# IoT4Bees-Ctrl_1V1.net
KiCad netlist of a schematic drawn in EAGLE
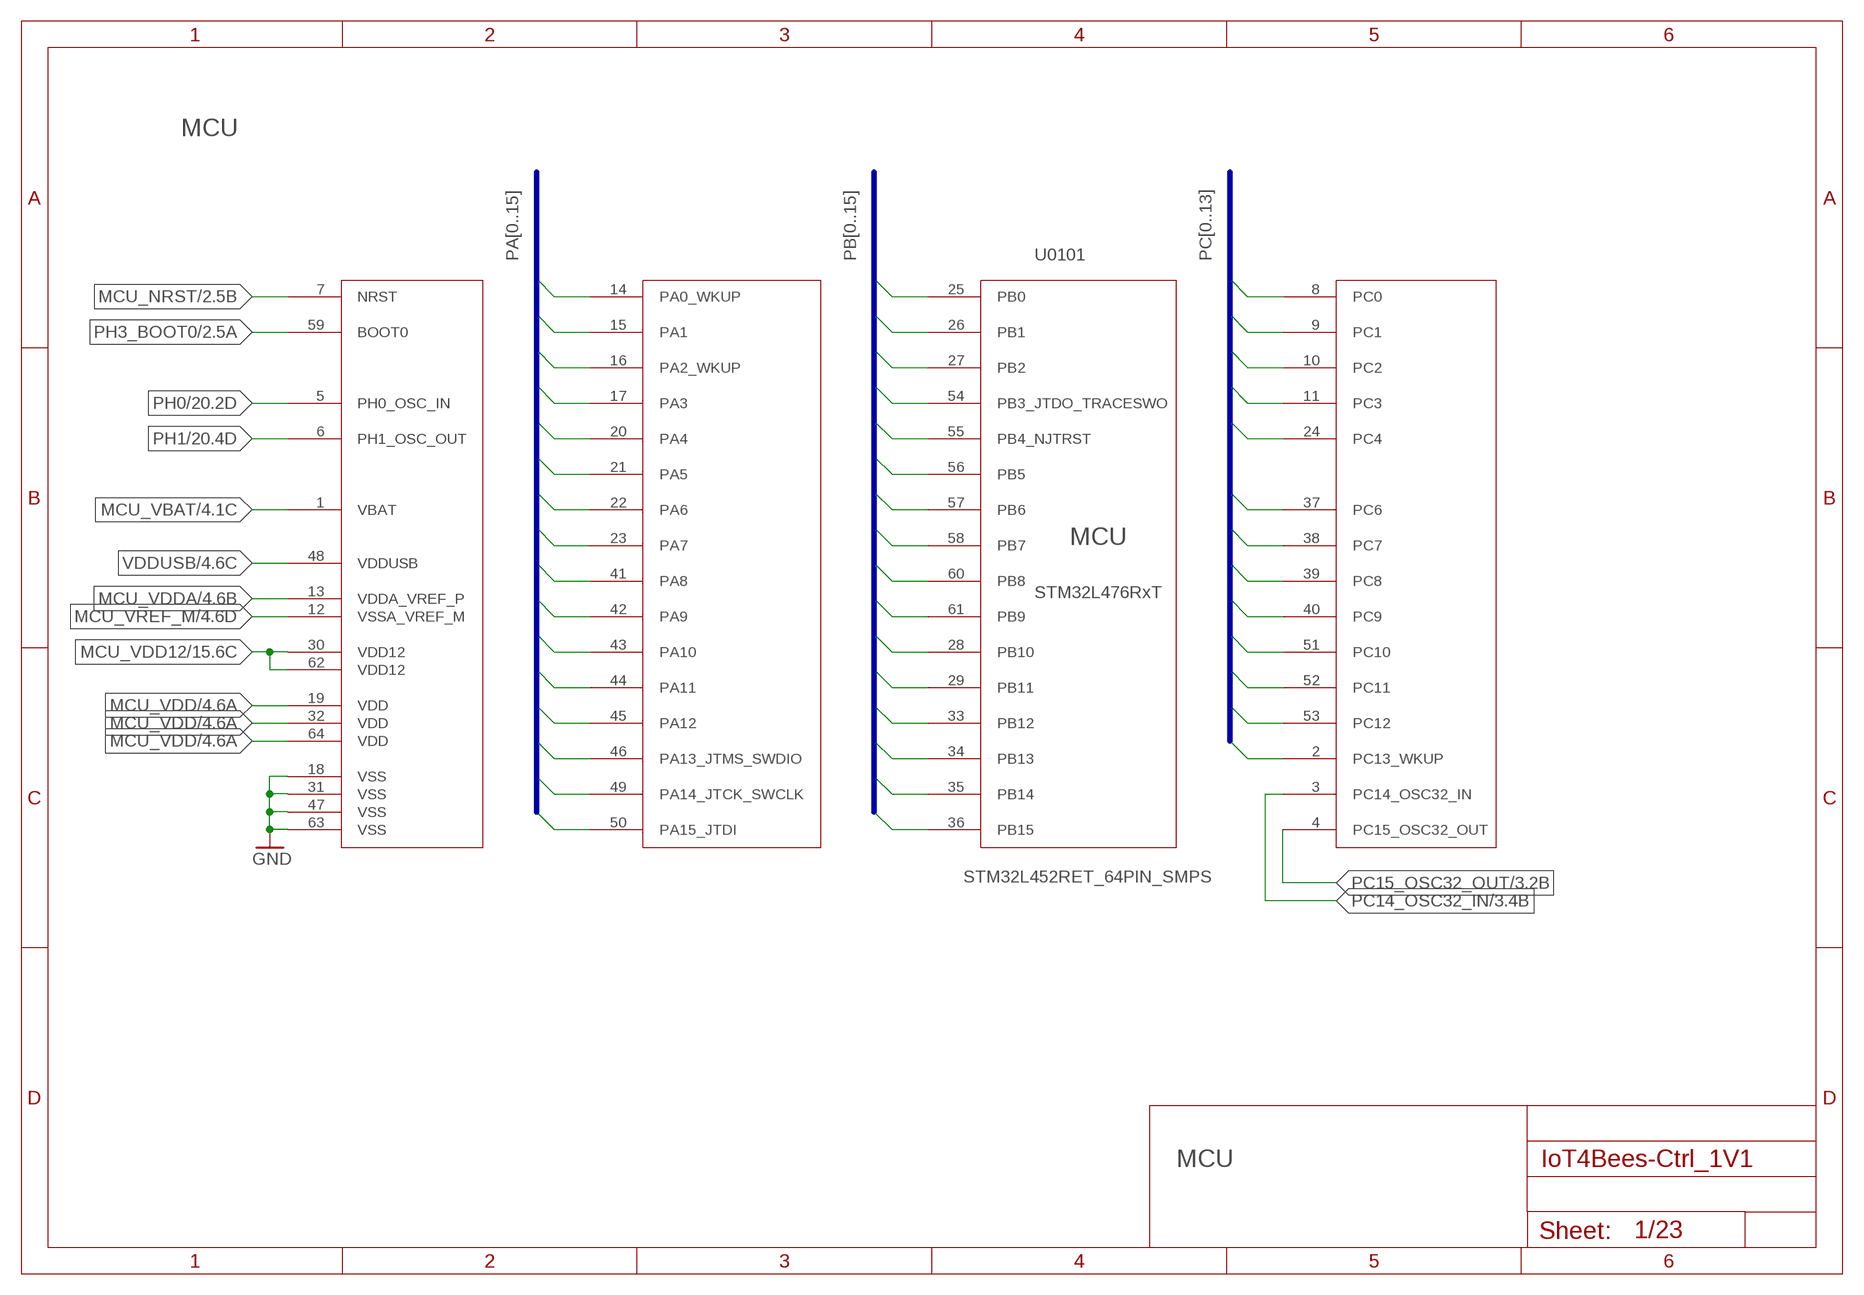
[diagram p0: schematic, sheet 1]
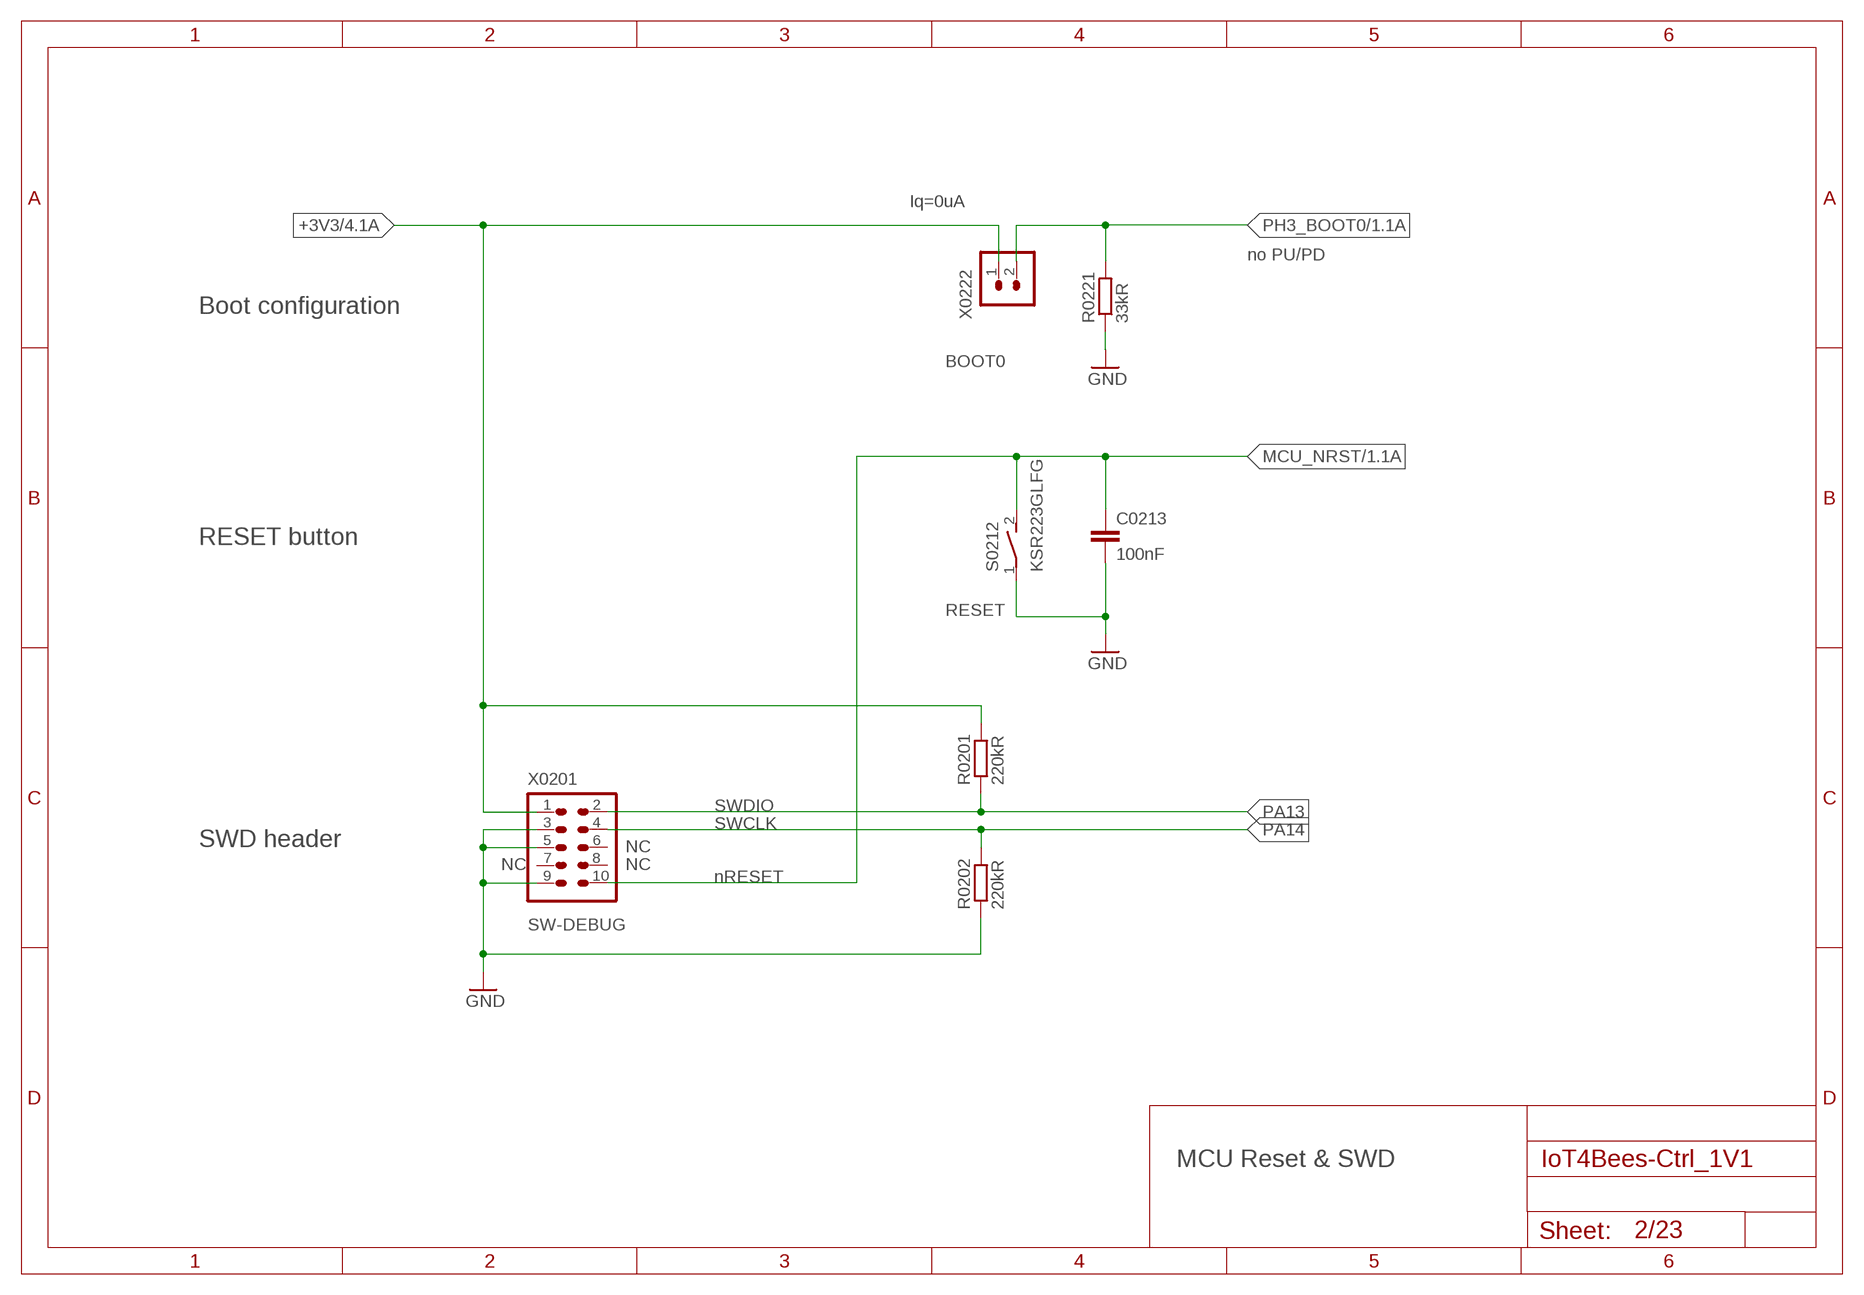
[diagram p1: schematic, sheet 2]
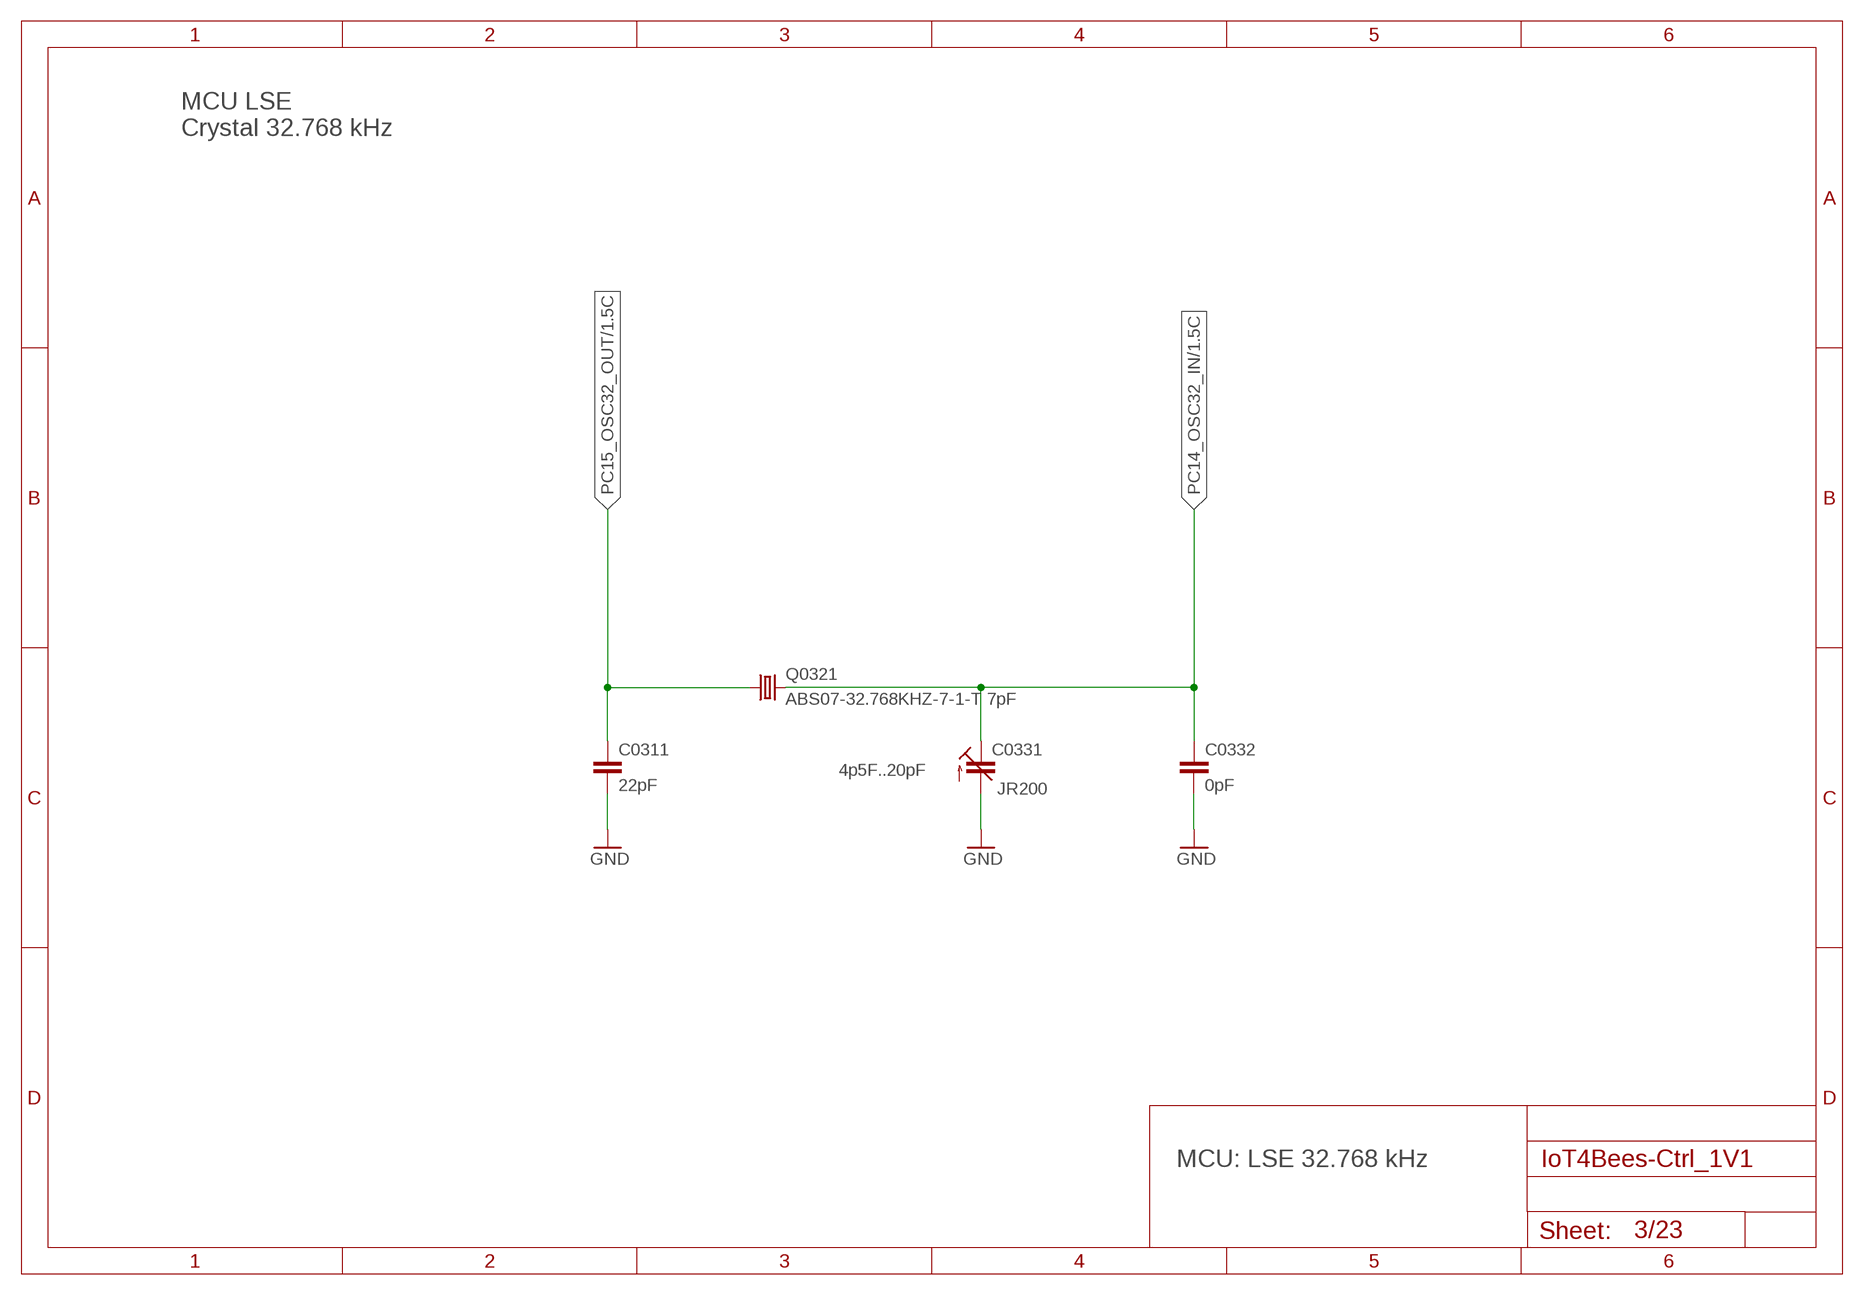
[diagram p2: schematic, sheet 3]
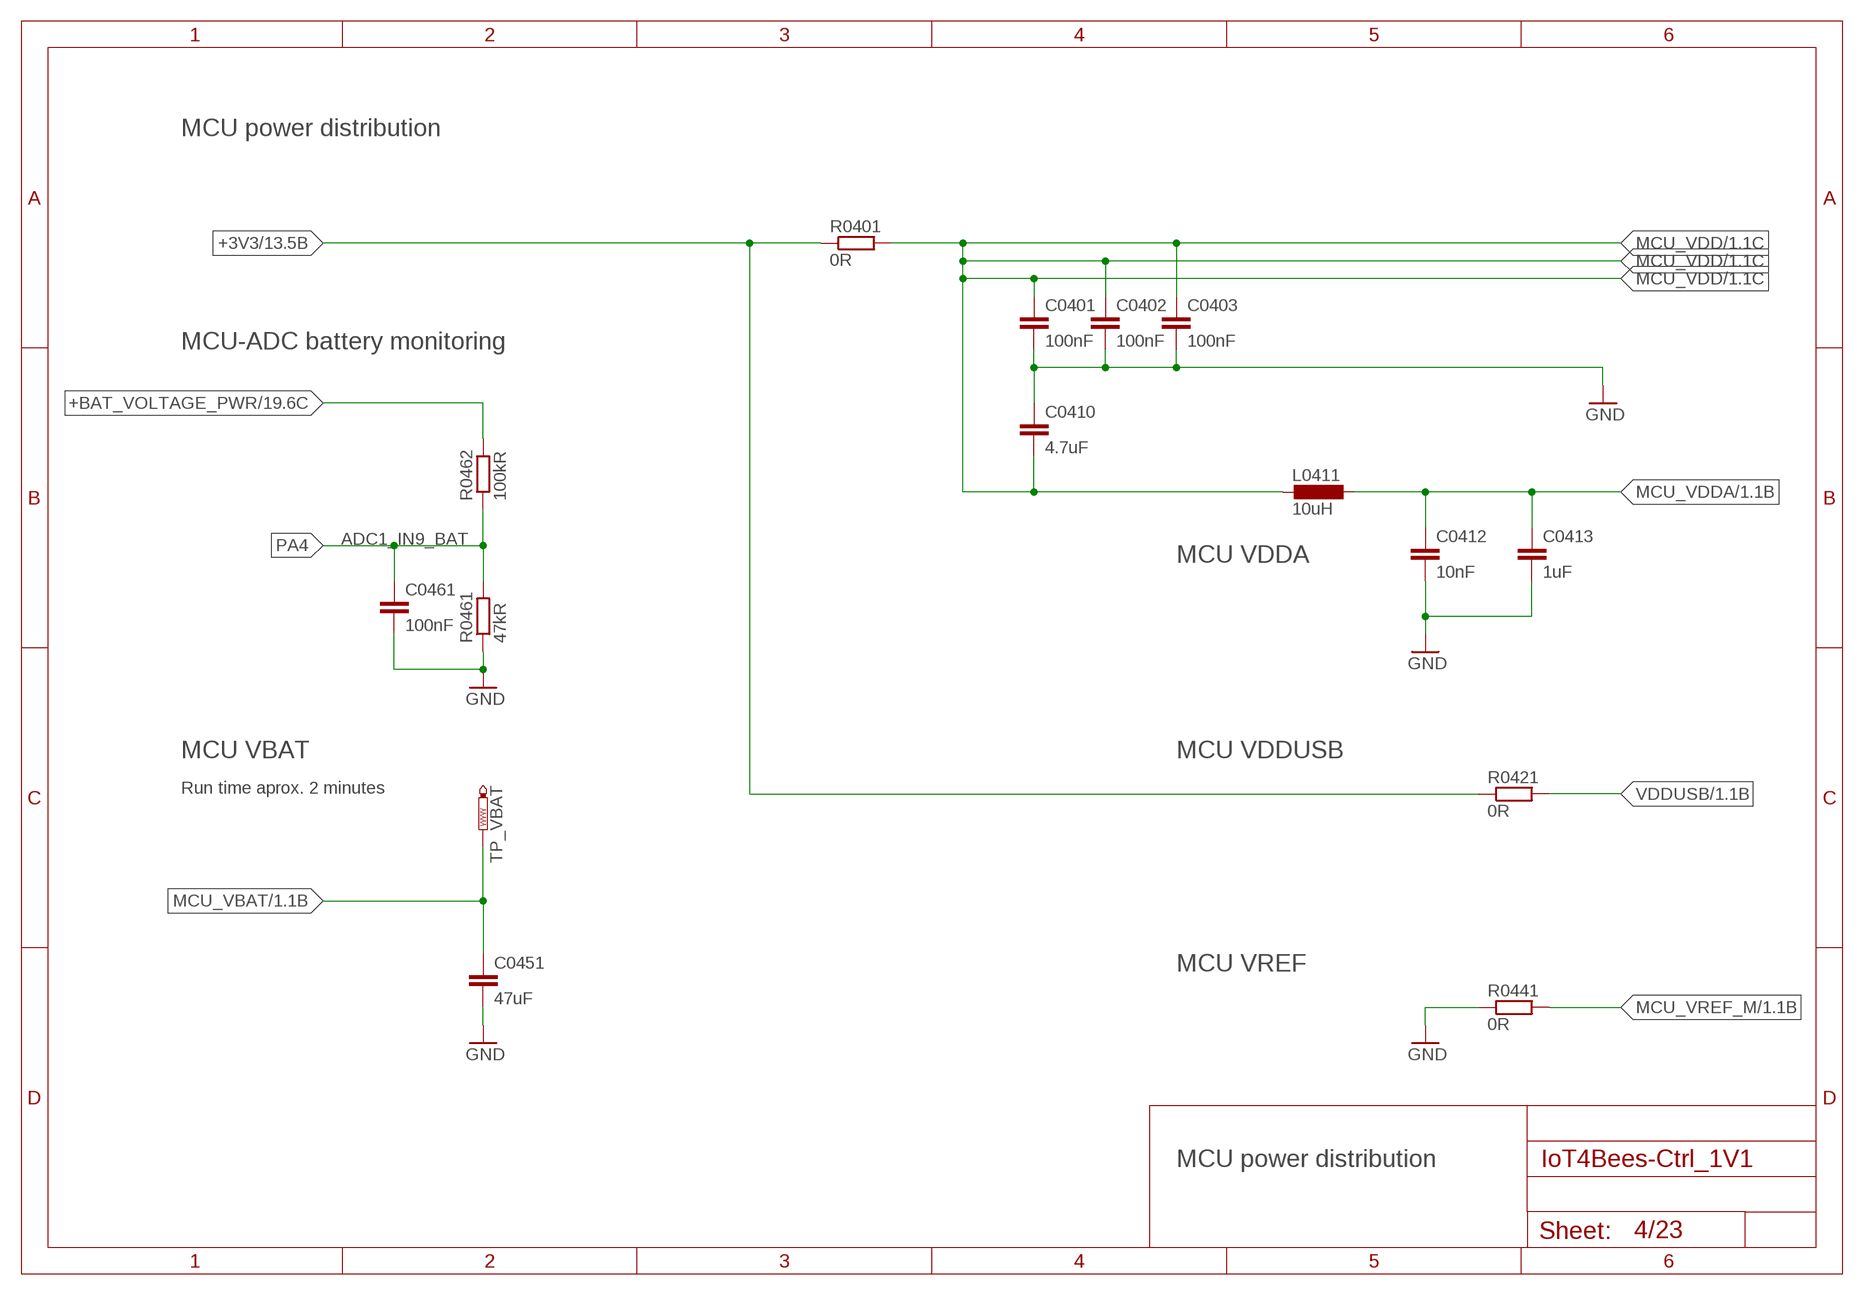
[diagram p3: schematic, sheet 4]
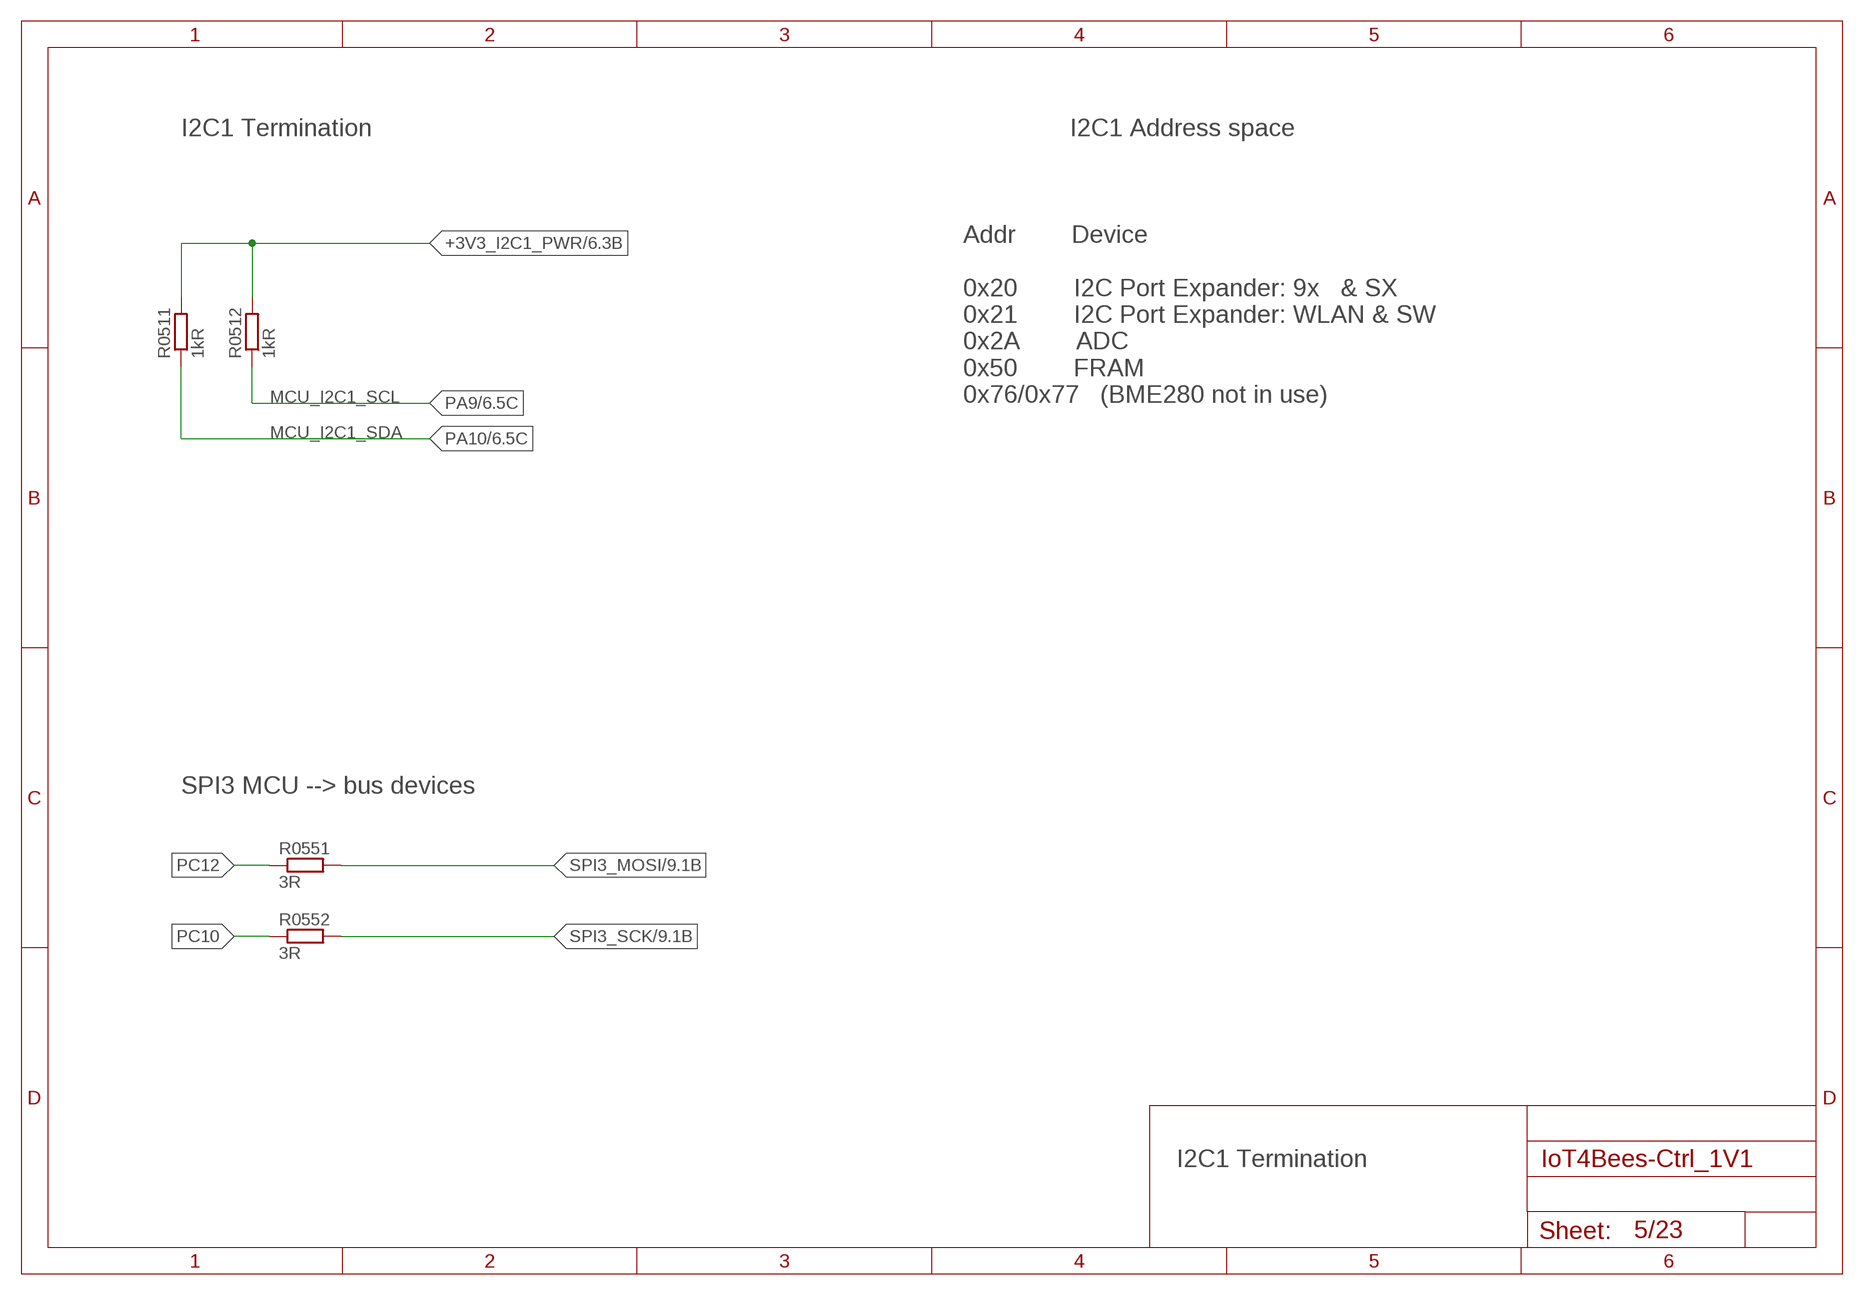
[diagram p4: schematic, sheet 5]
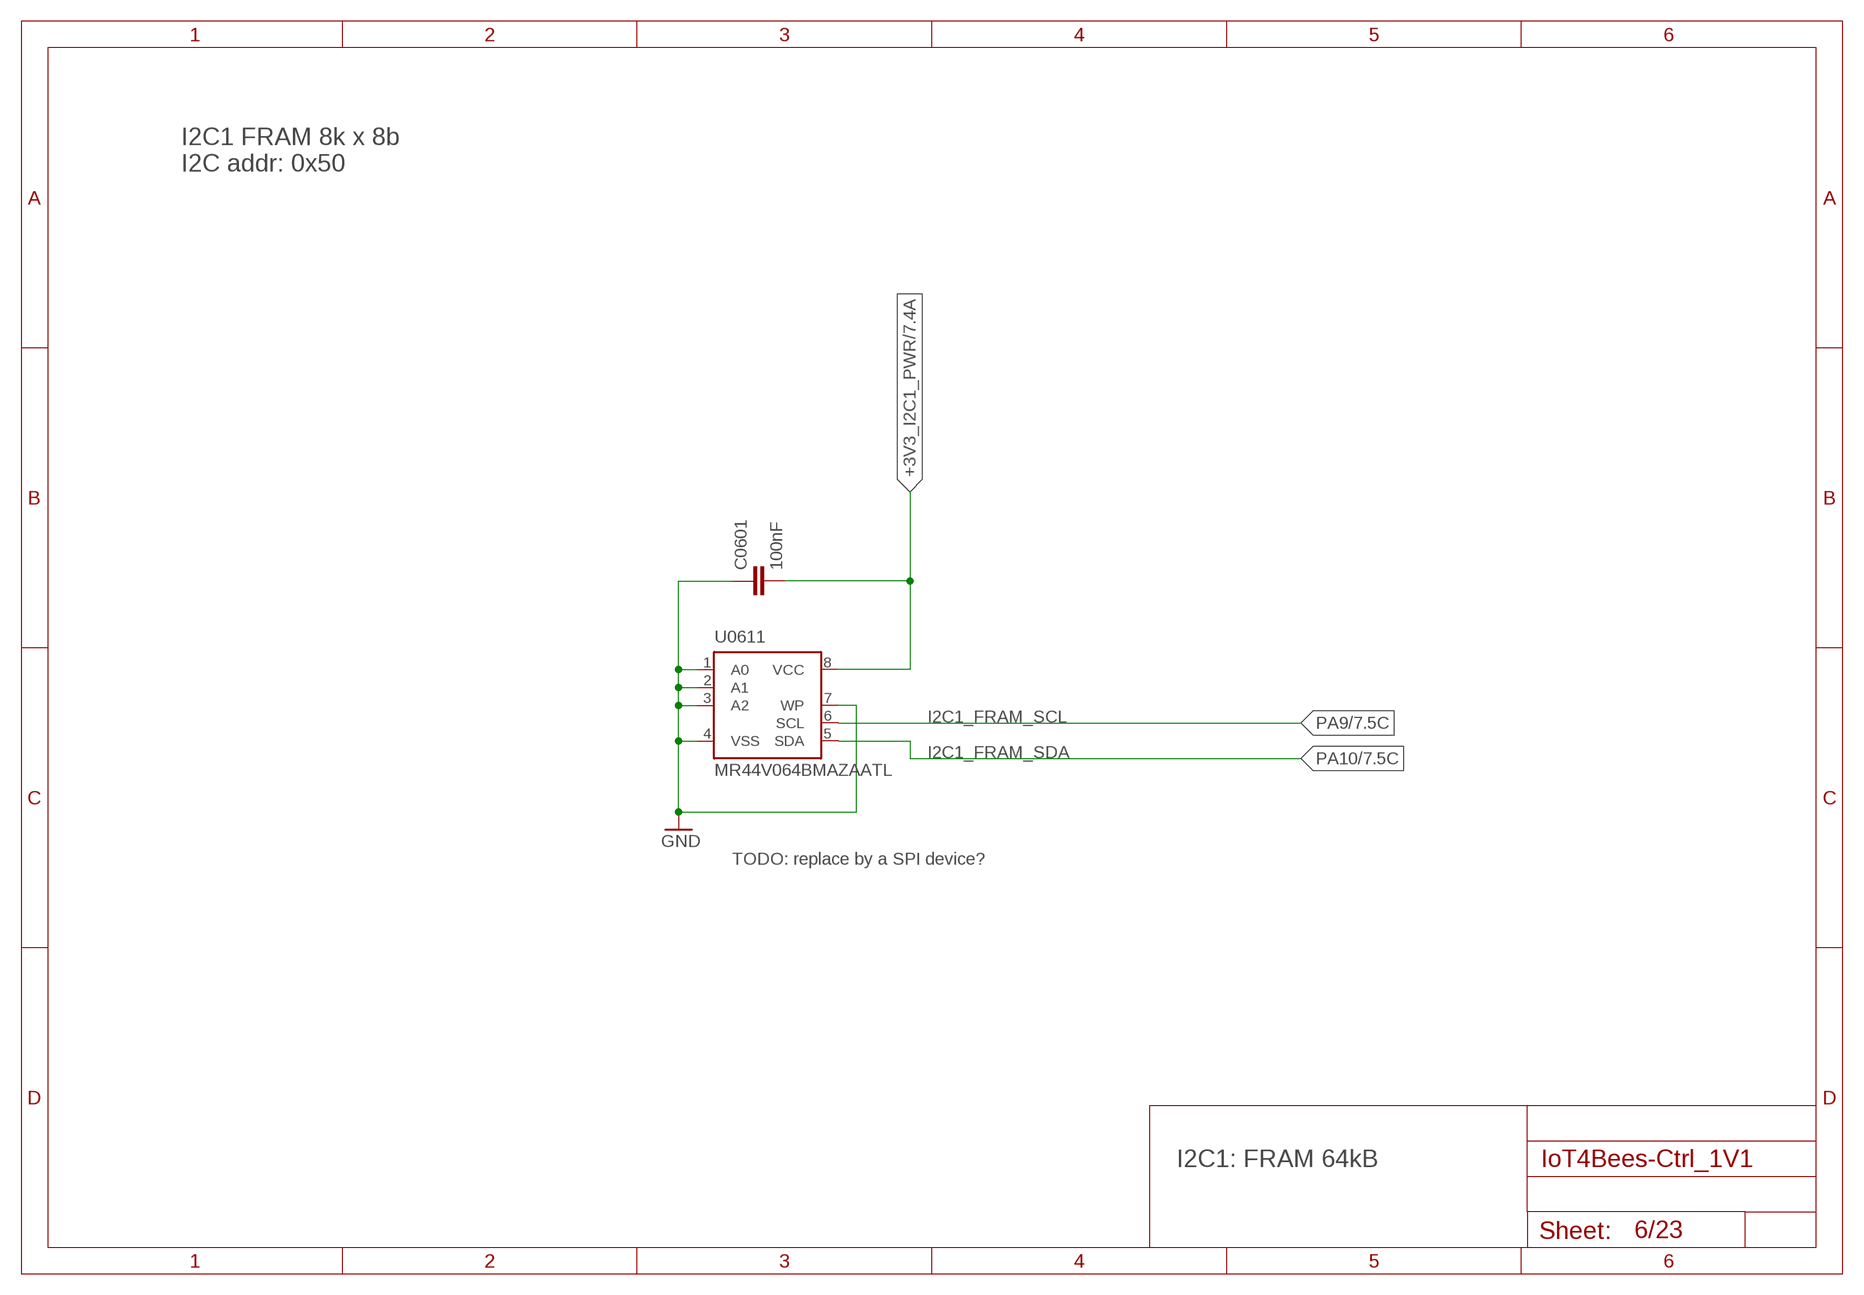
[diagram p5: schematic, sheet 6]
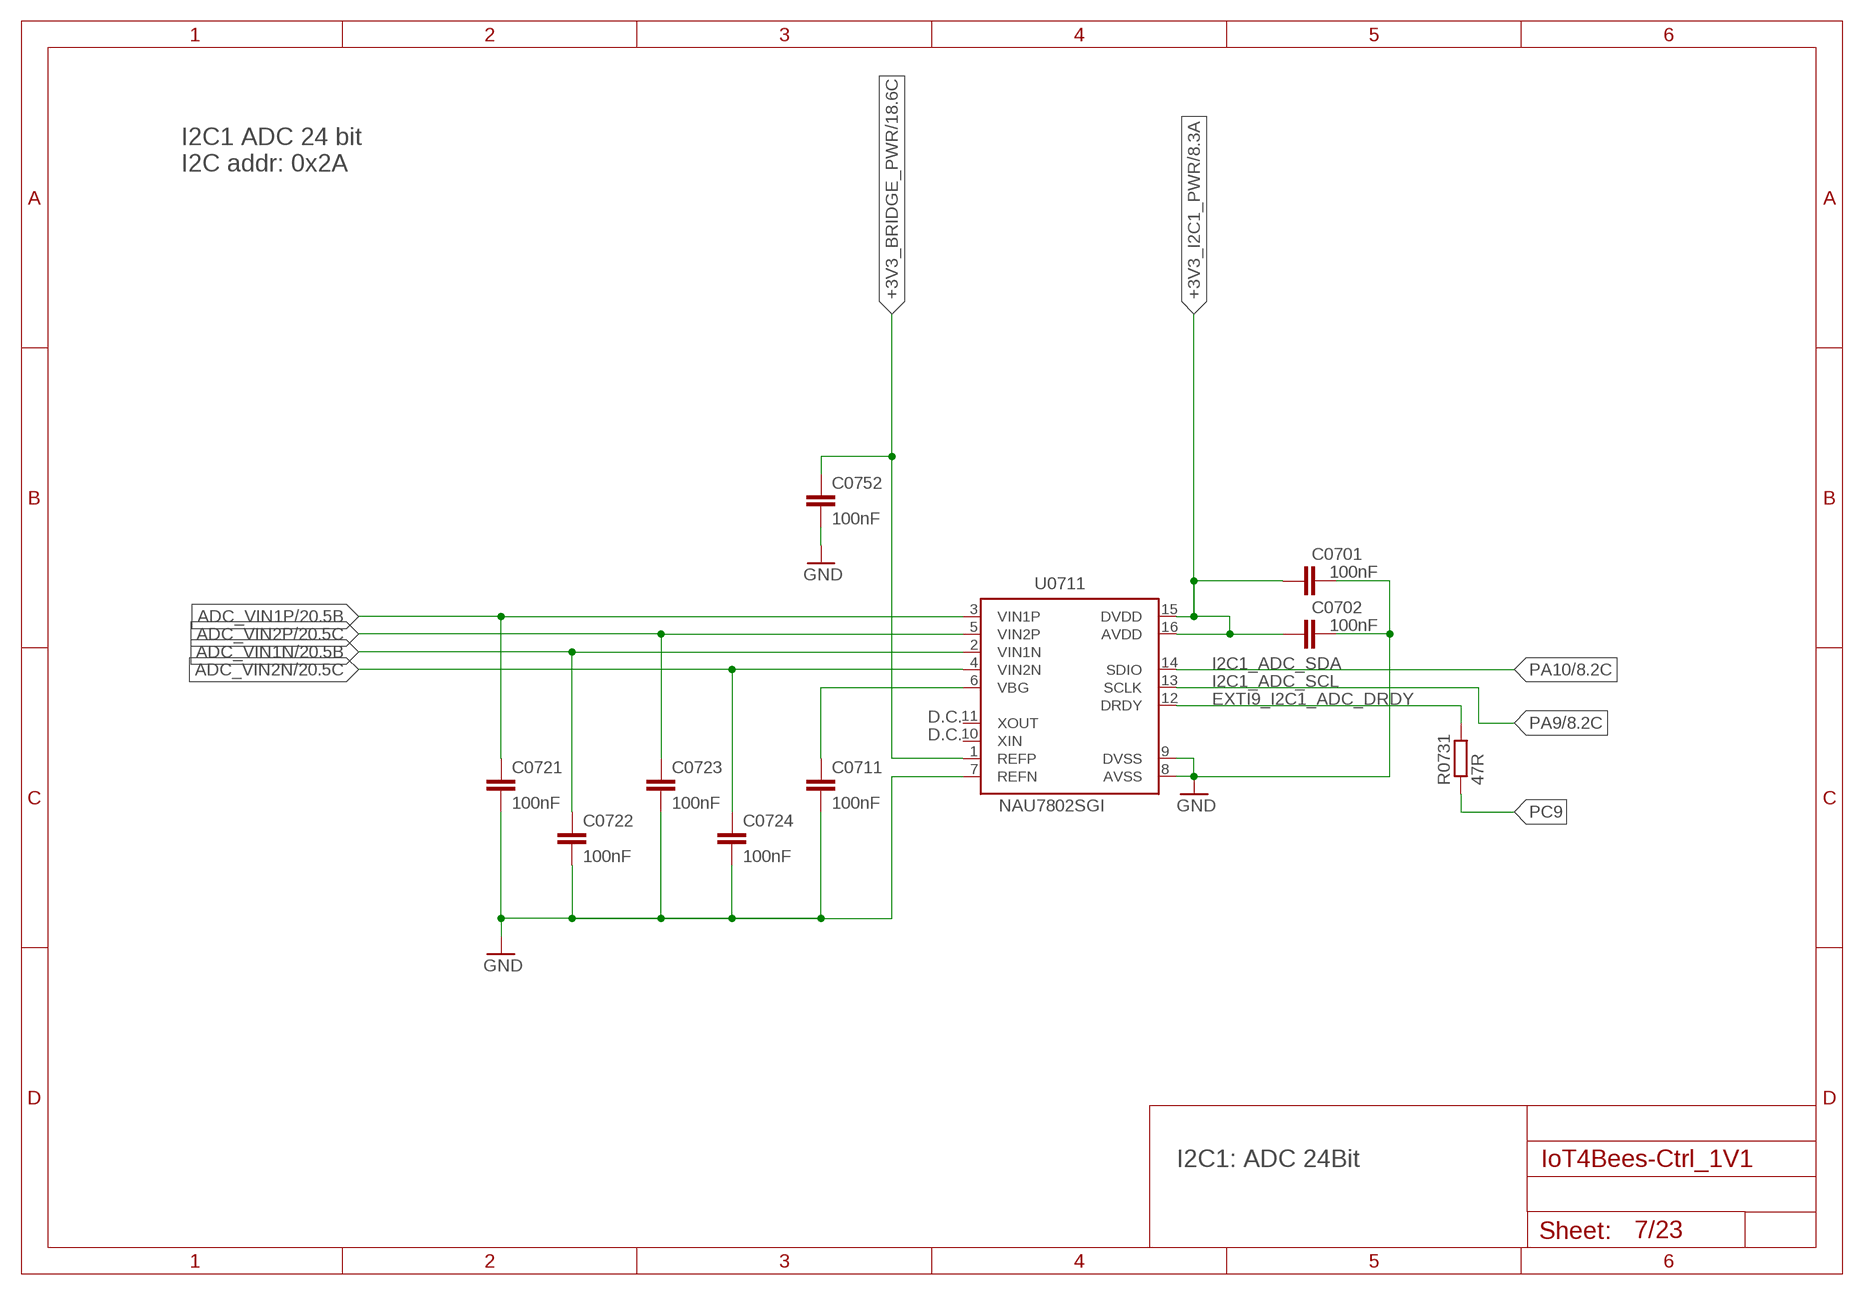
[diagram p6: schematic, sheet 7]
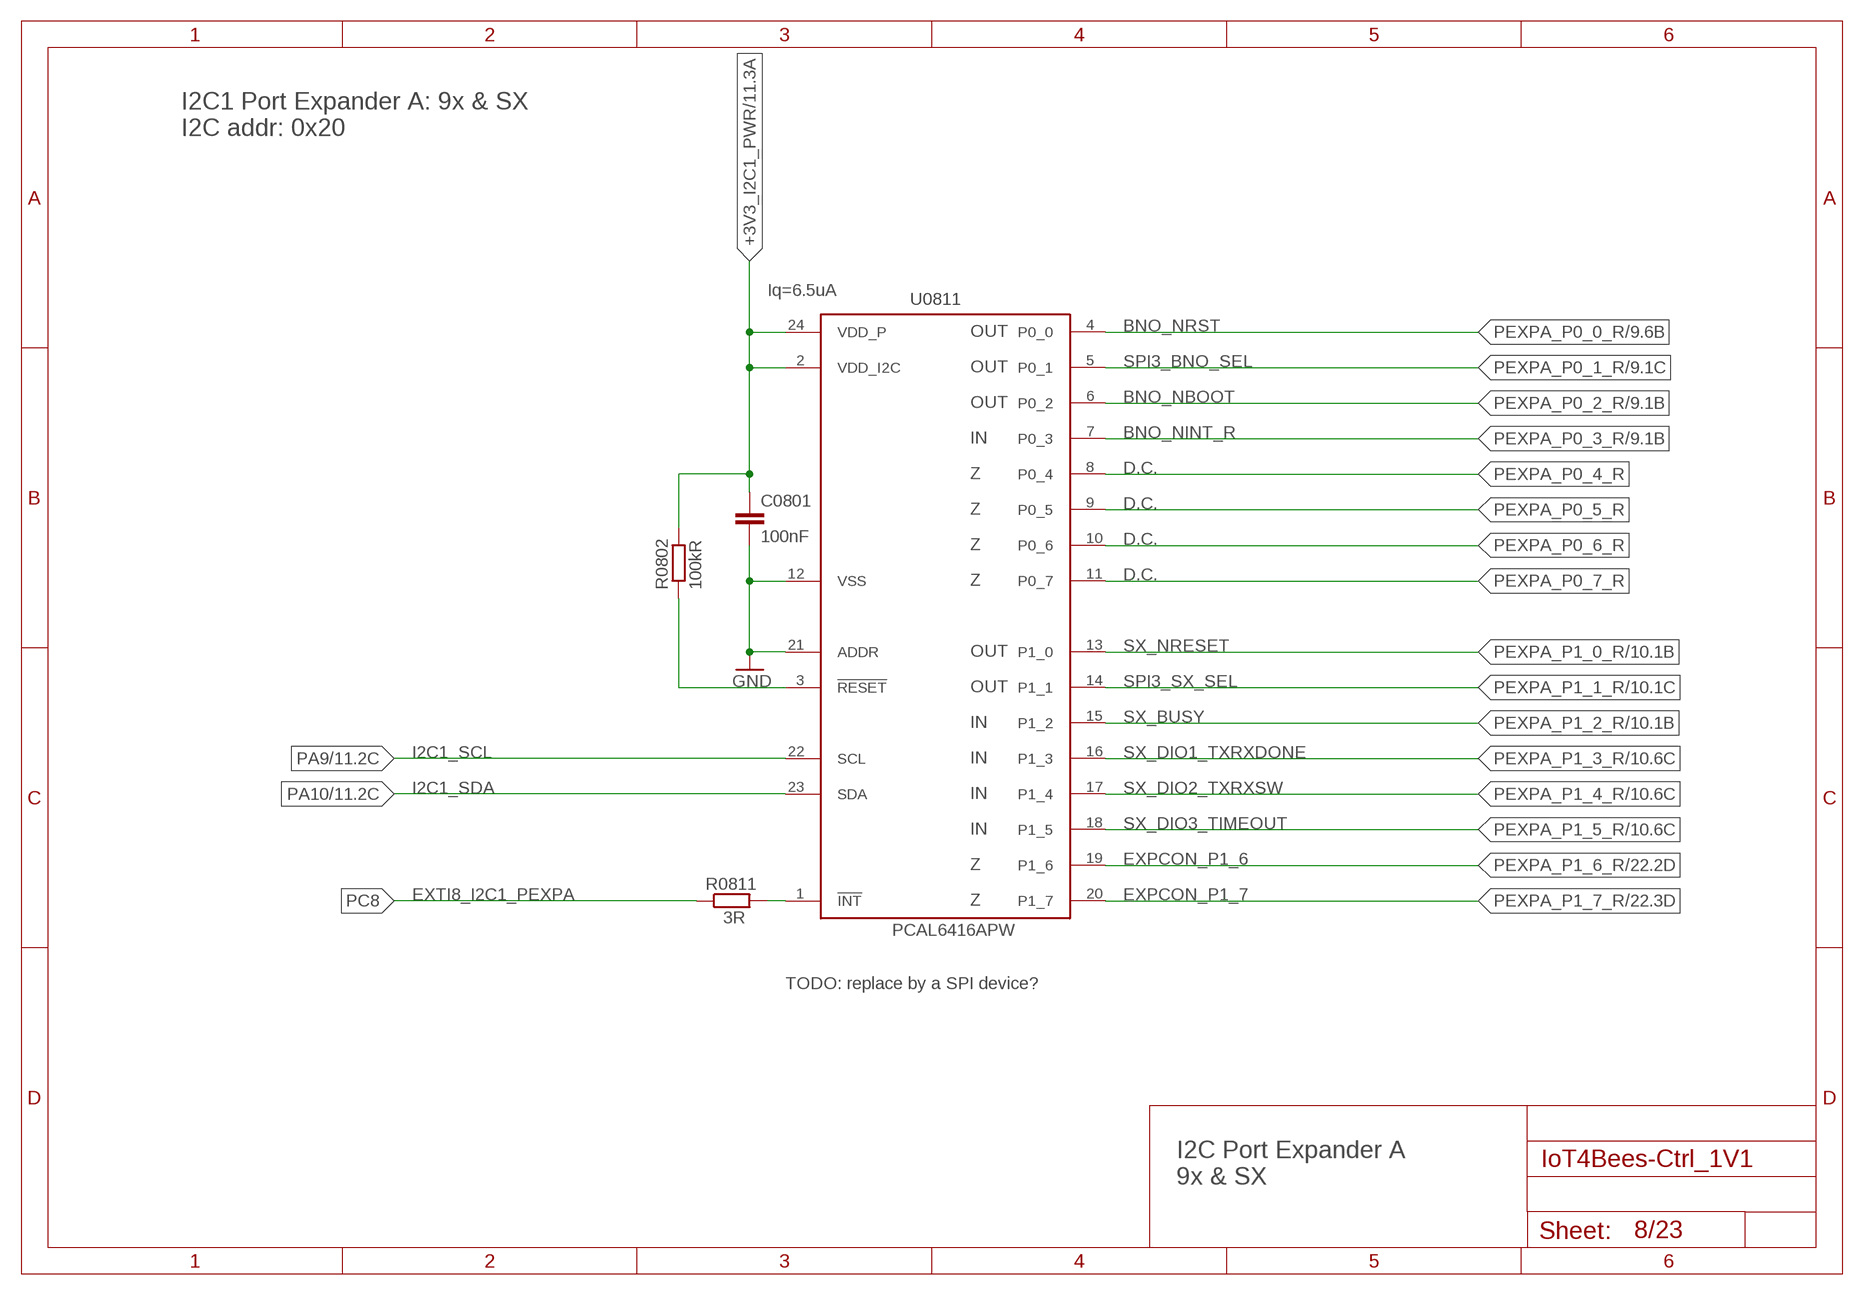
[diagram p7: schematic, sheet 8]
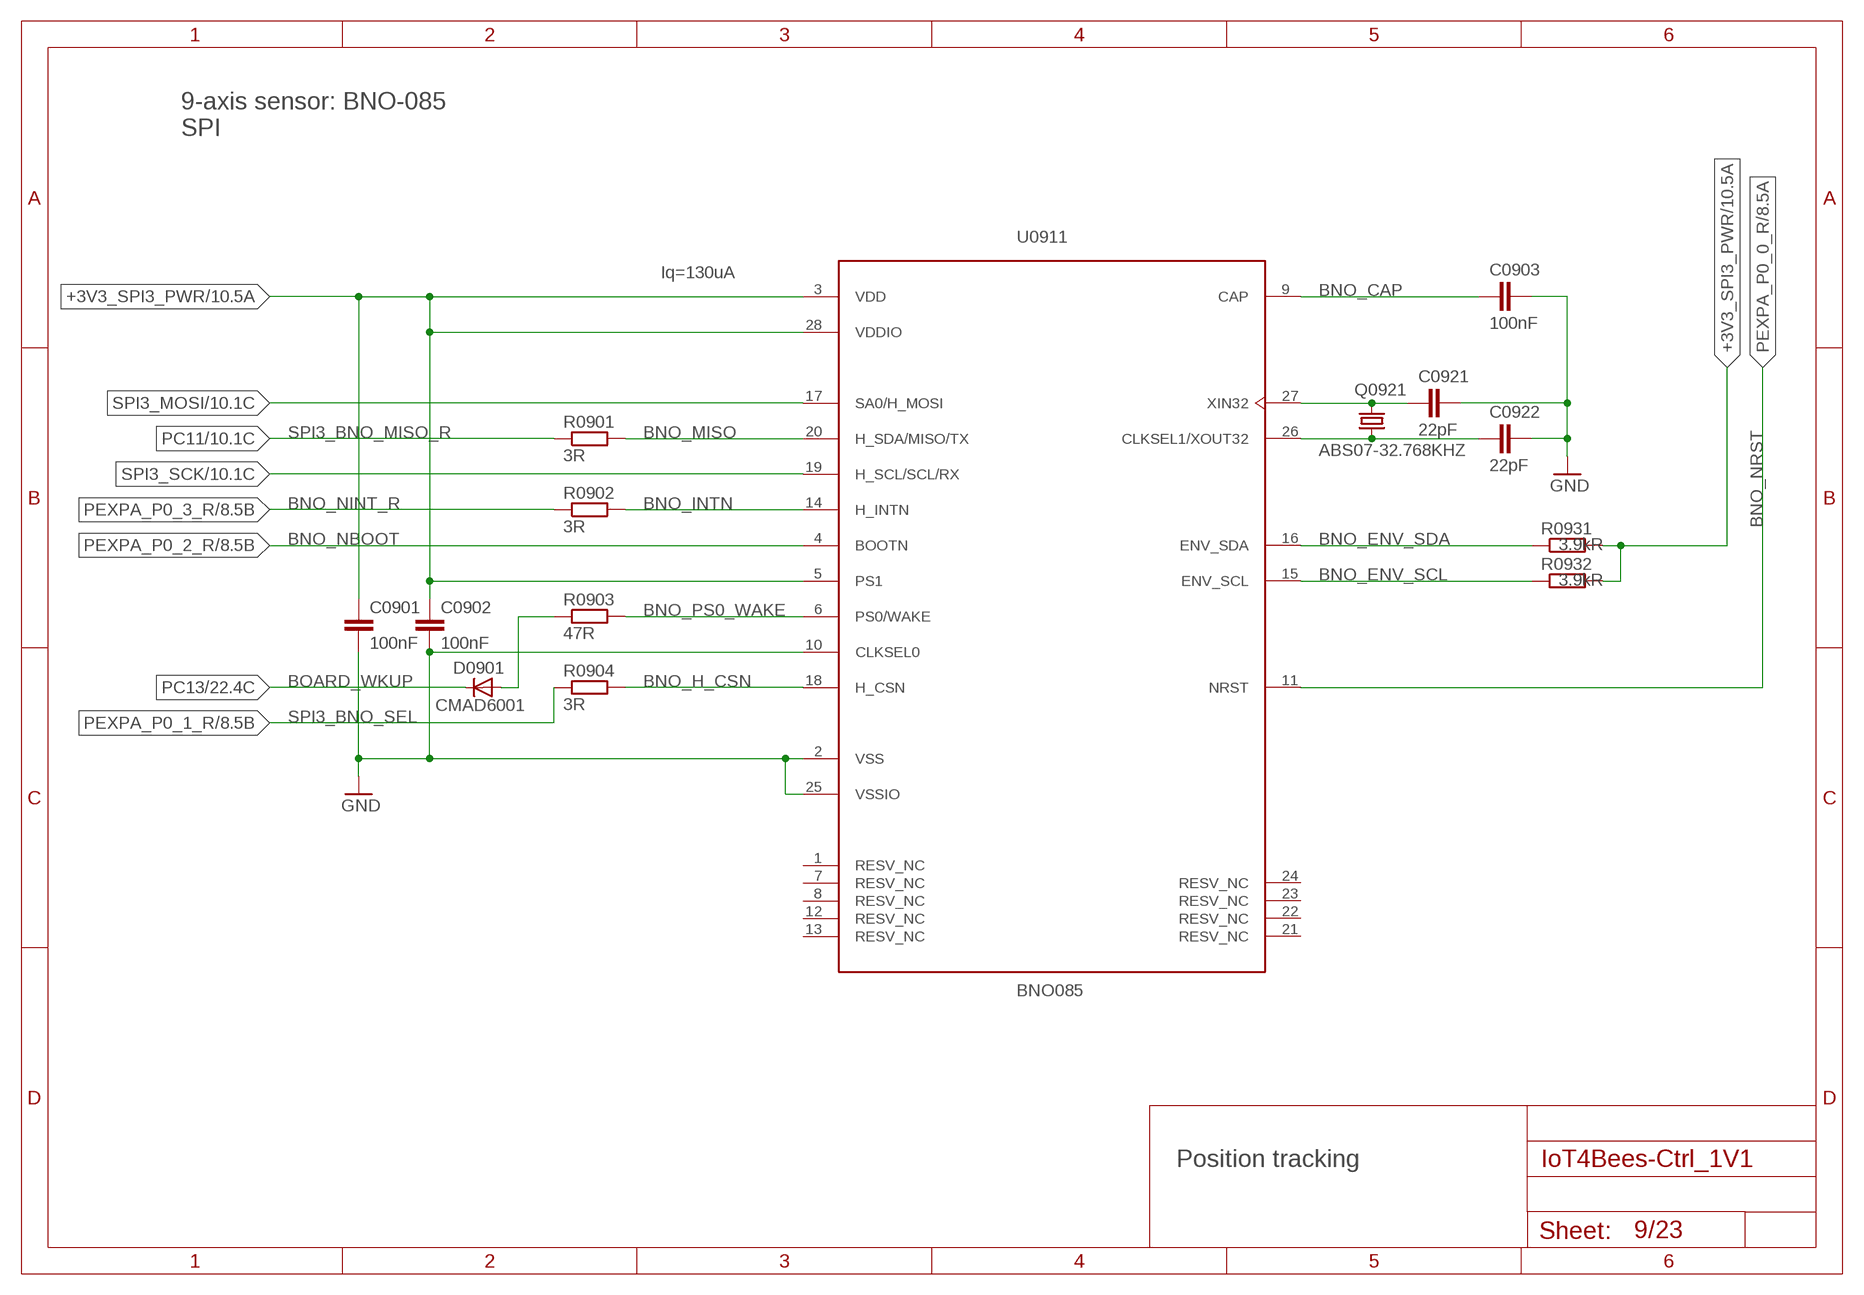
[diagram p8: schematic, sheet 9]
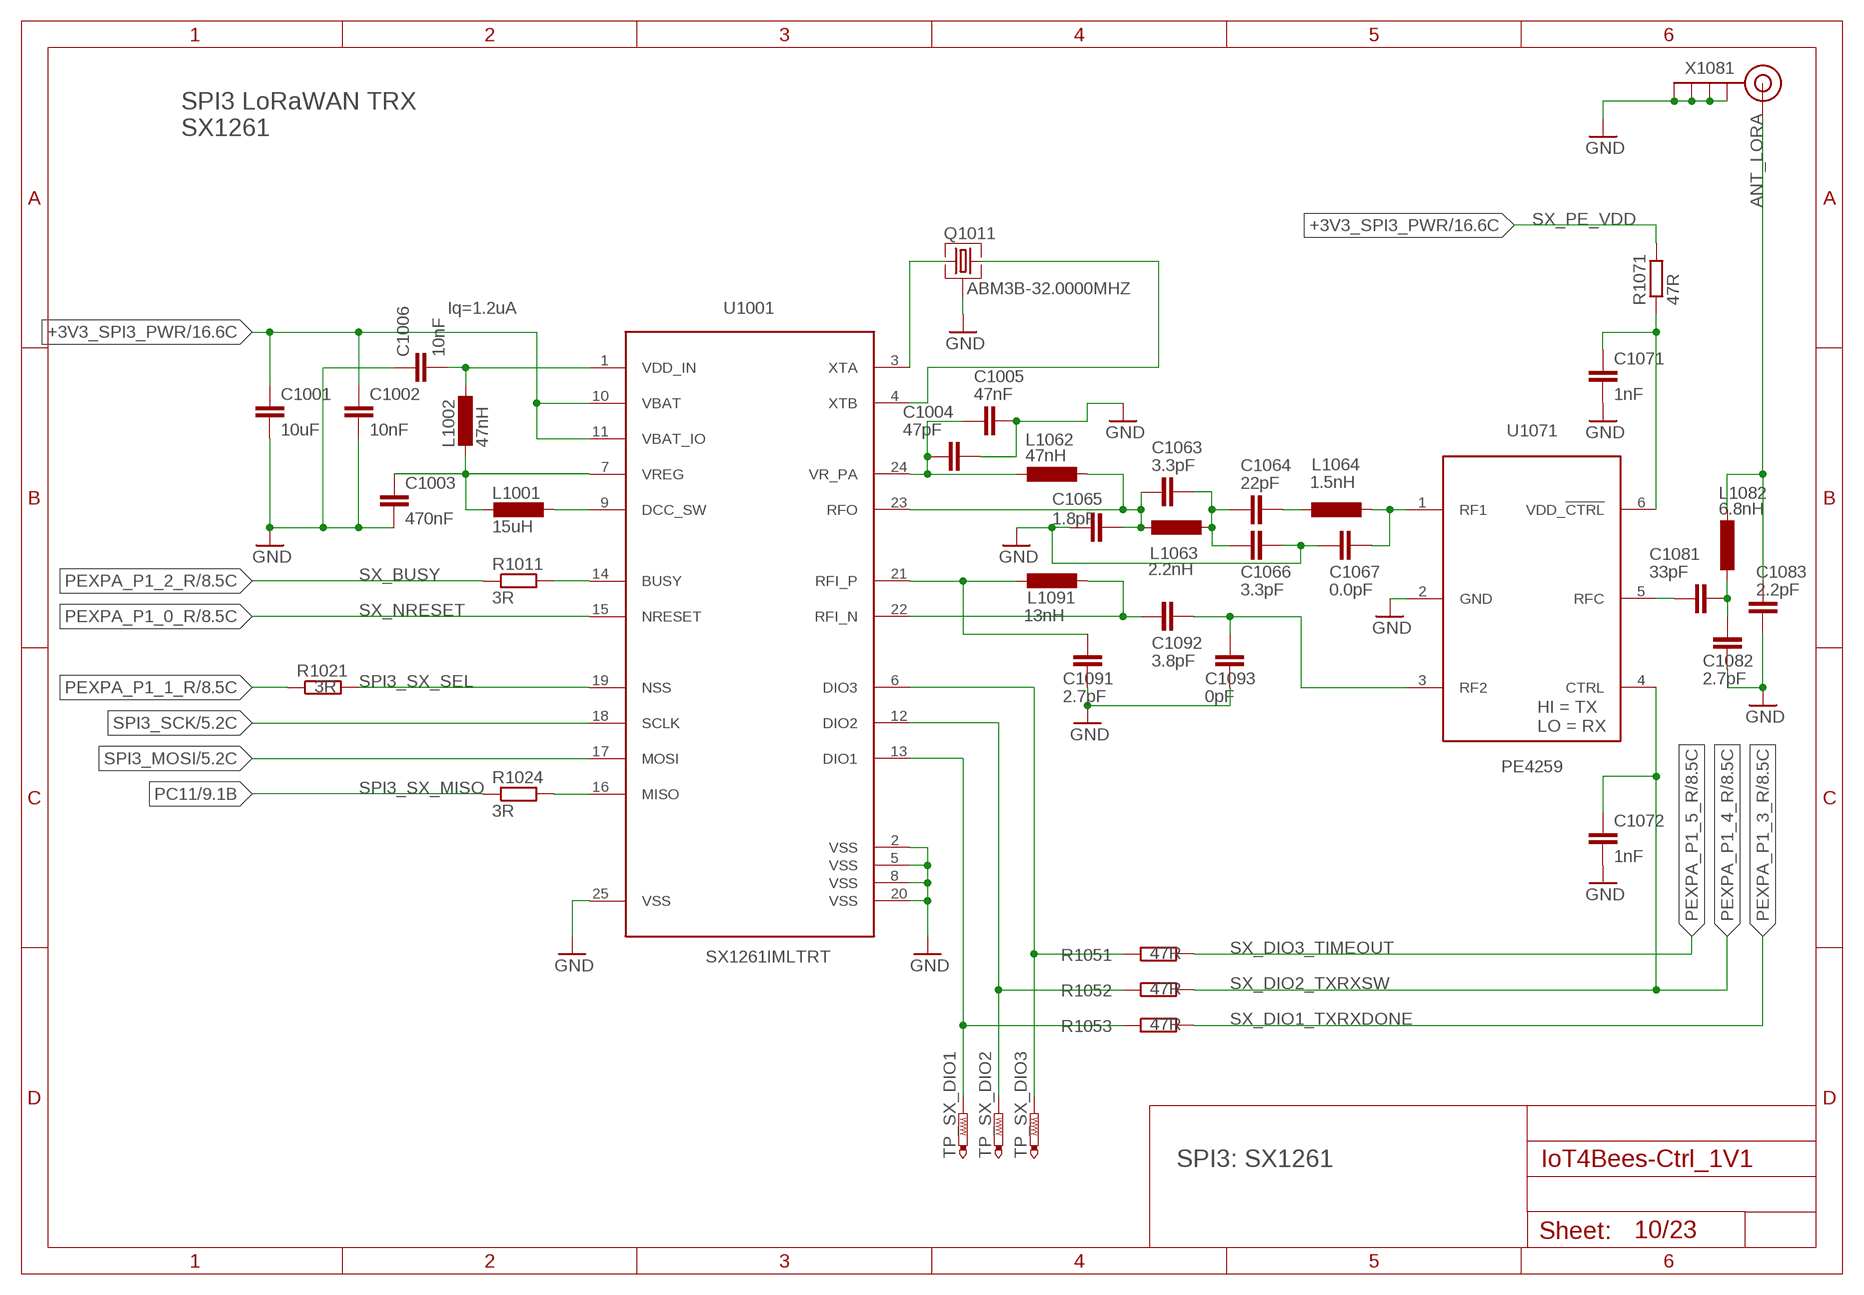
[diagram p9: schematic, sheet 10]
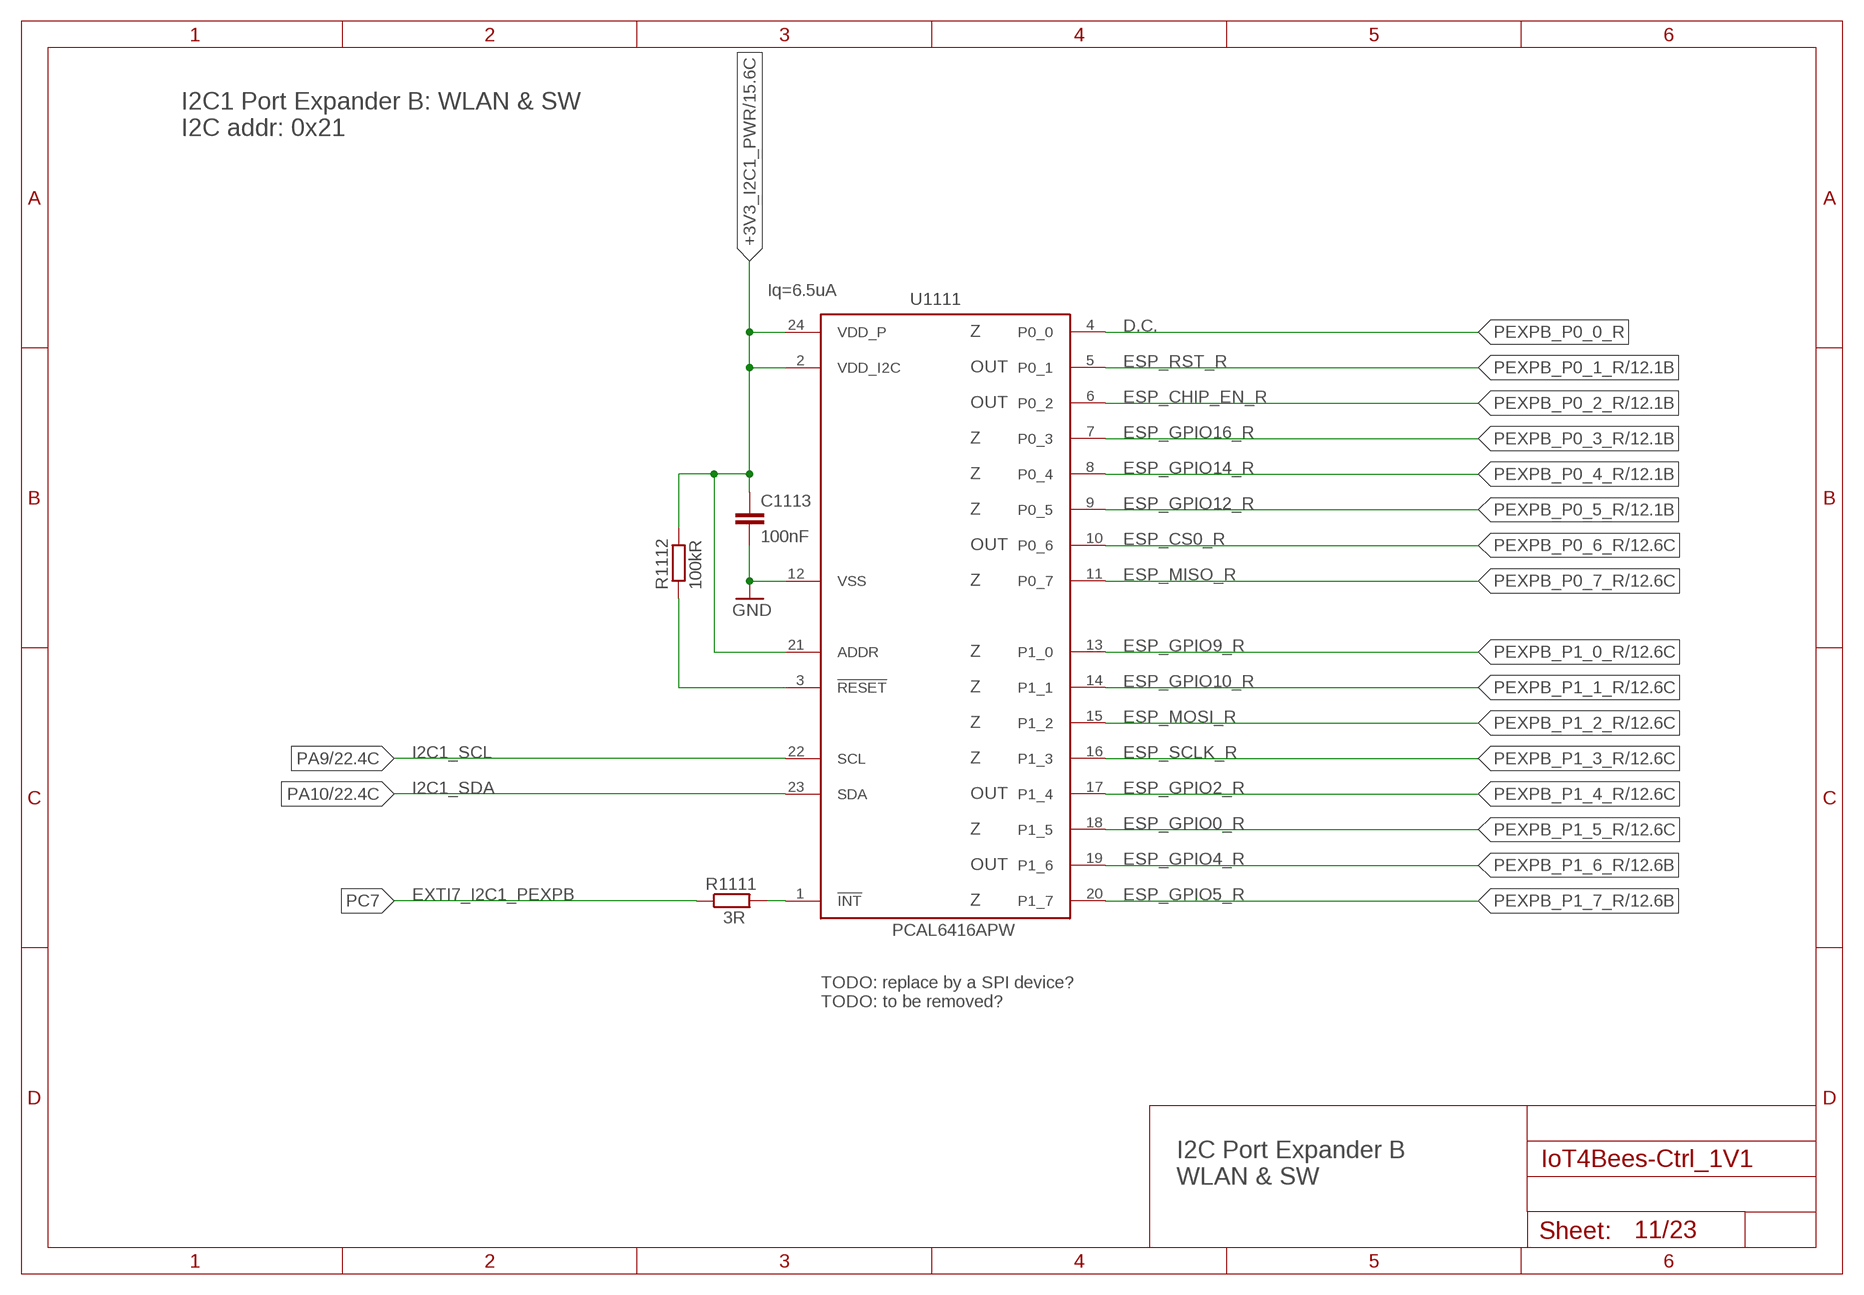
[diagram p10: schematic, sheet 11]
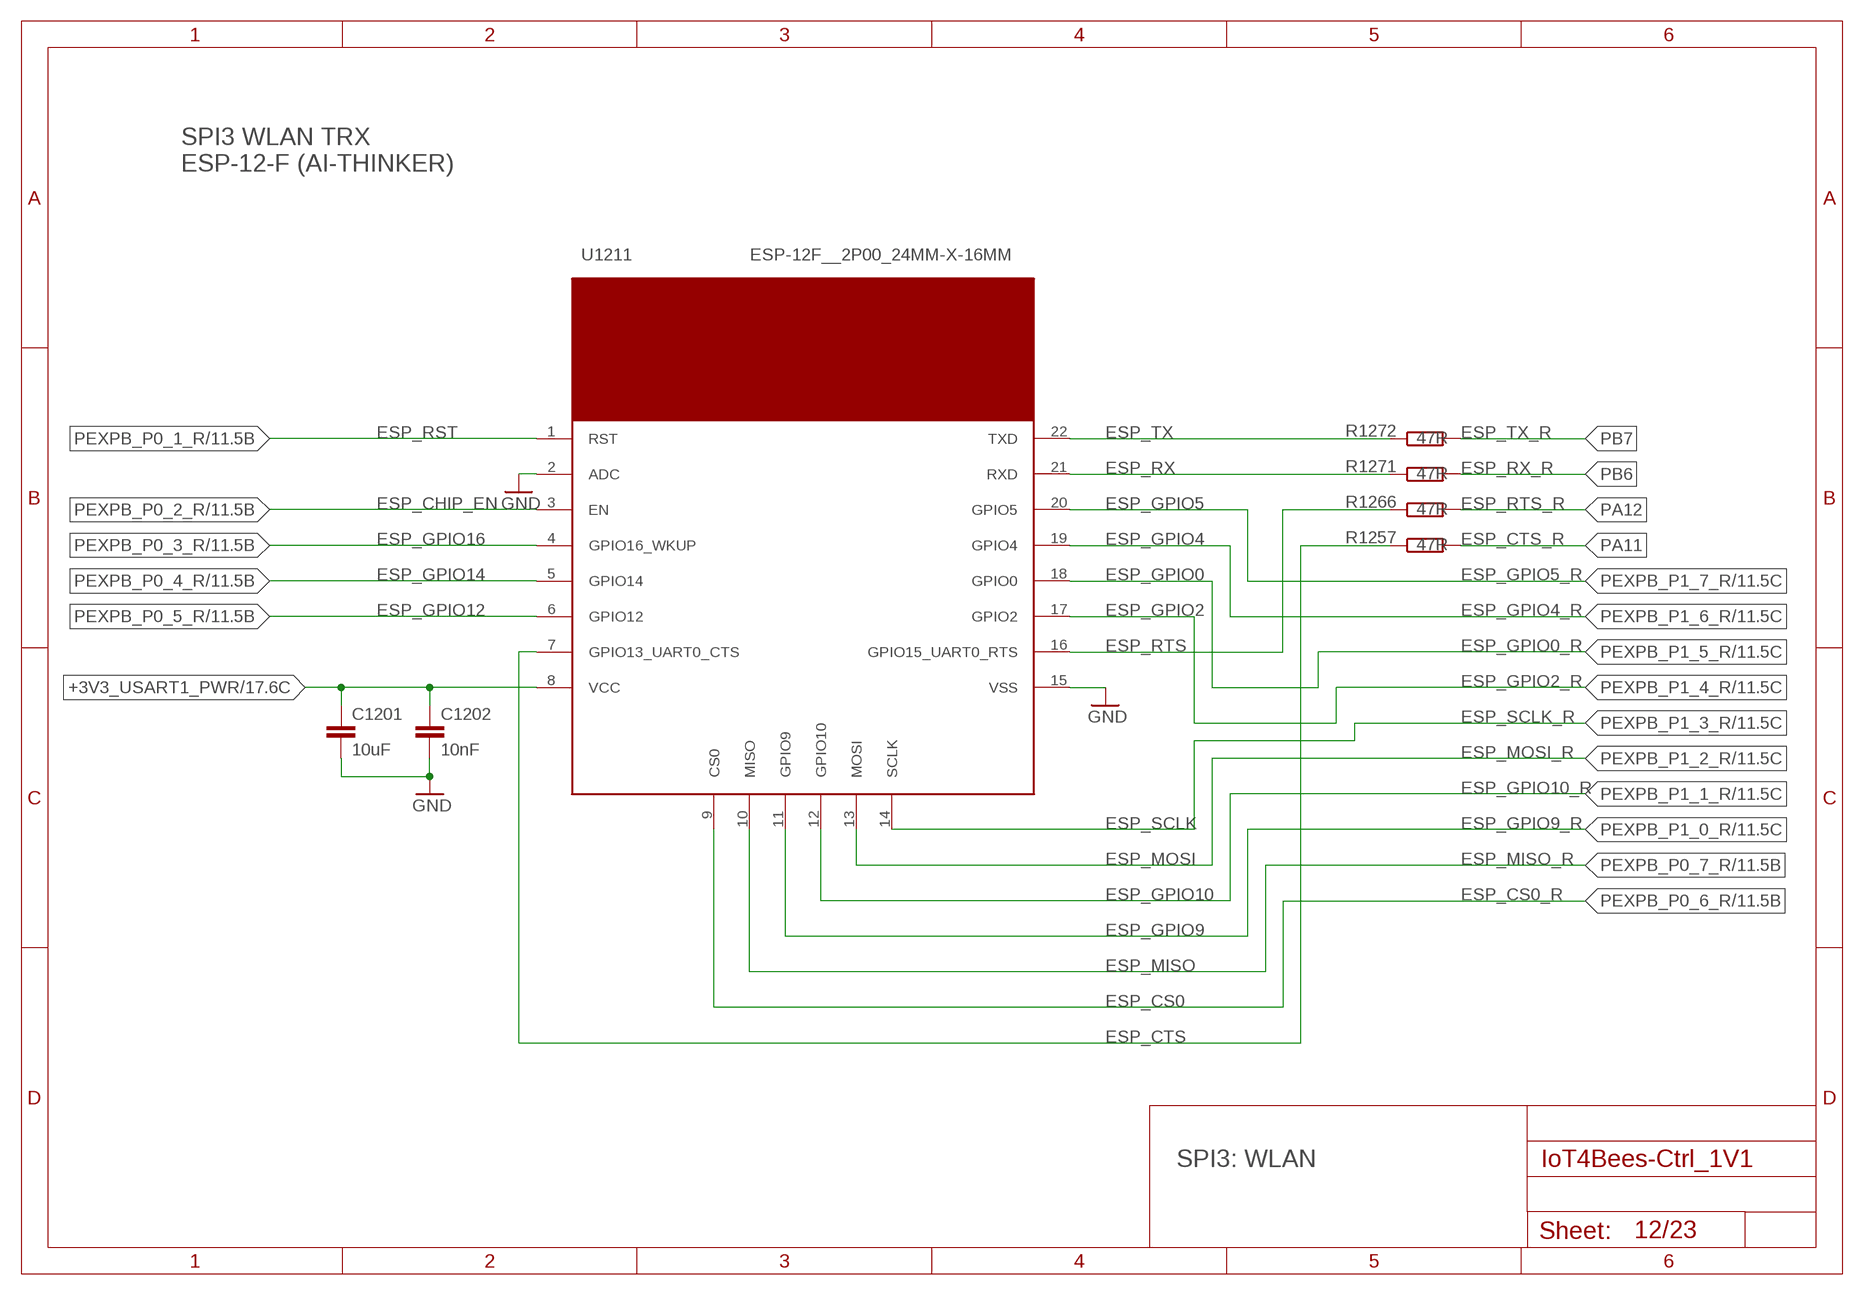
[diagram p11: schematic, sheet 12]
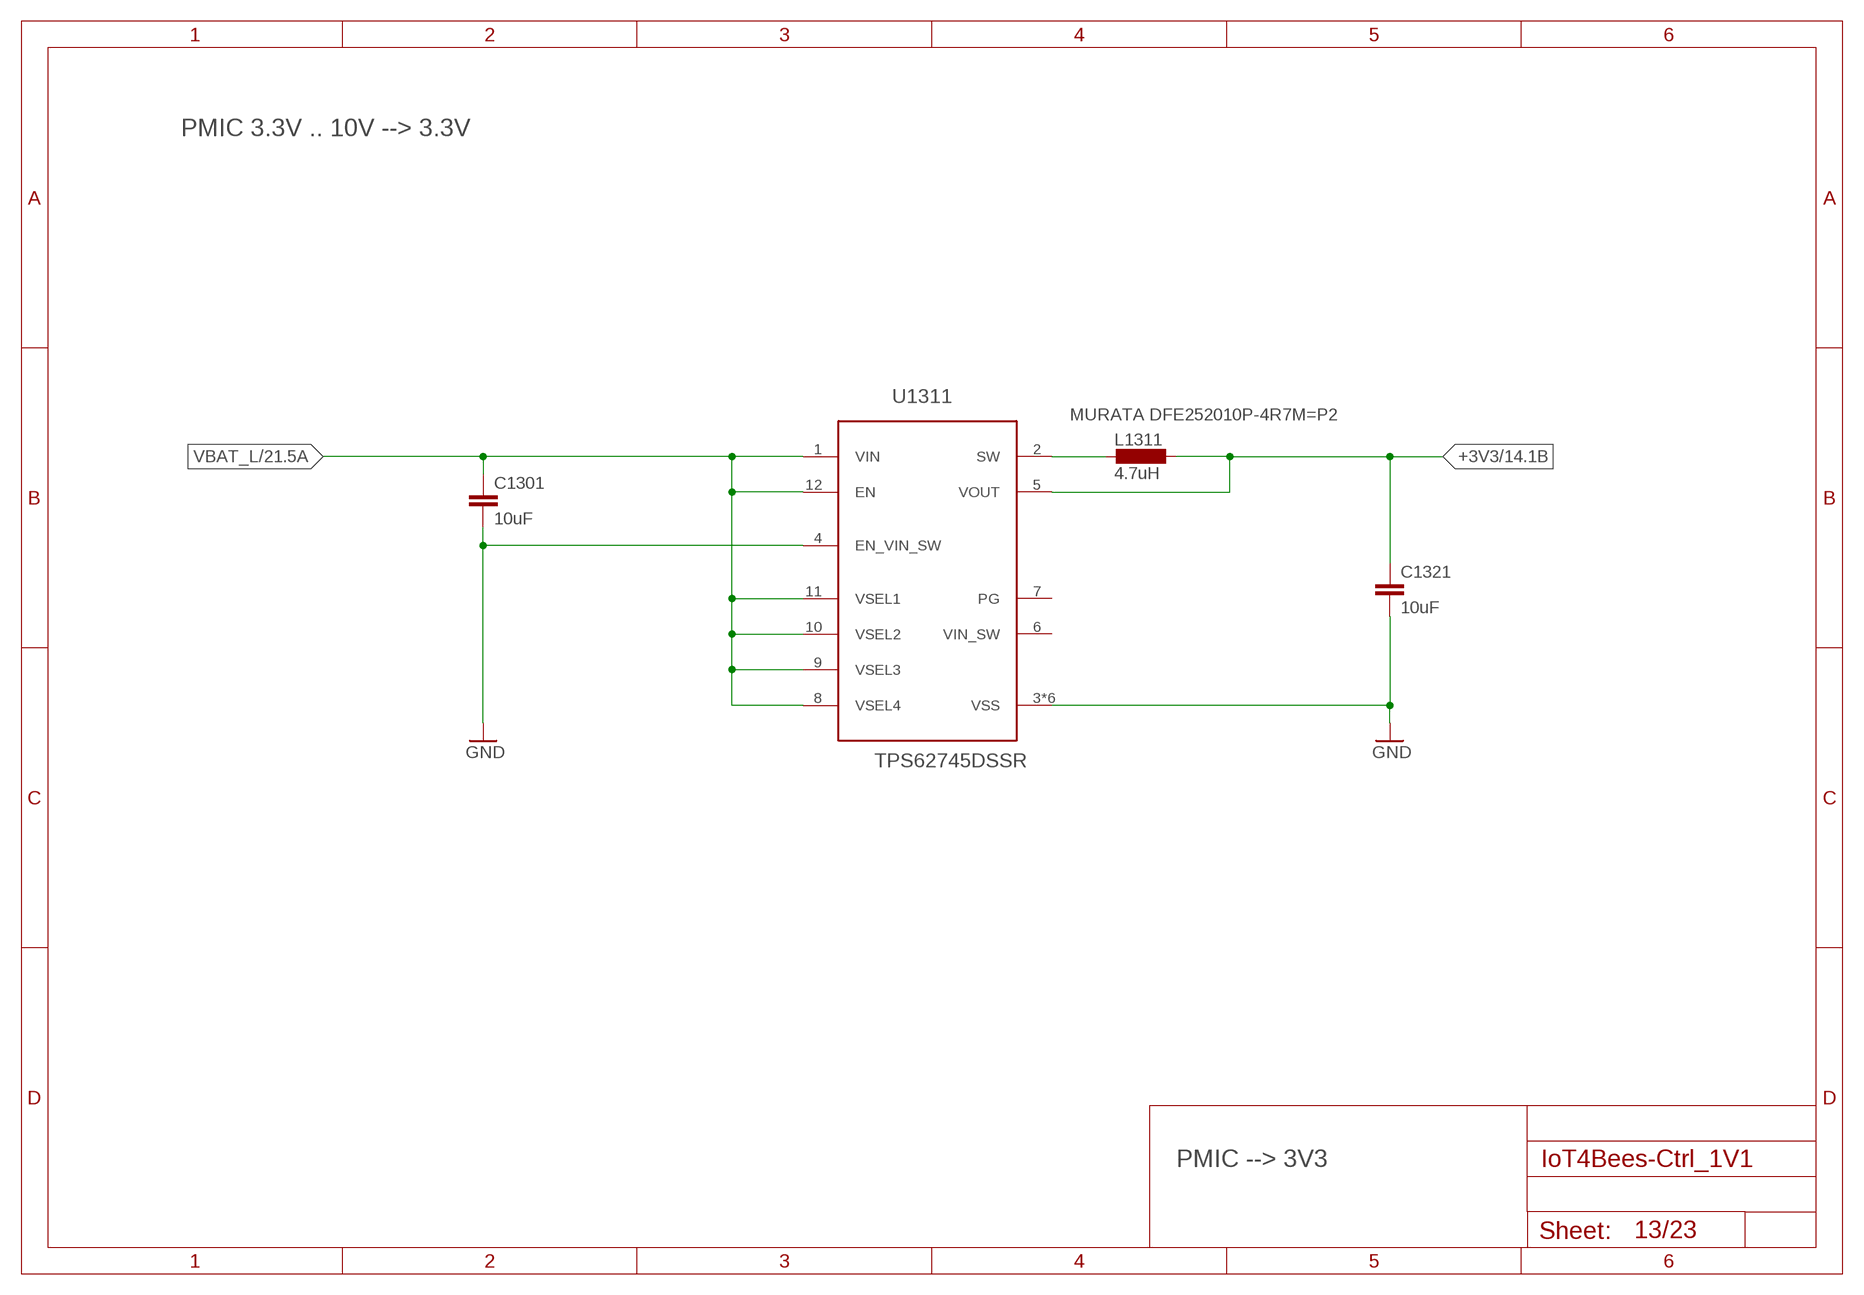
[diagram p12: schematic, sheet 13]
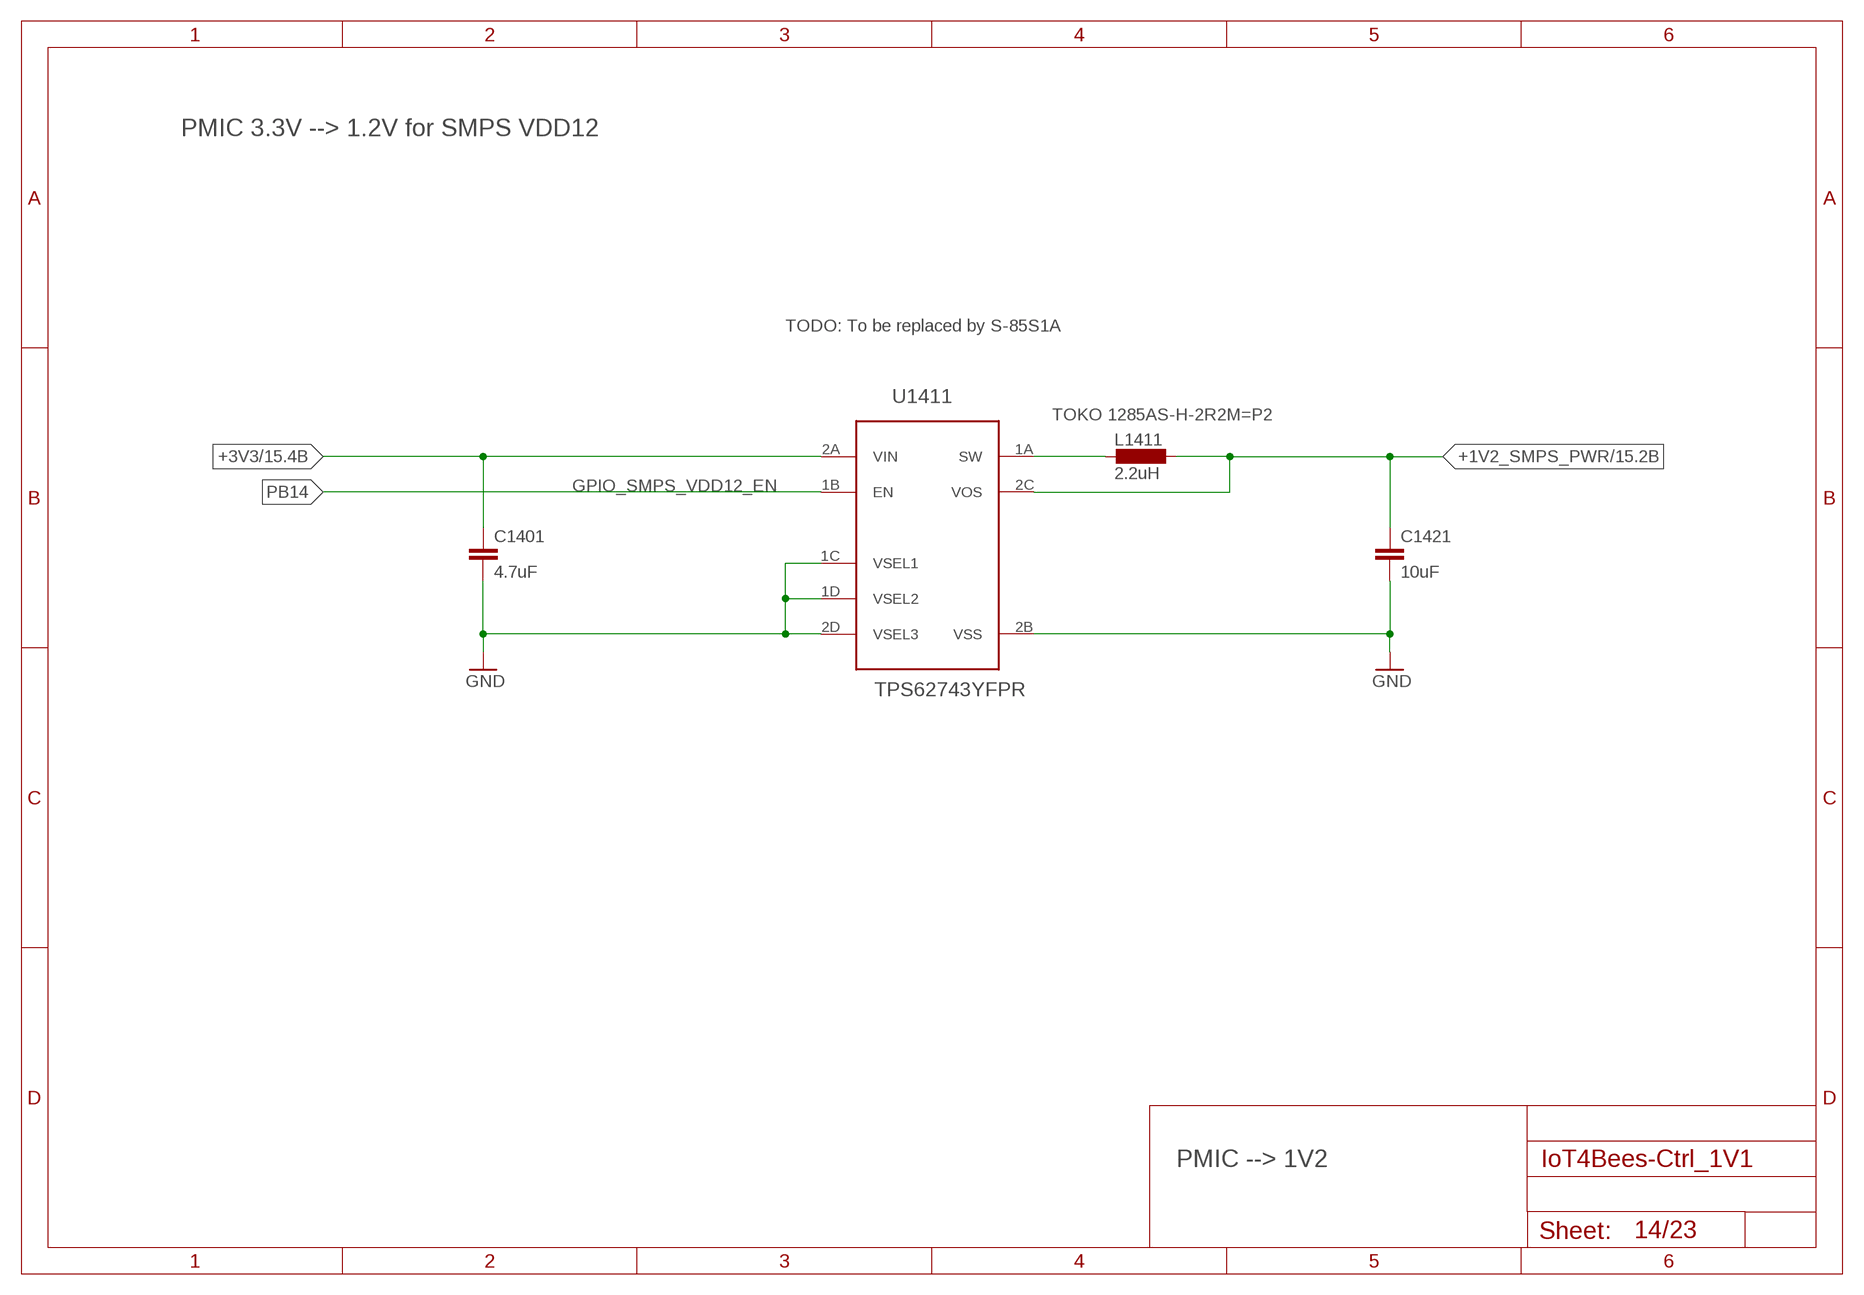
[diagram p13: schematic, sheet 14]
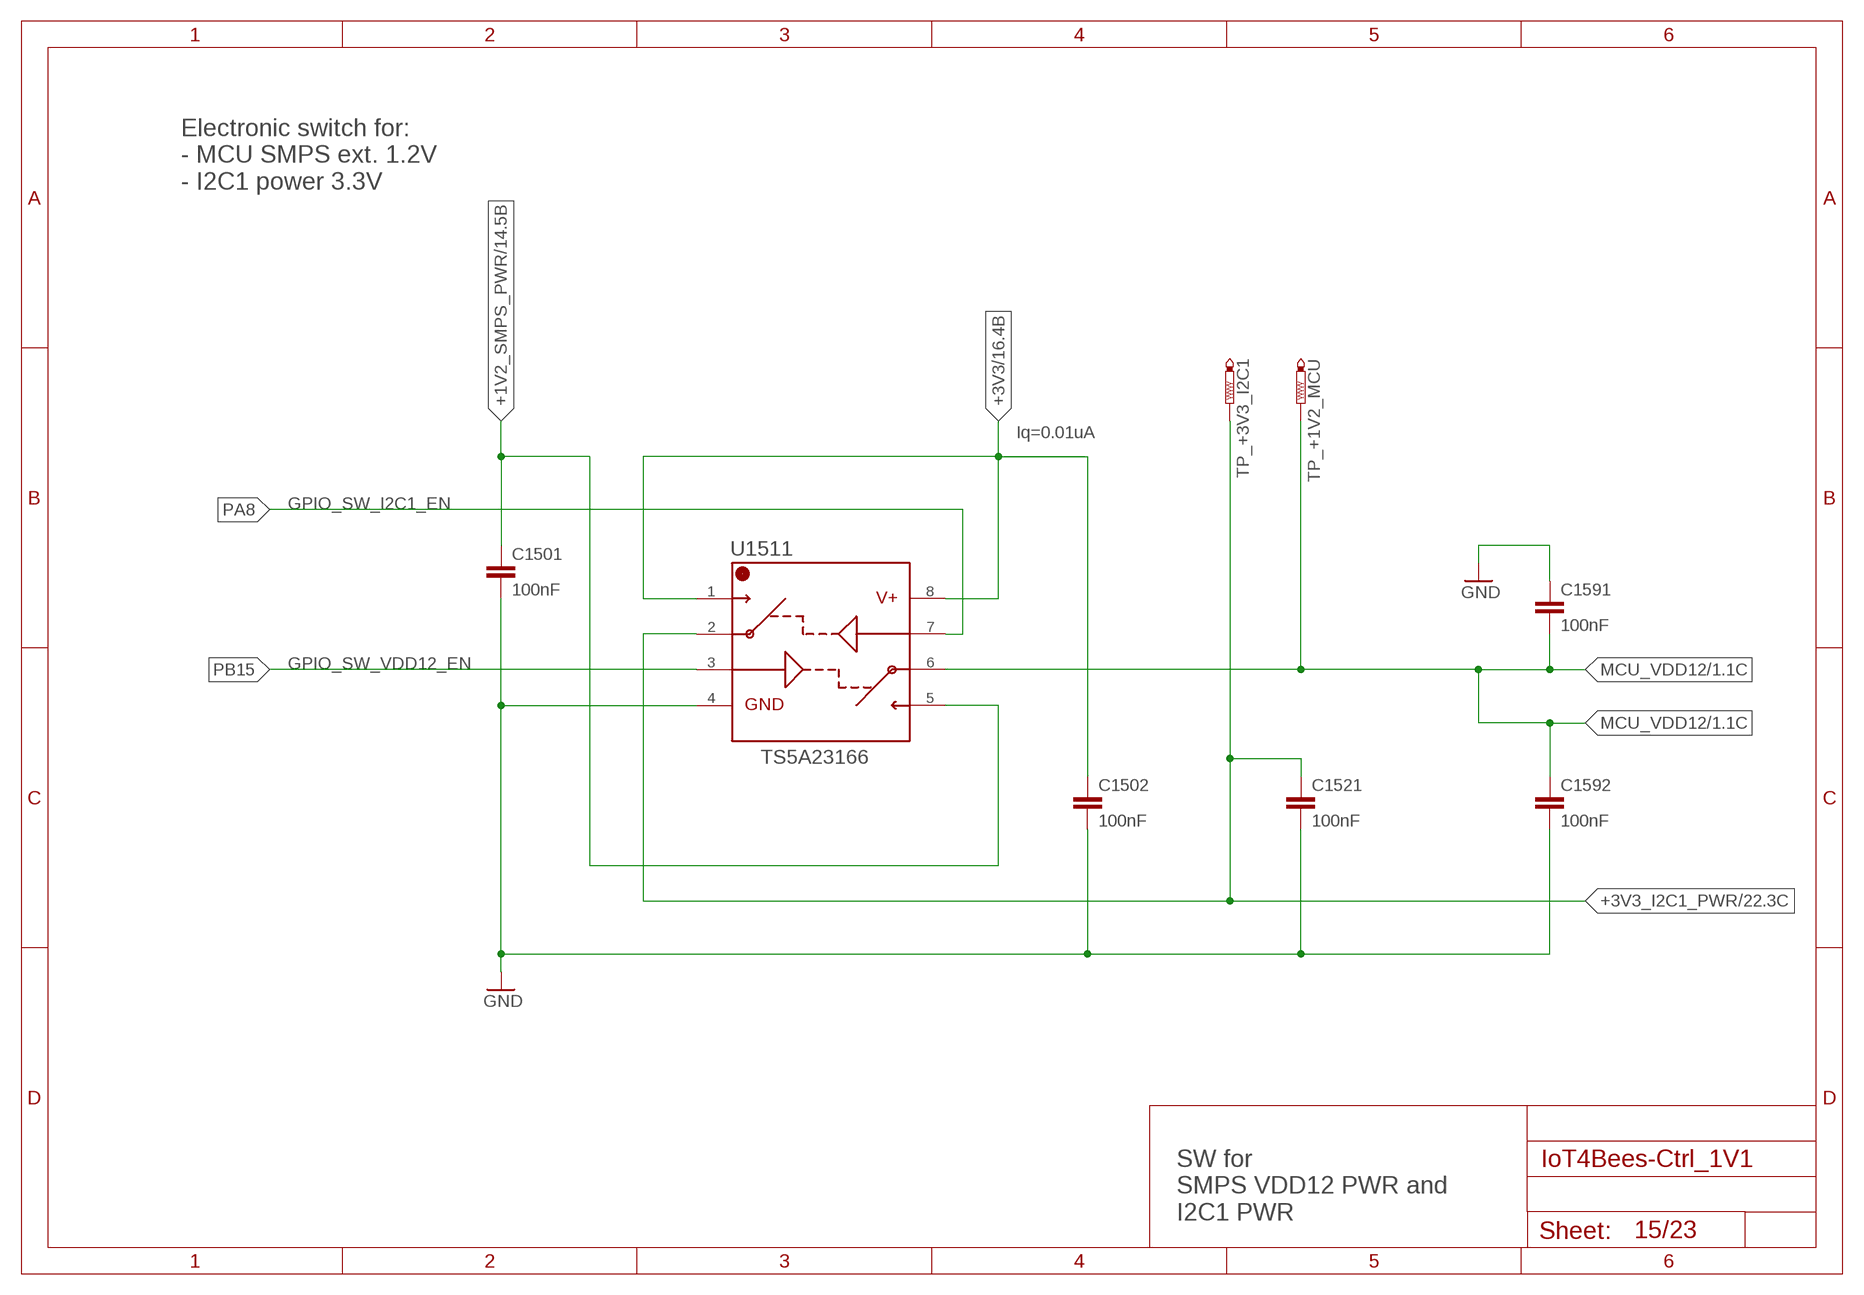
[diagram p14: schematic, sheet 15]
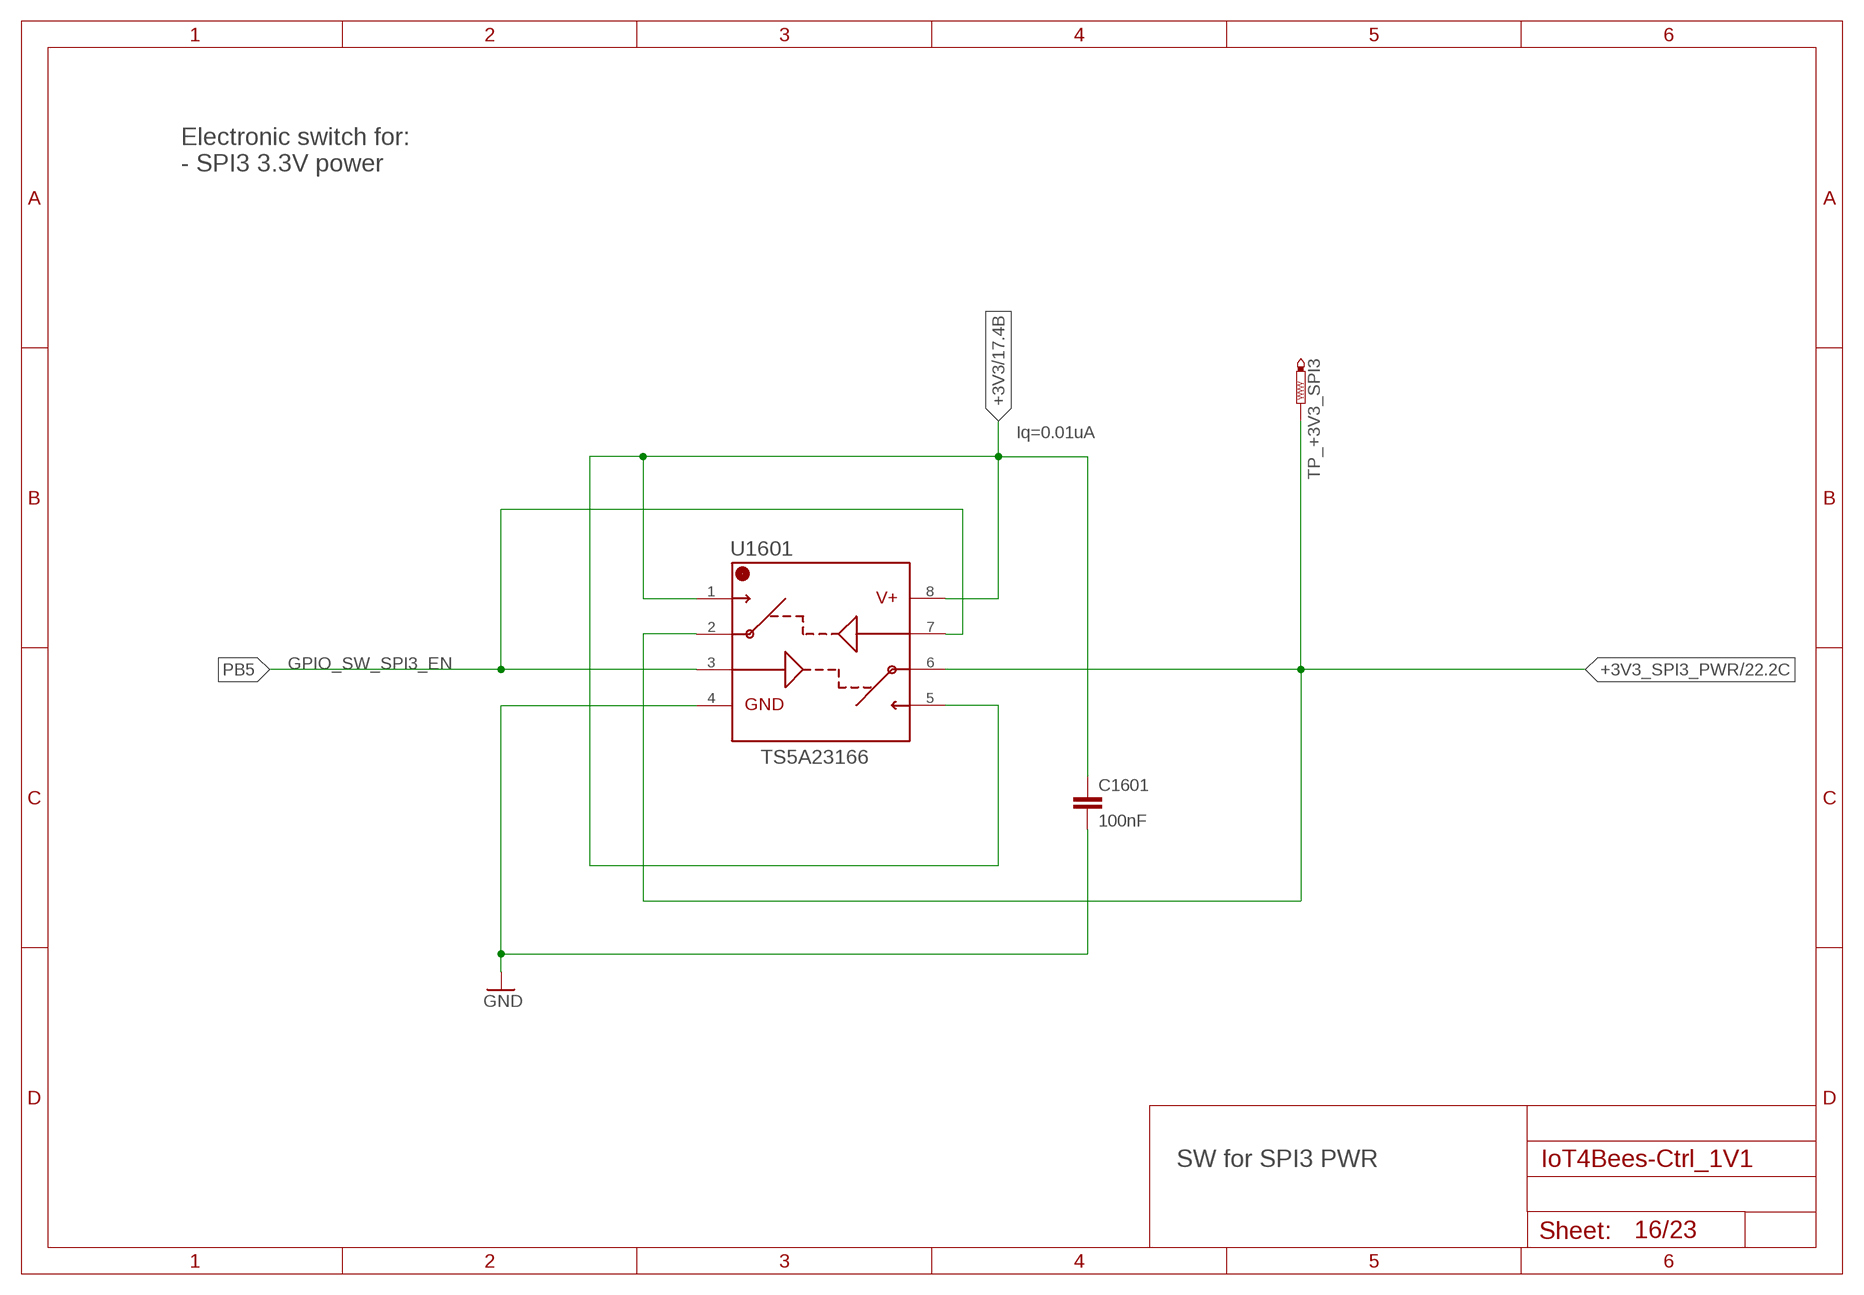
[diagram p15: schematic, sheet 16]
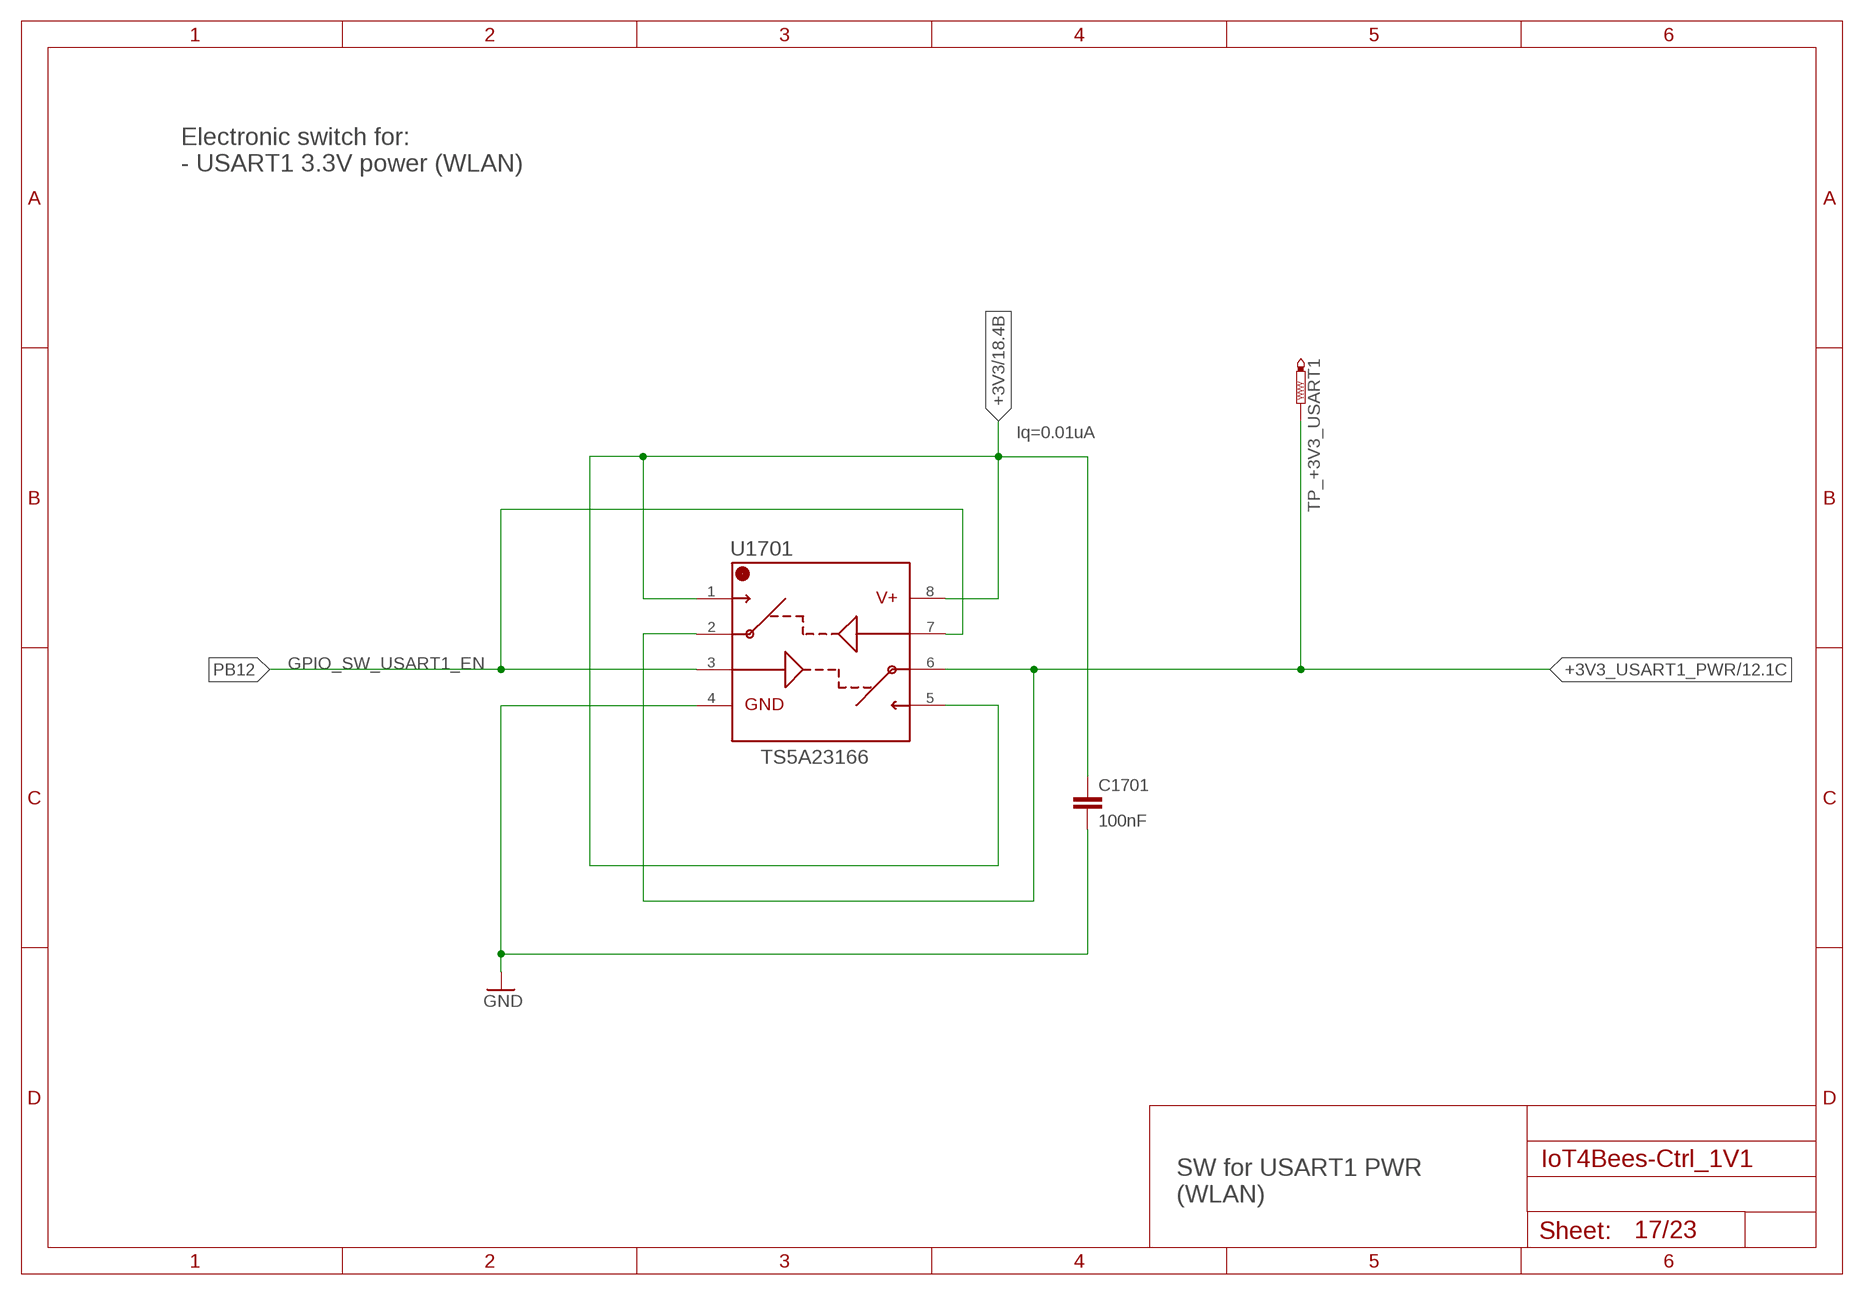
[diagram p16: schematic, sheet 17]
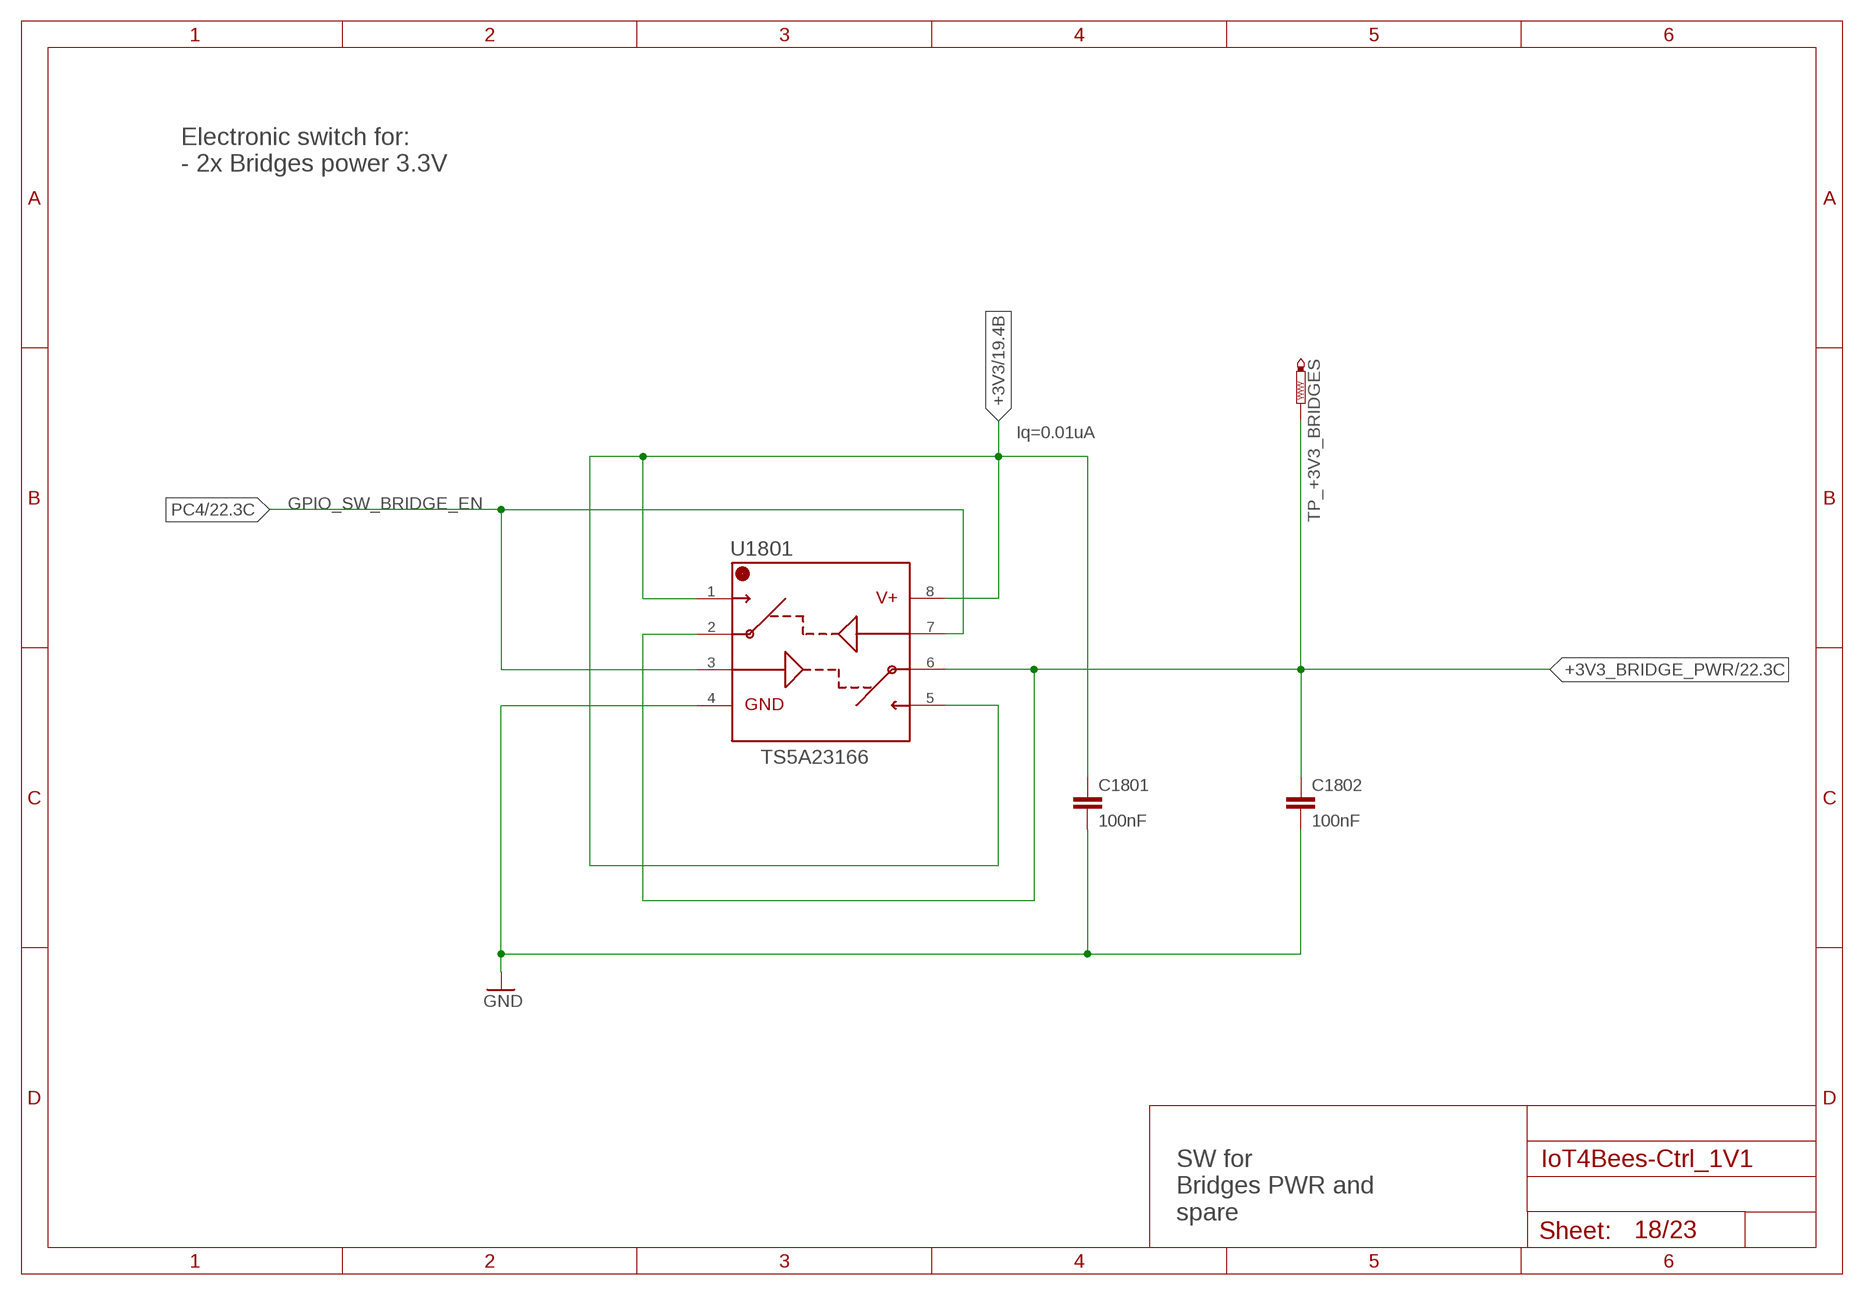
[diagram p17: schematic, sheet 18]
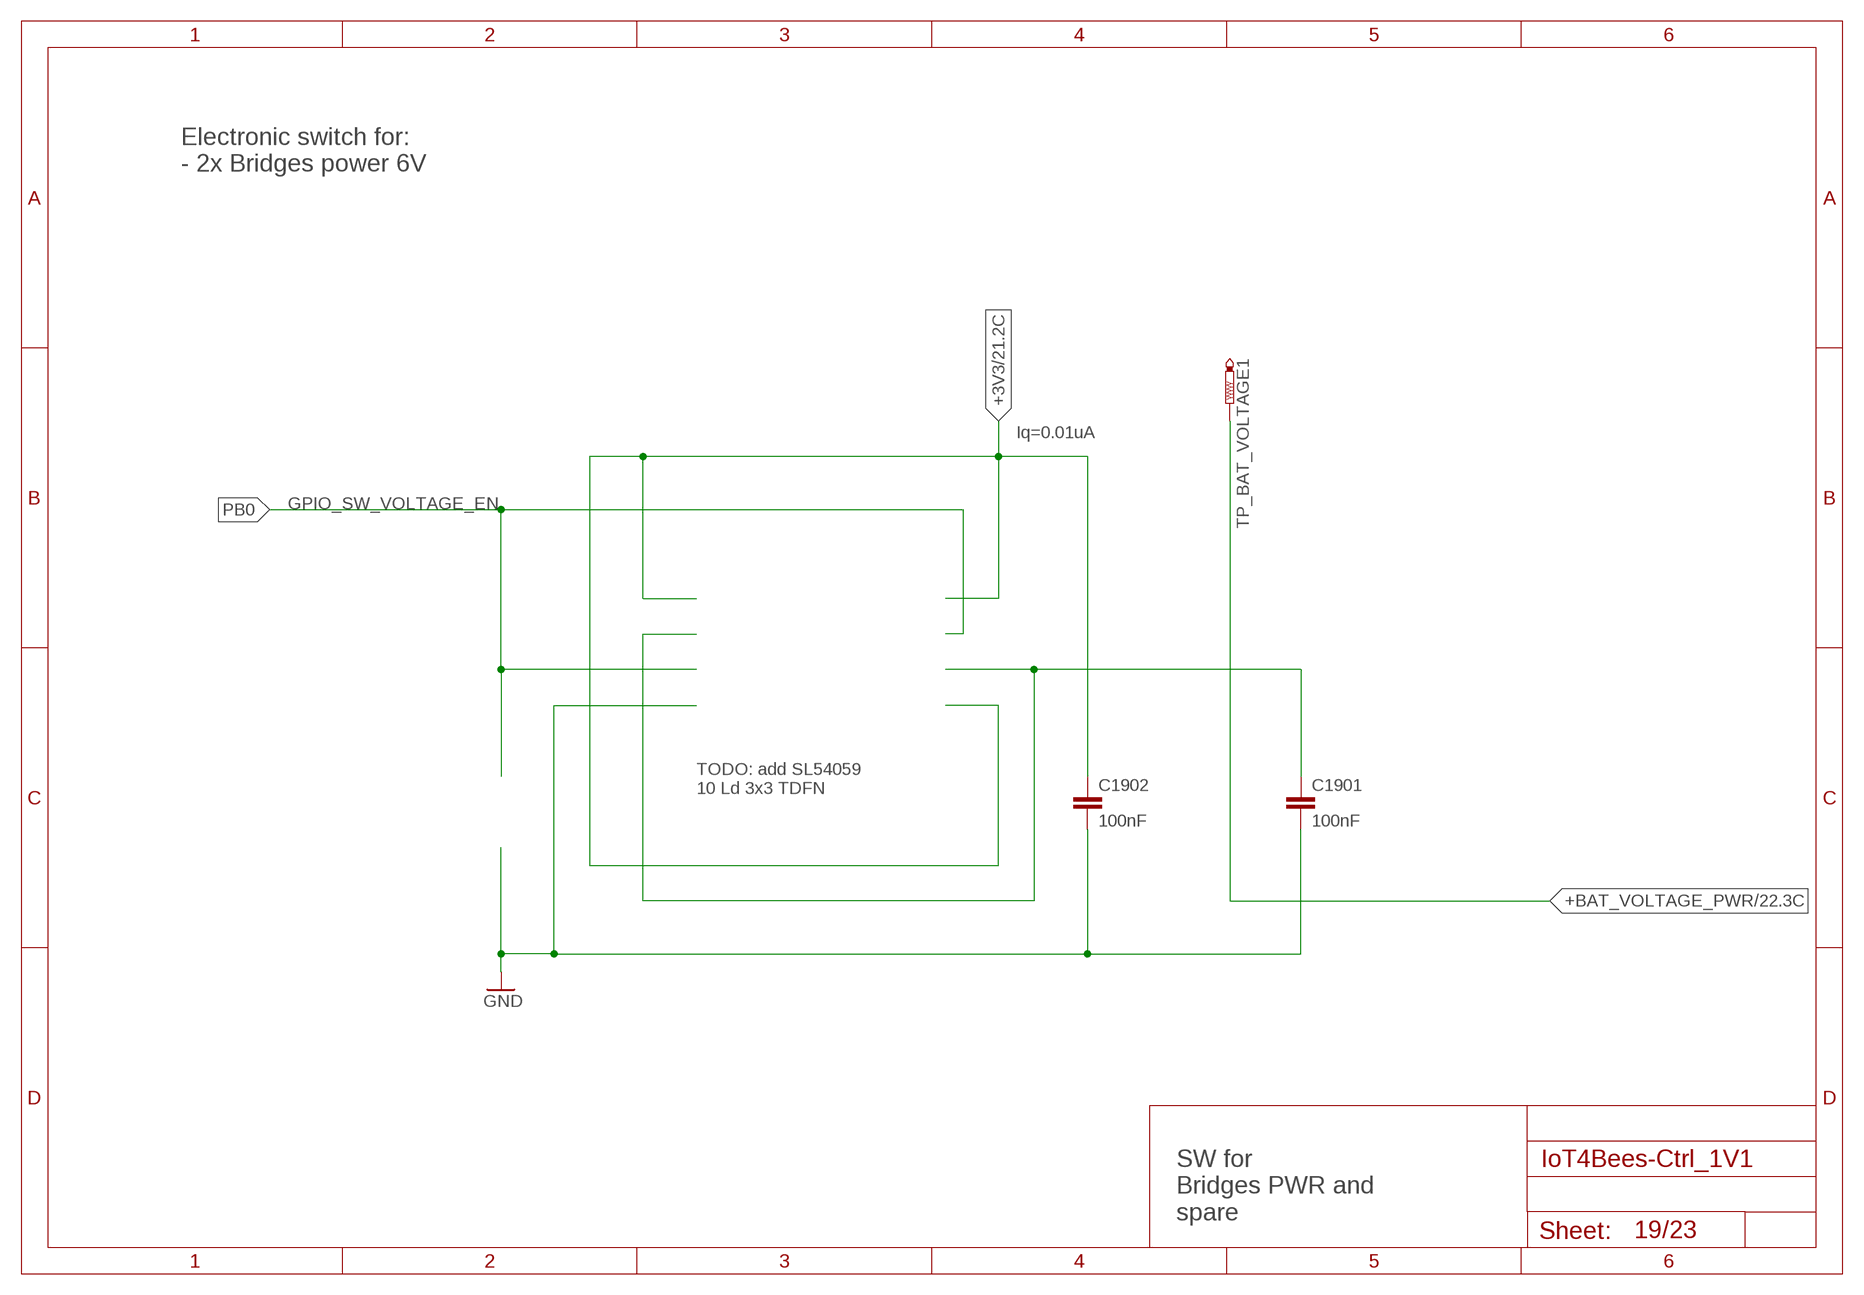
[diagram p18: schematic, sheet 19]
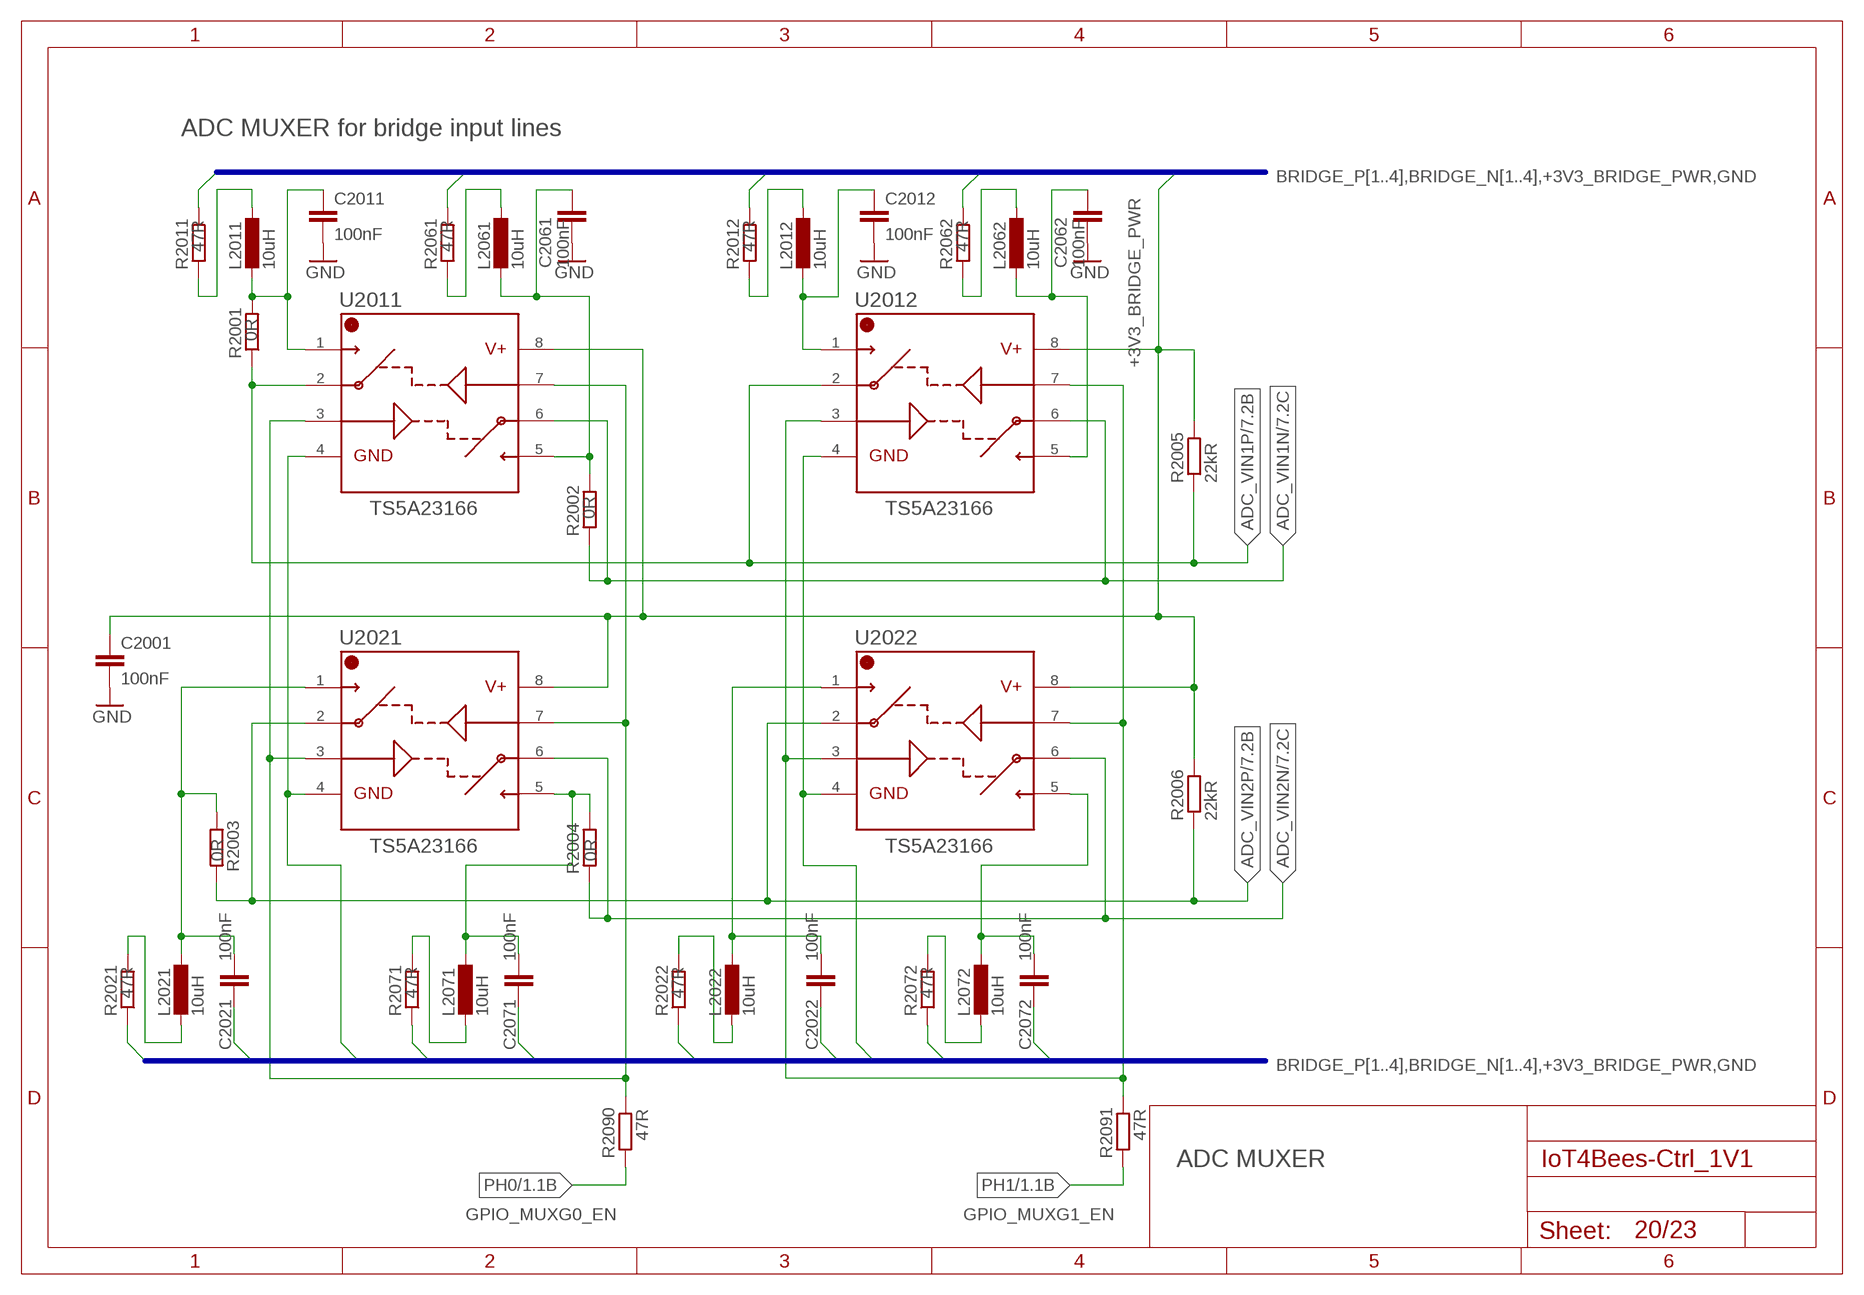
[diagram p19: schematic, sheet 20]
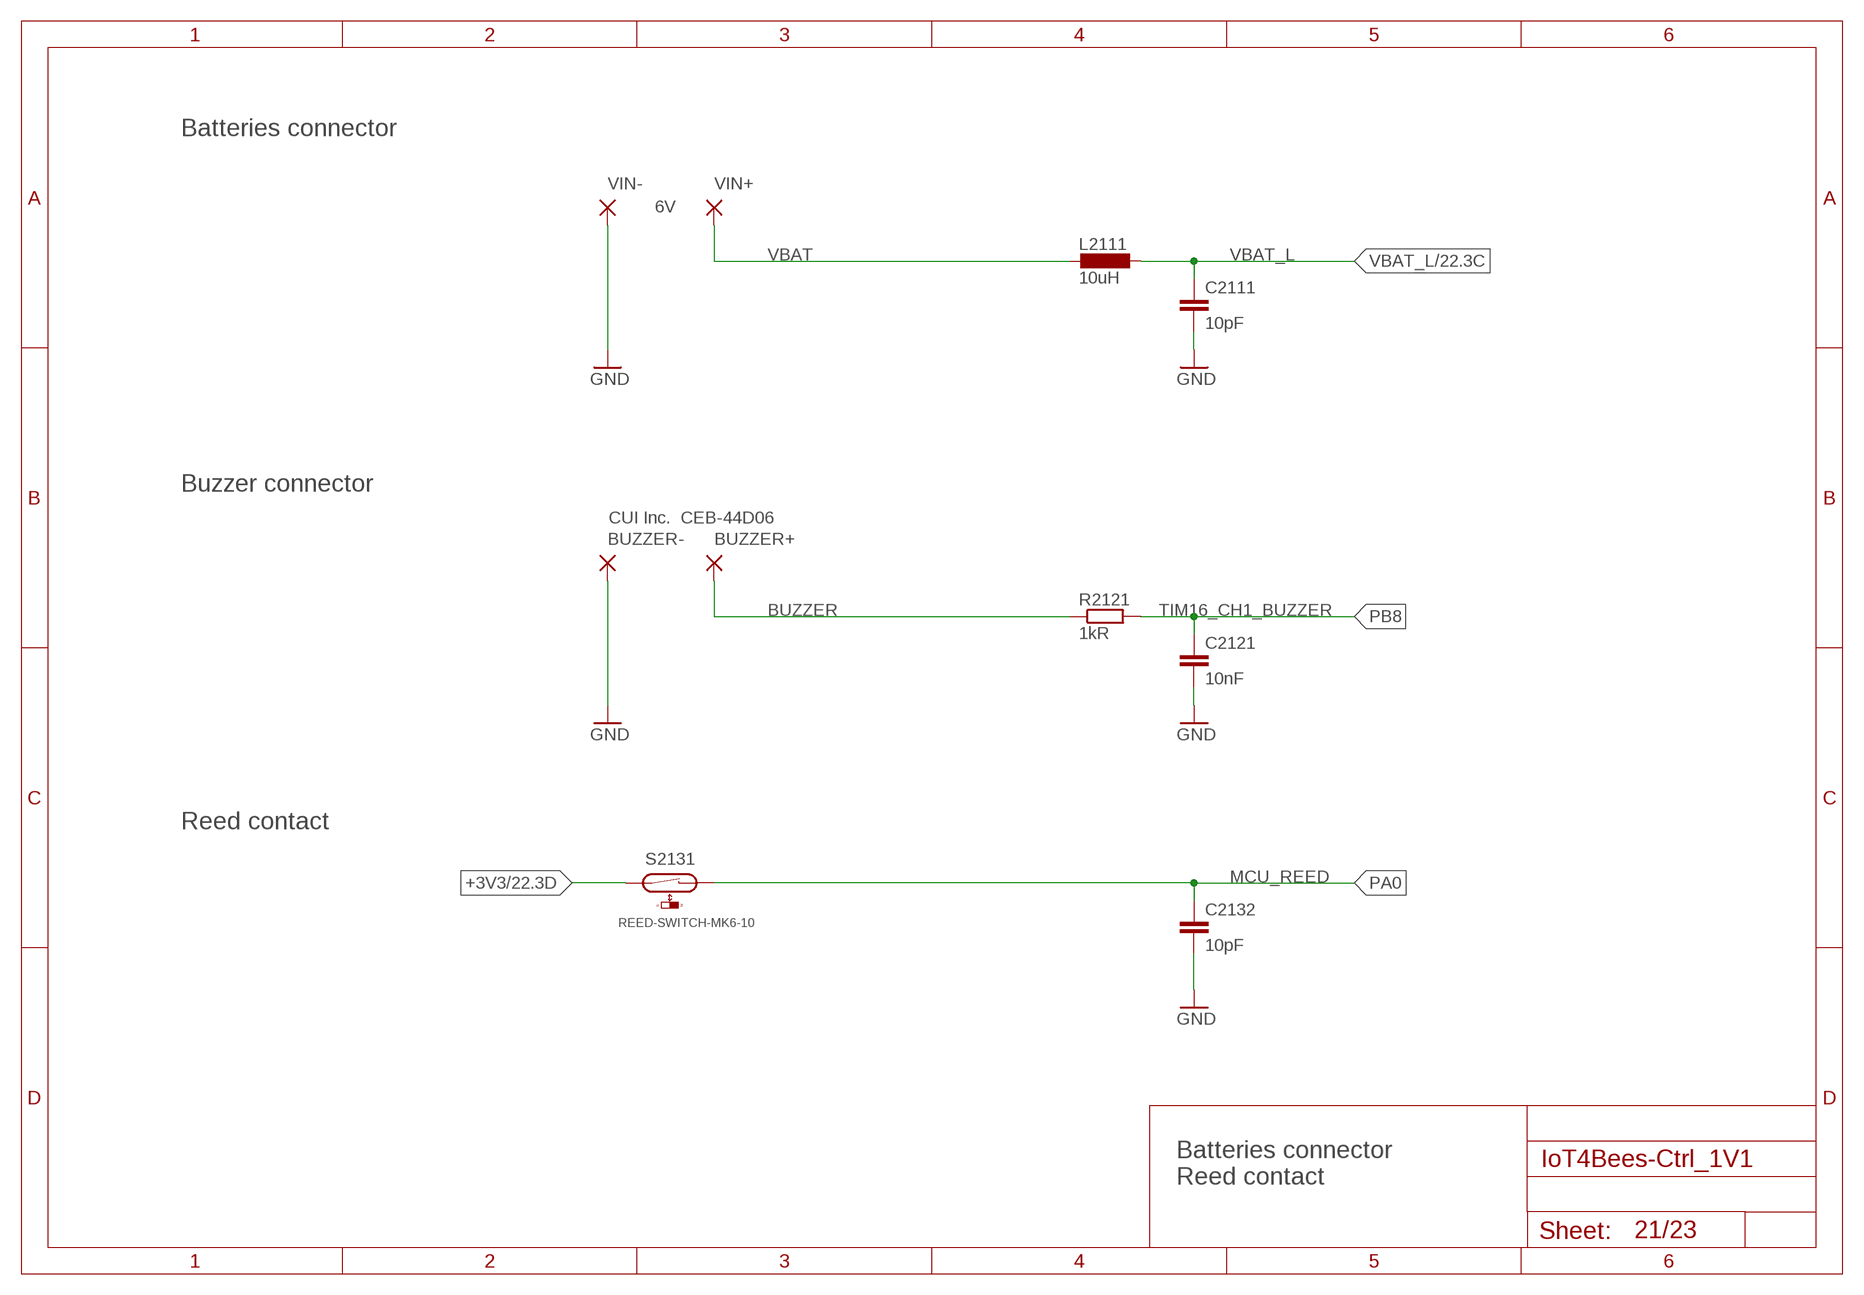
[diagram p20: schematic, sheet 21]
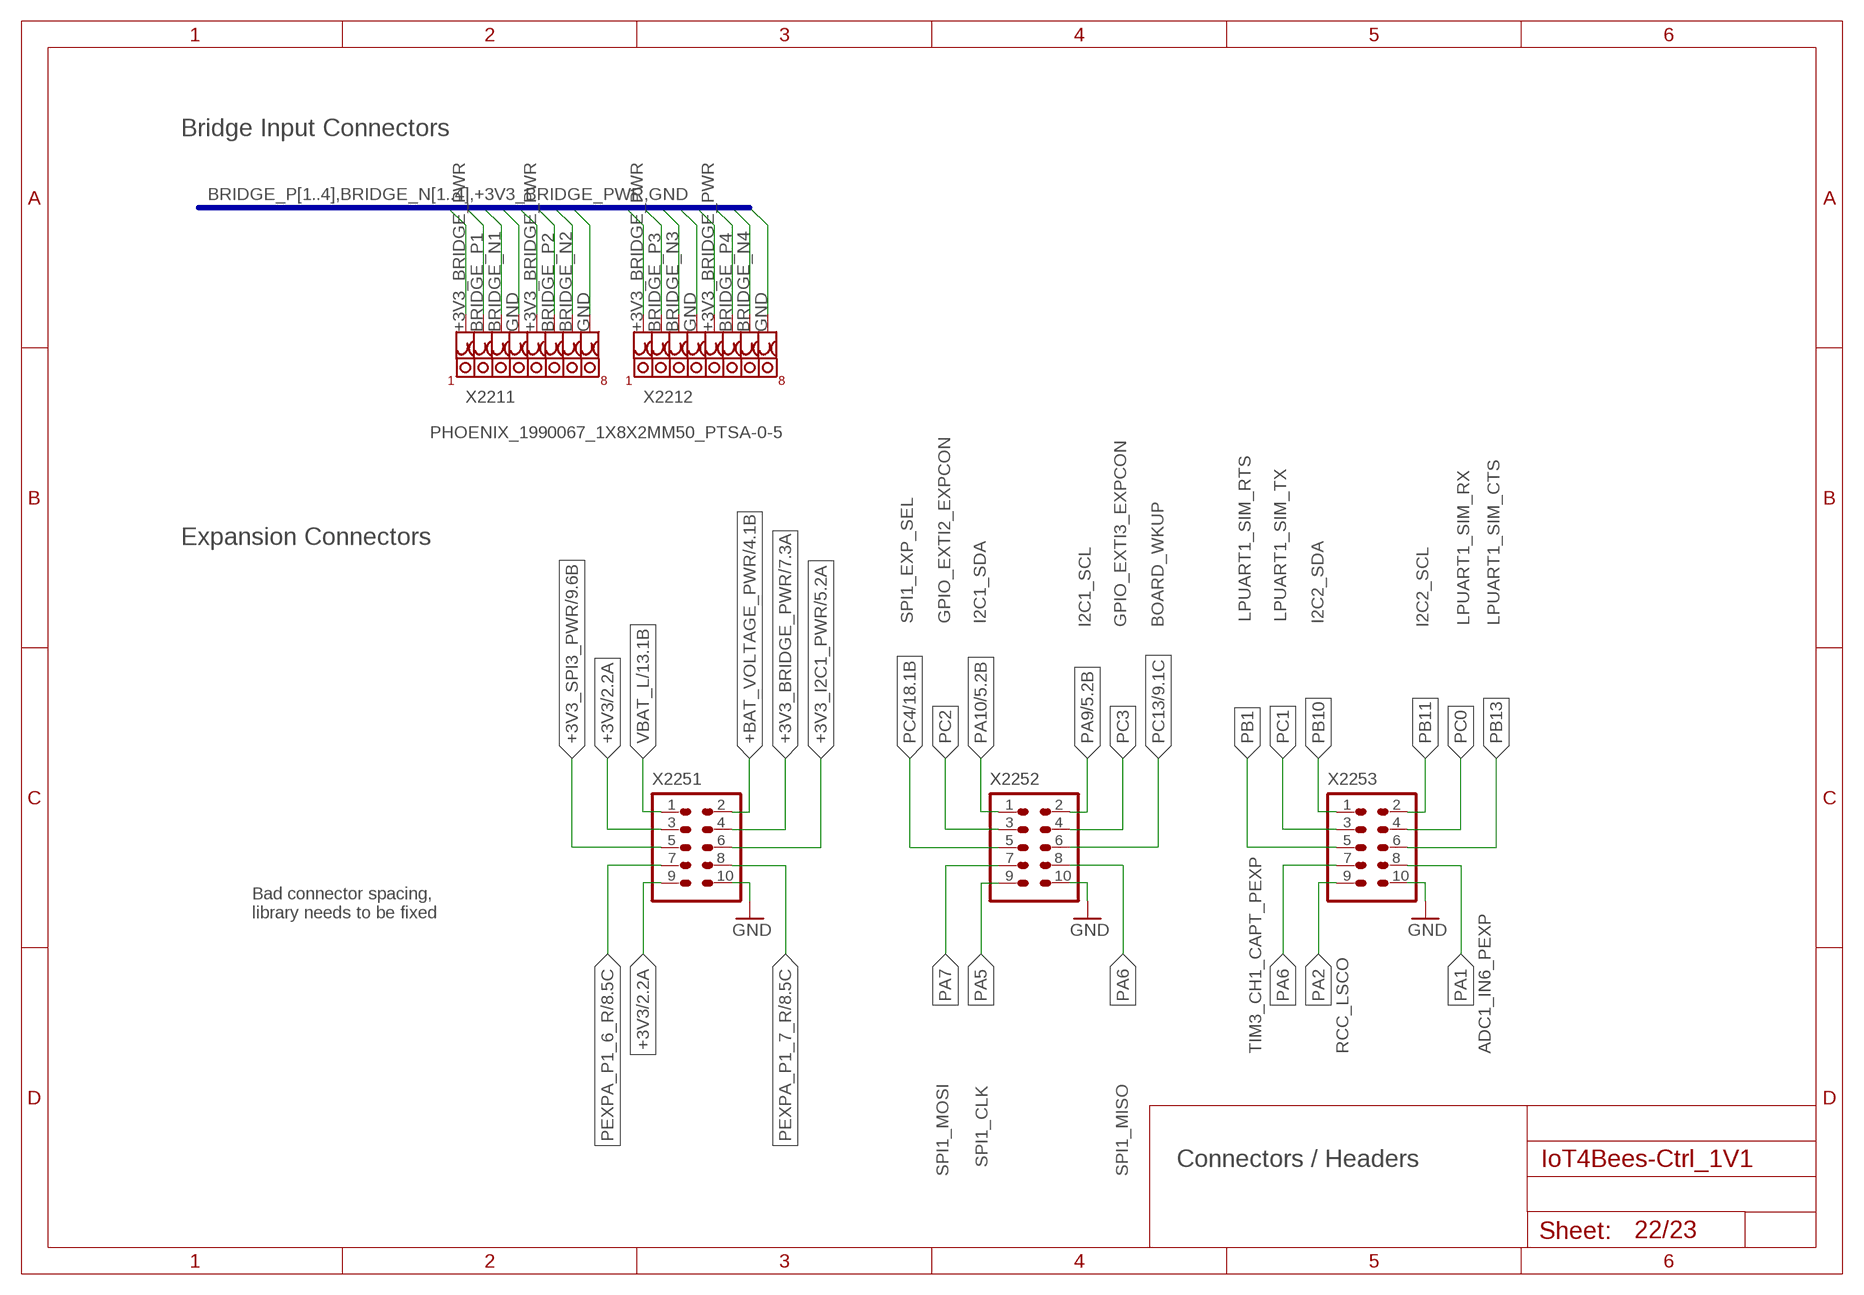
[diagram p21: schematic, sheet 22]
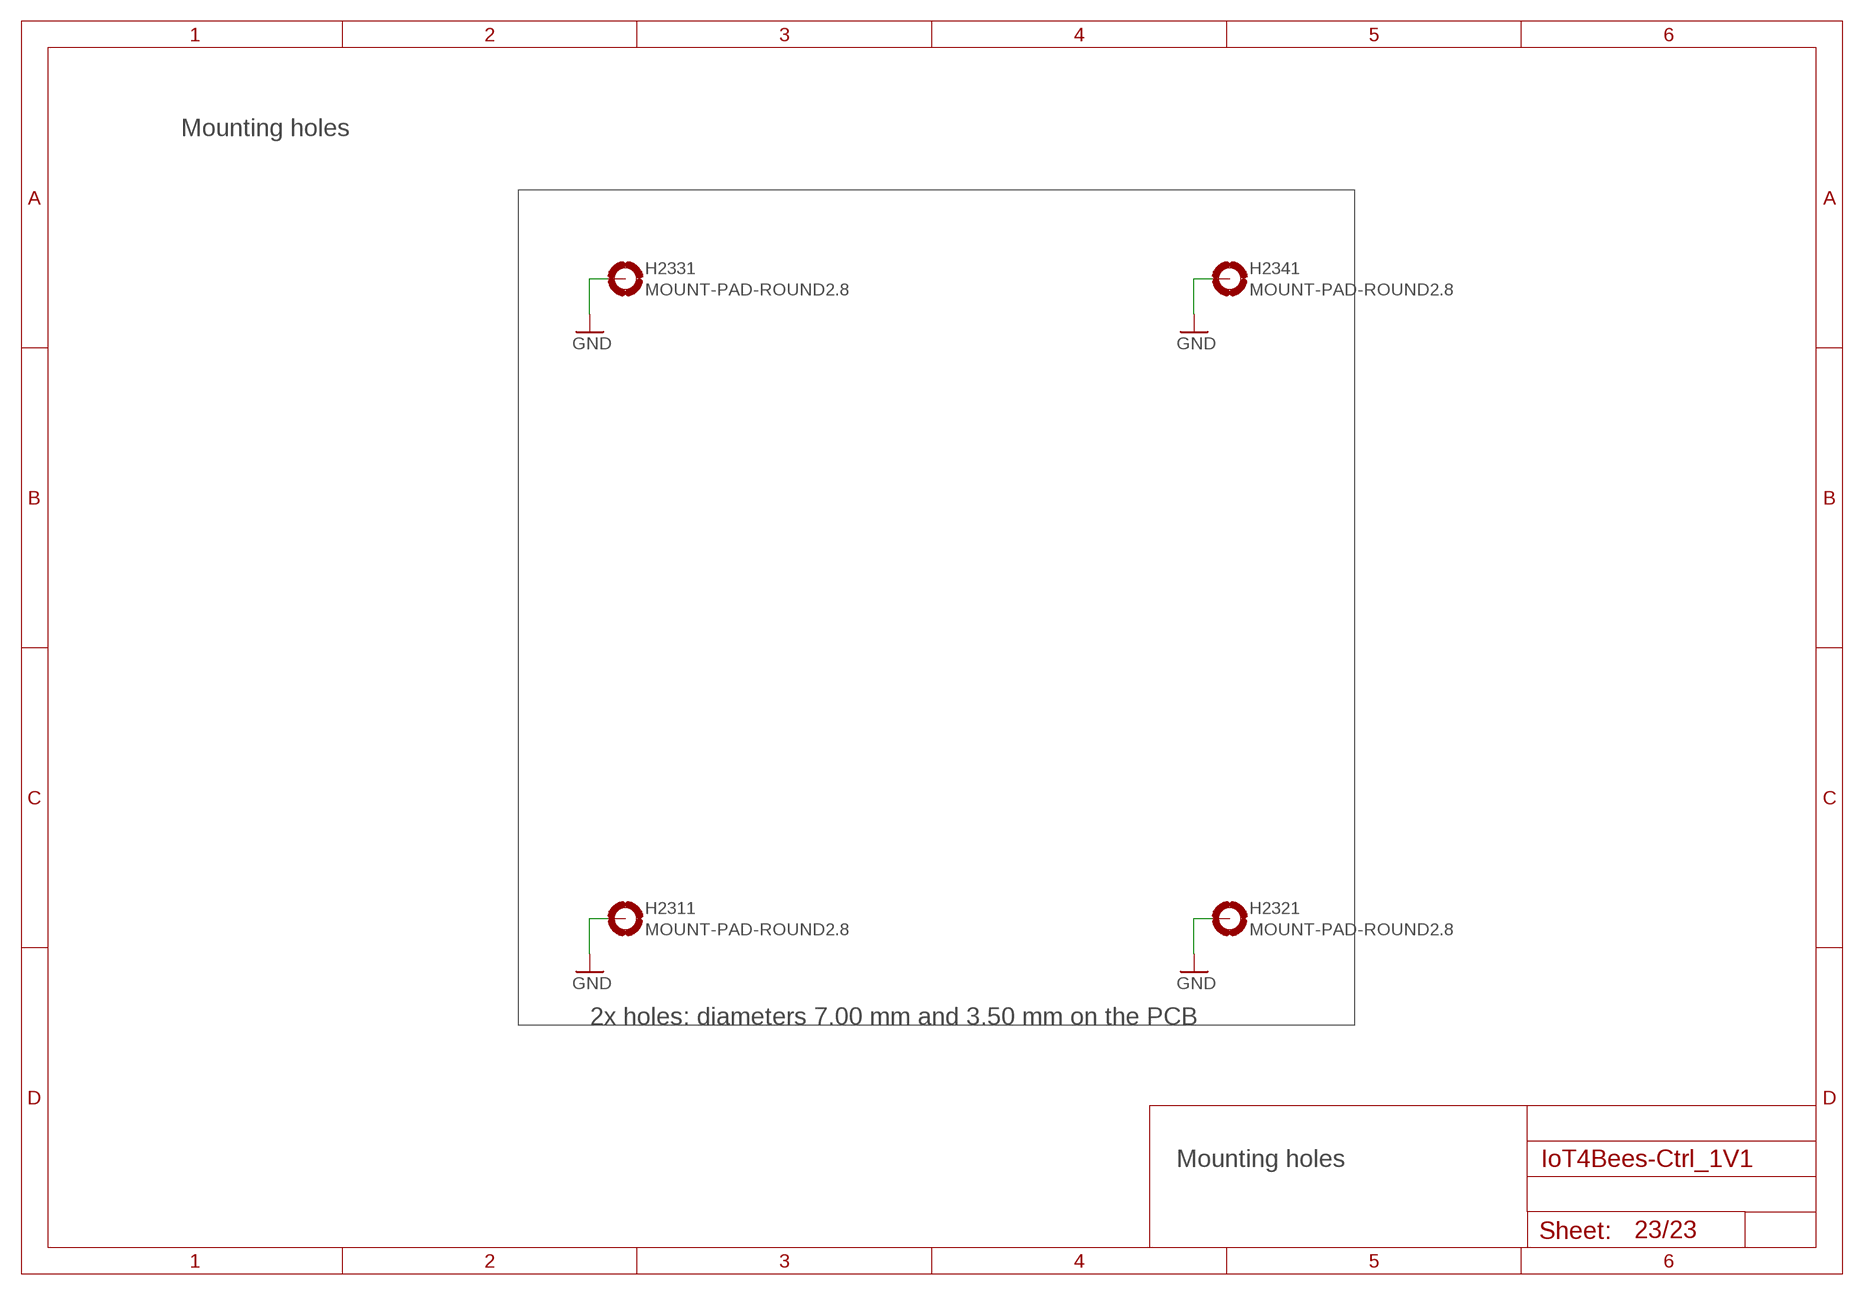
[diagram p22: schematic, sheet 23]

(export (version "E")
  (design (tool "Eeschema 10.0.6"))
  (components
    (comp (ref "C1301")
      (value "10uF")
      (footprint "eagle-import:C0603")
      (libsource (lib "eagle-import") (part "C-EUC0603"))
    )
    (comp (ref "C1321")
      (value "10uF")
      (footprint "eagle-import:C0603")
      (libsource (lib "eagle-import") (part "C-EUC0603"))
    )
    (comp (ref "L1311")
      (value "4.7uH")
      (footprint "eagle-import:L2520")
      (libsource (lib "eagle-import") (part "L-EUL2520"))
    )
    (comp (ref "U1311")
      (value "TPS62745DSSR")
      (footprint "eagle-import:WSON-12")
      (libsource (lib "eagle-import") (part "TPS62745"))
    )
    (comp (ref "C0801")
      (value "100nF")
      (footprint "eagle-import:C0402")
      (libsource (lib "eagle-import") (part "C-EUC0402"))
    )
    (comp (ref "R0802")
      (value "100kR")
      (footprint "eagle-import:R0402")
      (libsource (lib "eagle-import") (part "R-EU_R0402"))
    )
    (comp (ref "R0811")
      (value "3R")
      (footprint "eagle-import:R0402")
      (libsource (lib "eagle-import") (part "R-EU_R0402"))
    )
    (comp (ref "U0811")
      (value "PCAL6416APW")
      (footprint "eagle-import:TSSOP24_SOT355-1")
      (libsource (lib "eagle-import") (part "PCAL6416APW"))
    )
    (comp (ref "C1501")
      (value "100nF")
      (footprint "eagle-import:C0402")
      (libsource (lib "eagle-import") (part "C-EUC0402"))
    )
    (comp (ref "C1502")
      (value "100nF")
      (footprint "eagle-import:C0402")
      (libsource (lib "eagle-import") (part "C-EUC0402"))
    )
    (comp (ref "C1521")
      (value "100nF")
      (footprint "eagle-import:C0402")
      (libsource (lib "eagle-import") (part "C-EUC0402"))
    )
    (comp (ref "C1591")
      (value "100nF")
      (footprint "eagle-import:C0402")
      (libsource (lib "eagle-import") (part "C-EUC0402"))
    )
    (comp (ref "C1592")
      (value "100nF")
      (footprint "eagle-import:C0402")
      (libsource (lib "eagle-import") (part "C-EUC0402"))
    )
    (comp (ref "TP_+1V2_MCU")
      (value "PTR1TP06R")
      (footprint "eagle-import:TP06R")
      (libsource (lib "eagle-import") (part "PTR1TP06R"))
    )
    (comp (ref "TP_+3V3_I2C1")
      (value "PTR1TP06R")
      (footprint "eagle-import:TP06R")
      (libsource (lib "eagle-import") (part "PTR1TP06R"))
    )
    (comp (ref "U1511")
      (value "TS5A23166")
      (footprint "eagle-import:R-PDSO-G8")
      (libsource (lib "eagle-import") (part "TS5A23166"))
    )
    (comp (ref "C0401")
      (value "100nF")
      (footprint "eagle-import:C0402")
      (libsource (lib "eagle-import") (part "C-EUC0402"))
    )
    (comp (ref "C0402")
      (value "100nF")
      (footprint "eagle-import:C0402")
      (libsource (lib "eagle-import") (part "C-EUC0402"))
    )
    (comp (ref "C0403")
      (value "100nF")
      (footprint "eagle-import:C0402")
      (libsource (lib "eagle-import") (part "C-EUC0402"))
    )
    (comp (ref "C0410")
      (value "4.7uF")
      (footprint "eagle-import:C0603")
      (libsource (lib "eagle-import") (part "C-EUC0603"))
    )
    (comp (ref "C0412")
      (value "10nF")
      (footprint "eagle-import:C0402")
      (libsource (lib "eagle-import") (part "C-EUC0402"))
    )
    (comp (ref "C0413")
      (value "1uF")
      (footprint "eagle-import:C0402")
      (libsource (lib "eagle-import") (part "C-EUC0402"))
    )
    (comp (ref "C0451")
      (value "47uF")
      (footprint "eagle-import:C0805")
      (libsource (lib "eagle-import") (part "C-EUC0805"))
    )
    (comp (ref "C0461")
      (value "100nF")
      (footprint "eagle-import:C0402")
      (libsource (lib "eagle-import") (part "C-EUC0402"))
    )
    (comp (ref "L0411")
      (value "10uH")
      (footprint "eagle-import:L0603")
      (libsource (lib "eagle-import") (part "L-EUL0603"))
    )
    (comp (ref "R0401")
      (value "0R")
      (footprint "eagle-import:R0402")
      (libsource (lib "eagle-import") (part "R-EU_R0402"))
    )
    (comp (ref "R0421")
      (value "0R")
      (footprint "eagle-import:R0402")
      (libsource (lib "eagle-import") (part "R-EU_R0402"))
    )
    (comp (ref "R0441")
      (value "0R")
      (footprint "eagle-import:R0402")
      (libsource (lib "eagle-import") (part "R-EU_R0402"))
    )
    (comp (ref "R0461")
      (value "47kR")
      (footprint "eagle-import:R0402")
      (libsource (lib "eagle-import") (part "R-EU_R0402"))
    )
    (comp (ref "R0462")
      (value "100kR")
      (footprint "eagle-import:R0402")
      (libsource (lib "eagle-import") (part "R-EU_R0402"))
    )
    (comp (ref "TP_VBAT")
      (value "PTR1TP06R")
      (footprint "eagle-import:TP06R")
      (libsource (lib "eagle-import") (part "PTR1TP06R"))
    )
    (comp (ref "H2311")
      (value "MOUNT-PAD-ROUND2.8")
      (footprint "eagle-import:2,8-PAD")
      (libsource (lib "eagle-import") (part "MOUNT-PAD-ROUND2.8"))
    )
    (comp (ref "H2321")
      (value "MOUNT-PAD-ROUND2.8")
      (footprint "eagle-import:2,8-PAD")
      (libsource (lib "eagle-import") (part "MOUNT-PAD-ROUND2.8"))
    )
    (comp (ref "H2331")
      (value "MOUNT-PAD-ROUND2.8")
      (footprint "eagle-import:2,8-PAD")
      (libsource (lib "eagle-import") (part "MOUNT-PAD-ROUND2.8"))
    )
    (comp (ref "H2341")
      (value "MOUNT-PAD-ROUND2.8")
      (footprint "eagle-import:2,8-PAD")
      (libsource (lib "eagle-import") (part "MOUNT-PAD-ROUND2.8"))
    )
    (comp (ref "U0101")
      (value "STM32L452RET_64PIN_SMPS")
      (footprint "eagle-import:LQFP64")
      (libsource (lib "eagle-import") (part "STM32L452RET_64PIN_SMPS"))
    )
    (comp (ref "C1601")
      (value "100nF")
      (footprint "eagle-import:C0402")
      (libsource (lib "eagle-import") (part "C-EUC0402"))
    )
    (comp (ref "TP_+3V3_SPI3")
      (value "PTR1TP06R")
      (footprint "eagle-import:TP06R")
      (libsource (lib "eagle-import") (part "PTR1TP06R"))
    )
    (comp (ref "U1601")
      (value "TS5A23166")
      (footprint "eagle-import:R-PDSO-G8")
      (libsource (lib "eagle-import") (part "TS5A23166"))
    )
    (comp (ref "C1001")
      (value "10uF")
      (footprint "eagle-import:C0603")
      (libsource (lib "eagle-import") (part "C-EUC0603"))
    )
    (comp (ref "C1002")
      (value "10nF")
      (footprint "eagle-import:C0402")
      (libsource (lib "eagle-import") (part "C-EUC0402"))
    )
    (comp (ref "C1003")
      (value "470nF")
      (footprint "eagle-import:C0402")
      (libsource (lib "eagle-import") (part "C-EUC0402"))
    )
    (comp (ref "C1004")
      (value "47pF")
      (footprint "eagle-import:C0402")
      (libsource (lib "eagle-import") (part "C-EUC0402"))
    )
    (comp (ref "C1005")
      (value "47nF")
      (footprint "eagle-import:C0402")
      (libsource (lib "eagle-import") (part "C-EUC0402"))
    )
    (comp (ref "C1006")
      (value "10nF")
      (footprint "eagle-import:C0402")
      (libsource (lib "eagle-import") (part "C-EUC0402"))
    )
    (comp (ref "C1063")
      (value "3.3pF")
      (footprint "eagle-import:C0402")
      (libsource (lib "eagle-import") (part "C-EUC0402"))
    )
    (comp (ref "C1064")
      (value "22pF")
      (footprint "eagle-import:C0402")
      (libsource (lib "eagle-import") (part "C-EUC0402"))
    )
    (comp (ref "C1065")
      (value "1.8pF")
      (footprint "eagle-import:C0402")
      (libsource (lib "eagle-import") (part "C-EUC0402"))
    )
    (comp (ref "C1066")
      (value "3.3pF")
      (footprint "eagle-import:C0402")
      (libsource (lib "eagle-import") (part "C-EUC0402"))
    )
    (comp (ref "C1067")
      (value "0.0pF")
      (footprint "eagle-import:C0402")
      (libsource (lib "eagle-import") (part "C-EUC0402"))
    )
    (comp (ref "C1071")
      (value "1nF")
      (footprint "eagle-import:C0402")
      (libsource (lib "eagle-import") (part "C-EUC0402"))
    )
    (comp (ref "C1072")
      (value "1nF")
      (footprint "eagle-import:C0402")
      (libsource (lib "eagle-import") (part "C-EUC0402"))
    )
    (comp (ref "C1081")
      (value "33pF")
      (footprint "eagle-import:C0402")
      (libsource (lib "eagle-import") (part "C-EUC0402"))
    )
    (comp (ref "C1082")
      (value "2.7pF")
      (footprint "eagle-import:C0402")
      (libsource (lib "eagle-import") (part "C-EUC0402"))
    )
    (comp (ref "C1083")
      (value "2.2pF")
      (footprint "eagle-import:C0402")
      (libsource (lib "eagle-import") (part "C-EUC0402"))
    )
    (comp (ref "C1091")
      (value "2.7pF")
      (footprint "eagle-import:C0402")
      (libsource (lib "eagle-import") (part "C-EUC0402"))
    )
    (comp (ref "C1092")
      (value "3.8pF")
      (footprint "eagle-import:C0402")
      (libsource (lib "eagle-import") (part "C-EUC0402"))
    )
    (comp (ref "C1093")
      (value "0pF")
      (footprint "eagle-import:C0402")
      (libsource (lib "eagle-import") (part "C-EUC0402"))
    )
    (comp (ref "L1001")
      (value "15uH")
      (footprint "eagle-import:L0805")
      (libsource (lib "eagle-import") (part "L-EUL0805"))
    )
    (comp (ref "L1002")
      (value "47nH")
      (footprint "eagle-import:L0603")
      (libsource (lib "eagle-import") (part "L-EUL0603"))
    )
    (comp (ref "L1062")
      (value "47nH")
      (footprint "eagle-import:L0603")
      (libsource (lib "eagle-import") (part "L-EUL0603"))
    )
    (comp (ref "L1063")
      (value "2.2nH")
      (footprint "eagle-import:L0603")
      (libsource (lib "eagle-import") (part "L-EUL0603"))
    )
    (comp (ref "L1064")
      (value "1.5nH")
      (footprint "eagle-import:L0603")
      (libsource (lib "eagle-import") (part "L-EUL0603"))
    )
    (comp (ref "L1082")
      (value "6.8nH")
      (footprint "eagle-import:L0603")
      (libsource (lib "eagle-import") (part "L-EUL0603"))
    )
    (comp (ref "L1091")
      (value "13nH")
      (footprint "eagle-import:L0603")
      (libsource (lib "eagle-import") (part "L-EUL0603"))
    )
    (comp (ref "Q1011")
      (value "ABM3B-32.0000MHZ")
      (footprint "eagle-import:ABM3B")
      (libsource (lib "eagle-import") (part "ABM3B-32.0000MHZ"))
    )
    (comp (ref "R1011")
      (value "3R")
      (footprint "eagle-import:R0402")
      (libsource (lib "eagle-import") (part "R-EU_R0402"))
    )
    (comp (ref "R1021")
      (value "3R")
      (footprint "eagle-import:R0402")
      (libsource (lib "eagle-import") (part "R-EU_R0402"))
    )
    (comp (ref "R1024")
      (value "3R")
      (footprint "eagle-import:R0402")
      (libsource (lib "eagle-import") (part "R-EU_R0402"))
    )
    (comp (ref "R1051")
      (value "47R")
      (footprint "eagle-import:R0402")
      (libsource (lib "eagle-import") (part "R-EU_R0402"))
    )
    (comp (ref "R1052")
      (value "47R")
      (footprint "eagle-import:R0402")
      (libsource (lib "eagle-import") (part "R-EU_R0402"))
    )
    (comp (ref "R1053")
      (value "47R")
      (footprint "eagle-import:R0402")
      (libsource (lib "eagle-import") (part "R-EU_R0402"))
    )
    (comp (ref "R1071")
      (value "47R")
      (footprint "eagle-import:R0402")
      (libsource (lib "eagle-import") (part "R-EU_R0402"))
    )
    (comp (ref "TP_SX_DIO1")
      (value "PTR1TP06R")
      (footprint "eagle-import:TP06R")
      (libsource (lib "eagle-import") (part "PTR1TP06R"))
    )
    (comp (ref "TP_SX_DIO2")
      (value "PTR1TP06R")
      (footprint "eagle-import:TP06R")
      (libsource (lib "eagle-import") (part "PTR1TP06R"))
    )
    (comp (ref "TP_SX_DIO3")
      (value "PTR1TP06R")
      (footprint "eagle-import:TP06R")
      (libsource (lib "eagle-import") (part "PTR1TP06R"))
    )
    (comp (ref "U1001")
      (value "SX1261IMLTRT")
      (footprint "eagle-import:QFN24-4X4-0P5-PAD")
      (libsource (lib "eagle-import") (part "SX1261"))
    )
    (comp (ref "U1071")
      (value "PE4259")
      (footprint "eagle-import:SC-70_6-LEAD_2X1MM25_0P65")
      (libsource (lib "eagle-import") (part "PE4259"))
    )
    (comp (ref "X1081")
      (value "ANTENNATINY")
      (footprint "eagle-import:SMA_UFL_PAD_TINY")
      (libsource (lib "eagle-import") (part "ANTENNATINY"))
    )
    (comp (ref "C0213")
      (value "100nF")
      (footprint "eagle-import:C0402")
      (libsource (lib "eagle-import") (part "C-EUC0402"))
    )
    (comp (ref "R0201")
      (value "220kR")
      (footprint "eagle-import:R0402")
      (libsource (lib "eagle-import") (part "R-EU_R0402"))
    )
    (comp (ref "R0202")
      (value "220kR")
      (footprint "eagle-import:R0402")
      (libsource (lib "eagle-import") (part "R-EU_R0402"))
    )
    (comp (ref "R0221")
      (value "33kR")
      (footprint "eagle-import:R0402")
      (libsource (lib "eagle-import") (part "R-EU_R0402"))
    )
    (comp (ref "S0212")
      (value "KSR223GLFG")
      (footprint "eagle-import:KSR223G_SMD_1POL")
      (libsource (lib "eagle-import") (part "KSR223G_SMD_1POL"))
    )
    (comp (ref "X0201")
      (value "FTSH-105-01-F-D-K")
      (footprint "eagle-import:2X05_1MM27_SHROUDED_CORTEX_JTAG_SWD")
      (libsource (lib "eagle-import") (part "2X05_1MM27_SHROUDED_CORTEX_JTAG_SWD{dblquote}"))
    )
    (comp (ref "X0222")
      (value "HEADER-1X2")
      (footprint "eagle-import:1X02")
      (libsource (lib "eagle-import") (part "HEADER-1X2"))
    )
    (comp (ref "C0601")
      (value "100nF")
      (footprint "eagle-import:C0402")
      (libsource (lib "eagle-import") (part "C-EUC0402"))
    )
    (comp (ref "U0611")
      (value "MR44V064BMAZAATL")
      (footprint "eagle-import:SOIC8_150MIL")
      (libsource (lib "eagle-import") (part "FEDR44V064B-02_FRAM_8K-8_I2C"))
    )
    (comp (ref "C1113")
      (value "100nF")
      (footprint "eagle-import:C0402")
      (libsource (lib "eagle-import") (part "C-EUC0402"))
    )
    (comp (ref "R1111")
      (value "3R")
      (footprint "eagle-import:R0402")
      (libsource (lib "eagle-import") (part "R-EU_R0402"))
    )
    (comp (ref "R1112")
      (value "100kR")
      (footprint "eagle-import:R0402")
      (libsource (lib "eagle-import") (part "R-EU_R0402"))
    )
    (comp (ref "U1111")
      (value "PCAL6416APW")
      (footprint "eagle-import:TSSOP24_SOT355-1")
      (libsource (lib "eagle-import") (part "PCAL6416APW"))
    )
    (comp (ref "C1201")
      (value "10uF")
      (footprint "eagle-import:C0603")
      (libsource (lib "eagle-import") (part "C-EUC0603"))
    )
    (comp (ref "C1202")
      (value "10nF")
      (footprint "eagle-import:C0402")
      (libsource (lib "eagle-import") (part "C-EUC0402"))
    )
    (comp (ref "R1257")
      (value "47R")
      (footprint "eagle-import:R0402")
      (libsource (lib "eagle-import") (part "R-EU_R0402"))
    )
    (comp (ref "R1266")
      (value "47R")
      (footprint "eagle-import:R0402")
      (libsource (lib "eagle-import") (part "R-EU_R0402"))
    )
    (comp (ref "R1271")
      (value "47R")
      (footprint "eagle-import:R0402")
      (libsource (lib "eagle-import") (part "R-EU_R0402"))
    )
    (comp (ref "R1272")
      (value "47R")
      (footprint "eagle-import:R0402")
      (libsource (lib "eagle-import") (part "R-EU_R0402"))
    )
    (comp (ref "U1211")
      (value "ESP-12F__2P00_24MM-X-16MM")
      (footprint "eagle-import:ESP-12F__2P00_24MM-X-16MM")
      (libsource (lib "eagle-import") (part "ESP-12F__2P00_24MM-X-16MM"))
    )
    (comp (ref "C2001")
      (value "100nF")
      (footprint "eagle-import:C0402")
      (libsource (lib "eagle-import") (part "C-EUC0402"))
    )
    (comp (ref "C2011")
      (value "100nF")
      (footprint "eagle-import:C0402")
      (libsource (lib "eagle-import") (part "C-EUC0402"))
    )
    (comp (ref "C2012")
      (value "100nF")
      (footprint "eagle-import:C0402")
      (libsource (lib "eagle-import") (part "C-EUC0402"))
    )
    (comp (ref "C2021")
      (value "100nF")
      (footprint "eagle-import:C0402")
      (libsource (lib "eagle-import") (part "C-EUC0402"))
    )
    (comp (ref "C2022")
      (value "100nF")
      (footprint "eagle-import:C0402")
      (libsource (lib "eagle-import") (part "C-EUC0402"))
    )
    (comp (ref "C2061")
      (value "100nF")
      (footprint "eagle-import:C0402")
      (libsource (lib "eagle-import") (part "C-EUC0402"))
    )
    (comp (ref "C2062")
      (value "100nF")
      (footprint "eagle-import:C0402")
      (libsource (lib "eagle-import") (part "C-EUC0402"))
    )
    (comp (ref "C2071")
      (value "100nF")
      (footprint "eagle-import:C0402")
      (libsource (lib "eagle-import") (part "C-EUC0402"))
    )
    (comp (ref "C2072")
      (value "100nF")
      (footprint "eagle-import:C0402")
      (libsource (lib "eagle-import") (part "C-EUC0402"))
    )
    (comp (ref "L2011")
      (value "10uH")
      (footprint "eagle-import:L0603")
      (libsource (lib "eagle-import") (part "L-EUL0603"))
    )
    (comp (ref "L2012")
      (value "10uH")
      (footprint "eagle-import:L0603")
      (libsource (lib "eagle-import") (part "L-EUL0603"))
    )
    (comp (ref "L2021")
      (value "10uH")
      (footprint "eagle-import:L0603")
      (libsource (lib "eagle-import") (part "L-EUL0603"))
    )
    (comp (ref "L2022")
      (value "10uH")
      (footprint "eagle-import:L0603")
      (libsource (lib "eagle-import") (part "L-EUL0603"))
    )
    (comp (ref "L2061")
      (value "10uH")
      (footprint "eagle-import:L0603")
      (libsource (lib "eagle-import") (part "L-EUL0603"))
    )
    (comp (ref "L2062")
      (value "10uH")
      (footprint "eagle-import:L0603")
      (libsource (lib "eagle-import") (part "L-EUL0603"))
    )
    (comp (ref "L2071")
      (value "10uH")
      (footprint "eagle-import:L0603")
      (libsource (lib "eagle-import") (part "L-EUL0603"))
    )
    (comp (ref "L2072")
      (value "10uH")
      (footprint "eagle-import:L0603")
      (libsource (lib "eagle-import") (part "L-EUL0603"))
    )
    (comp (ref "R2001")
      (value "0R")
      (footprint "eagle-import:R0402")
      (libsource (lib "eagle-import") (part "R-EU_R0402"))
    )
    (comp (ref "R2002")
      (value "0R")
      (footprint "eagle-import:R0402")
      (libsource (lib "eagle-import") (part "R-EU_R0402"))
    )
    (comp (ref "R2003")
      (value "0R")
      (footprint "eagle-import:R0402")
      (libsource (lib "eagle-import") (part "R-EU_R0402"))
    )
    (comp (ref "R2004")
      (value "0R")
      (footprint "eagle-import:R0402")
      (libsource (lib "eagle-import") (part "R-EU_R0402"))
    )
    (comp (ref "R2005")
      (value "22kR")
      (footprint "eagle-import:R0402")
      (libsource (lib "eagle-import") (part "R-EU_R0402"))
    )
    (comp (ref "R2006")
      (value "22kR")
      (footprint "eagle-import:R0402")
      (libsource (lib "eagle-import") (part "R-EU_R0402"))
    )
    (comp (ref "R2011")
      (value "47R")
      (footprint "eagle-import:R0402")
      (libsource (lib "eagle-import") (part "R-EU_R0402"))
    )
    (comp (ref "R2012")
      (value "47R")
      (footprint "eagle-import:R0402")
      (libsource (lib "eagle-import") (part "R-EU_R0402"))
    )
    (comp (ref "R2021")
      (value "47R")
      (footprint "eagle-import:R0402")
      (libsource (lib "eagle-import") (part "R-EU_R0402"))
    )
    (comp (ref "R2022")
      (value "47R")
      (footprint "eagle-import:R0402")
      (libsource (lib "eagle-import") (part "R-EU_R0402"))
    )
    (comp (ref "R2061")
      (value "47R")
      (footprint "eagle-import:R0402")
      (libsource (lib "eagle-import") (part "R-EU_R0402"))
    )
    (comp (ref "R2062")
      (value "47R")
      (footprint "eagle-import:R0402")
      (libsource (lib "eagle-import") (part "R-EU_R0402"))
    )
    (comp (ref "R2071")
      (value "47R")
      (footprint "eagle-import:R0402")
      (libsource (lib "eagle-import") (part "R-EU_R0402"))
    )
    (comp (ref "R2072")
      (value "47R")
      (footprint "eagle-import:R0402")
      (libsource (lib "eagle-import") (part "R-EU_R0402"))
    )
    (comp (ref "R2090")
      (value "47R")
      (footprint "eagle-import:R0402")
      (libsource (lib "eagle-import") (part "R-EU_R0402"))
    )
    (comp (ref "R2091")
      (value "47R")
      (footprint "eagle-import:R0402")
      (libsource (lib "eagle-import") (part "R-EU_R0402"))
    )
    (comp (ref "U2011")
      (value "TS5A23166")
      (footprint "eagle-import:R-PDSO-G8")
      (libsource (lib "eagle-import") (part "TS5A23166"))
    )
    (comp (ref "U2012")
      (value "TS5A23166")
      (footprint "eagle-import:R-PDSO-G8")
      (libsource (lib "eagle-import") (part "TS5A23166"))
    )
    (comp (ref "U2021")
      (value "TS5A23166")
      (footprint "eagle-import:R-PDSO-G8")
      (libsource (lib "eagle-import") (part "TS5A23166"))
    )
    (comp (ref "U2022")
      (value "TS5A23166")
      (footprint "eagle-import:R-PDSO-G8")
      (libsource (lib "eagle-import") (part "TS5A23166"))
    )
    (comp (ref "C1401")
      (value "4.7uF")
      (footprint "eagle-import:C0603")
      (libsource (lib "eagle-import") (part "C-EUC0603"))
    )
    (comp (ref "C1421")
      (value "10uF")
      (footprint "eagle-import:C0603")
      (libsource (lib "eagle-import") (part "C-EUC0603"))
    )
    (comp (ref "L1411")
      (value "2.2uH")
      (footprint "eagle-import:L2016")
      (libsource (lib "eagle-import") (part "L-EUL2016"))
    )
    (comp (ref "U1411")
      (value "TPS62743YFPR")
      (footprint "eagle-import:WCSP-8")
      (libsource (lib "eagle-import") (part "TPS62743"))
    )
    (comp (ref "C0901")
      (value "100nF")
      (footprint "eagle-import:C0402")
      (libsource (lib "eagle-import") (part "C-EUC0402"))
    )
    (comp (ref "C0902")
      (value "100nF")
      (footprint "eagle-import:C0402")
      (libsource (lib "eagle-import") (part "C-EUC0402"))
    )
    (comp (ref "C0903")
      (value "100nF")
      (footprint "eagle-import:C0402")
      (libsource (lib "eagle-import") (part "C-EUC0402"))
    )
    (comp (ref "C0921")
      (value "22pF")
      (footprint "eagle-import:C0402")
      (libsource (lib "eagle-import") (part "C-EUC0402"))
    )
    (comp (ref "C0922")
      (value "22pF")
      (footprint "eagle-import:C0402")
      (libsource (lib "eagle-import") (part "C-EUC0402"))
    )
    (comp (ref "D0901")
      (value "CMAD6001")
      (footprint "eagle-import:SOD923")
      (libsource (lib "eagle-import") (part "D_SOD923"))
    )
    (comp (ref "Q0921")
      (value "ABS07-32.768KHZ")
      (footprint "eagle-import:ABS07")
      (fields (field (name "MANUFACTURER") "ABS07-32.768KHZ-1-T"))
      (libsource (lib "eagle-import") (part "ABS07-32.768KHZ"))
    )
    (comp (ref "R0901")
      (value "3R")
      (footprint "eagle-import:R0402")
      (libsource (lib "eagle-import") (part "R-EU_R0402"))
    )
    (comp (ref "R0902")
      (value "3R")
      (footprint "eagle-import:R0402")
      (libsource (lib "eagle-import") (part "R-EU_R0402"))
    )
    (comp (ref "R0903")
      (value "47R")
      (footprint "eagle-import:R0402")
      (libsource (lib "eagle-import") (part "R-EU_R0402"))
    )
    (comp (ref "R0904")
      (value "3R")
      (footprint "eagle-import:R0402")
      (libsource (lib "eagle-import") (part "R-EU_R0402"))
    )
    (comp (ref "R0931")
      (value "3.9kR")
      (footprint "eagle-import:R0402")
      (libsource (lib "eagle-import") (part "R-EU_R0402"))
    )
    (comp (ref "R0932")
      (value "3.9kR")
      (footprint "eagle-import:R0402")
      (libsource (lib "eagle-import") (part "R-EU_R0402"))
    )
    (comp (ref "U0911")
      (value "BNO085")
      (footprint "eagle-import:BNO085_LGA28")
      (libsource (lib "eagle-import") (part "BNO085"))
    )
    (comp (ref "C0311")
      (value "22pF")
      (footprint "eagle-import:C0402")
      (libsource (lib "eagle-import") (part "C-EUC0402"))
    )
    (comp (ref "C0331")
      (value "JR200")
      (footprint "eagle-import:3MM2_X_2MM5")
      (libsource (lib "eagle-import") (part "C-TRIMM3MM2_2MM5"))
    )
    (comp (ref "C0332")
      (value "0pF")
      (footprint "eagle-import:C0402")
      (libsource (lib "eagle-import") (part "C-EUC0402"))
    )
    (comp (ref "Q0321")
      (value "ABS07-32.768KHZ-7-1-T 7pF")
      (footprint "eagle-import:ABS07")
      (fields (field (name "MANUFACTURER") "ABS07-32.768KHZ-1-T"))
      (libsource (lib "eagle-import") (part "ABS07-32.768KHZ"))
    )
    (comp (ref "X2211")
      (value "PHOENIX_1990067_1X8X2MM50_PTSA-0-5")
      (footprint "eagle-import:PHOENIX_1990067_1X8X2MM50_PTSA-0-5")
      (libsource (lib "eagle-import") (part "PHOENIX_1990067_1X8X2MM50_PTSA-0-5"))
    )
    (comp (ref "X2212")
      (value "PHOENIX_1990067_1X8X2MM50_PTSA-0-5")
      (footprint "eagle-import:PHOENIX_1990067_1X8X2MM50_PTSA-0-5")
      (libsource (lib "eagle-import") (part "PHOENIX_1990067_1X8X2MM50_PTSA-0-5"))
    )
    (comp (ref "X2251")
      (value "HEADER-2X5_1MM27")
      (footprint "eagle-import:2X05_1MM27")
      (libsource (lib "eagle-import") (part "HEADER-2X5_1MM27"))
    )
    (comp (ref "X2252")
      (value "HEADER-2X5_1MM27")
      (footprint "eagle-import:2X05_1MM27")
      (libsource (lib "eagle-import") (part "HEADER-2X5_1MM27"))
    )
    (comp (ref "X2253")
      (value "HEADER-2X5_1MM27")
      (footprint "eagle-import:2X05_1MM27")
      (libsource (lib "eagle-import") (part "HEADER-2X5_1MM27"))
    )
    (comp (ref "C1901")
      (value "100nF")
      (footprint "eagle-import:C0402")
      (libsource (lib "eagle-import") (part "C-EUC0402"))
    )
    (comp (ref "C1902")
      (value "100nF")
      (footprint "eagle-import:C0402")
      (libsource (lib "eagle-import") (part "C-EUC0402"))
    )
    (comp (ref "TP_BAT_VOLTAGE1")
      (value "PTR1TP06R")
      (footprint "eagle-import:TP06R")
      (libsource (lib "eagle-import") (part "PTR1TP06R"))
    )
    (comp (ref "C1801")
      (value "100nF")
      (footprint "eagle-import:C0402")
      (libsource (lib "eagle-import") (part "C-EUC0402"))
    )
    (comp (ref "C1802")
      (value "100nF")
      (footprint "eagle-import:C0402")
      (libsource (lib "eagle-import") (part "C-EUC0402"))
    )
    (comp (ref "TP_+3V3_BRIDGES")
      (value "PTR1TP06R")
      (footprint "eagle-import:TP06R")
      (libsource (lib "eagle-import") (part "PTR1TP06R"))
    )
    (comp (ref "U1801")
      (value "TS5A23166")
      (footprint "eagle-import:R-PDSO-G8")
      (libsource (lib "eagle-import") (part "TS5A23166"))
    )
    (comp (ref "C1701")
      (value "100nF")
      (footprint "eagle-import:C0402")
      (libsource (lib "eagle-import") (part "C-EUC0402"))
    )
    (comp (ref "TP_+3V3_USART1")
      (value "PTR1TP06R")
      (footprint "eagle-import:TP06R")
      (libsource (lib "eagle-import") (part "PTR1TP06R"))
    )
    (comp (ref "U1701")
      (value "TS5A23166")
      (footprint "eagle-import:R-PDSO-G8")
      (libsource (lib "eagle-import") (part "TS5A23166"))
    )
    (comp (ref "BUZZER+")
      (value "CUI Inc. CEB-44D06")
      (footprint "eagle-import:SMD2,54-5,08")
      (libsource (lib "eagle-import") (part "SMD5"))
    )
    (comp (ref "BUZZER-")
      (value "CUI Inc. CEB-44D06")
      (footprint "eagle-import:SMD2,54-5,08")
      (libsource (lib "eagle-import") (part "SMD5"))
    )
    (comp (ref "C2111")
      (value "10pF")
      (footprint "eagle-import:C0402")
      (libsource (lib "eagle-import") (part "C-EUC0402"))
    )
    (comp (ref "C2121")
      (value "10nF")
      (footprint "eagle-import:C0402")
      (libsource (lib "eagle-import") (part "C-EUC0402"))
    )
    (comp (ref "C2132")
      (value "10pF")
      (footprint "eagle-import:C0402")
      (libsource (lib "eagle-import") (part "C-EUC0402"))
    )
    (comp (ref "L2111")
      (value "10uH")
      (footprint "eagle-import:L0603")
      (libsource (lib "eagle-import") (part "L-EUL0603"))
    )
    (comp (ref "R2121")
      (value "1kR")
      (footprint "eagle-import:R0402")
      (libsource (lib "eagle-import") (part "R-EU_R0402"))
    )
    (comp (ref "S2131")
      (value "REED-SWITCH-MK6-10")
      (footprint "eagle-import:MK6-10")
      (libsource (lib "eagle-import") (part "REED-SWITCH-MK6-10"))
    )
    (comp (ref "VIN+")
      (value "6V")
      (footprint "eagle-import:SMD2,54-5,08")
      (libsource (lib "eagle-import") (part "SMD5"))
    )
    (comp (ref "VIN-")
      (value "6V")
      (footprint "eagle-import:SMD2,54-5,08")
      (libsource (lib "eagle-import") (part "SMD5"))
    )
    (comp (ref "R0511")
      (value "1kR")
      (footprint "eagle-import:R0402")
      (libsource (lib "eagle-import") (part "R-EU_R0402"))
    )
    (comp (ref "R0512")
      (value "1kR")
      (footprint "eagle-import:R0402")
      (libsource (lib "eagle-import") (part "R-EU_R0402"))
    )
    (comp (ref "R0551")
      (value "3R")
      (footprint "eagle-import:R0402")
      (libsource (lib "eagle-import") (part "R-EU_R0402"))
    )
    (comp (ref "R0552")
      (value "3R")
      (footprint "eagle-import:R0402")
      (libsource (lib "eagle-import") (part "R-EU_R0402"))
    )
    (comp (ref "C0701")
      (value "100nF")
      (footprint "eagle-import:C0402")
      (libsource (lib "eagle-import") (part "C-EUC0402"))
    )
    (comp (ref "C0702")
      (value "100nF")
      (footprint "eagle-import:C0402")
      (libsource (lib "eagle-import") (part "C-EUC0402"))
    )
    (comp (ref "C0711")
      (value "100nF")
      (footprint "eagle-import:C0402")
      (libsource (lib "eagle-import") (part "C-EUC0402"))
    )
    (comp (ref "C0721")
      (value "100nF")
      (footprint "eagle-import:C0402")
      (libsource (lib "eagle-import") (part "C-EUC0402"))
    )
    (comp (ref "C0722")
      (value "100nF")
      (footprint "eagle-import:C0402")
      (libsource (lib "eagle-import") (part "C-EUC0402"))
    )
    (comp (ref "C0723")
      (value "100nF")
      (footprint "eagle-import:C0402")
      (libsource (lib "eagle-import") (part "C-EUC0402"))
    )
    (comp (ref "C0724")
      (value "100nF")
      (footprint "eagle-import:C0402")
      (libsource (lib "eagle-import") (part "C-EUC0402"))
    )
    (comp (ref "C0752")
      (value "100nF")
      (footprint "eagle-import:C0402")
      (libsource (lib "eagle-import") (part "C-EUC0402"))
    )
    (comp (ref "R0731")
      (value "47R")
      (footprint "eagle-import:R0402")
      (libsource (lib "eagle-import") (part "R-EU_R0402"))
    )
    (comp (ref "U0711")
      (value "NAU7802SGI")
      (footprint "eagle-import:LSOP16")
      (libsource (lib "eagle-import") (part "NAU7802_24BIT_I2C"))
    )
  )
  (nets
    (net (code "9") (name "+1V2_SMPS_PWR") (class "Default")
      (node (ref "C1421") (pin "1") (pinfunction "1_1") (pintype "passive"))
      (node (ref "C1501") (pin "1") (pinfunction "1_1") (pintype "passive"))
      (node (ref "L1411") (pin "1") (pinfunction "1_1") (pintype "passive"))
      (node (ref "U1411") (pin "2C") (pinfunction "VOS_2C") (pintype "passive"))
      (node (ref "U1511") (pin "5") (pinfunction "5_5") (pintype "passive"))
    )
    (net (code "10") (name "+3V3") (class "Default")
      (node (ref "C1321") (pin "1") (pinfunction "1_1") (pintype "passive"))
      (node (ref "C1401") (pin "1") (pinfunction "1_1") (pintype "passive"))
      (node (ref "C1502") (pin "1") (pinfunction "1_1") (pintype "passive"))
      (node (ref "C1601") (pin "1") (pinfunction "1_1") (pintype "passive"))
      (node (ref "C1701") (pin "1") (pinfunction "1_1") (pintype "passive"))
      (node (ref "C1801") (pin "1") (pinfunction "1_1") (pintype "passive"))
      (node (ref "C1902") (pin "1") (pinfunction "1_1") (pintype "passive"))
      (node (ref "L1311") (pin "1") (pinfunction "1_1") (pintype "passive"))
      (node (ref "R0201") (pin "2") (pinfunction "2_2") (pintype "passive"))
      (node (ref "R0401") (pin "1") (pinfunction "1_1") (pintype "passive"))
      (node (ref "R0421") (pin "1") (pinfunction "1_1") (pintype "passive"))
      (node (ref "S2131") (pin "2") (pinfunction "2_2") (pintype "passive"))
      (node (ref "U1311") (pin "5") (pinfunction "VOUT_5") (pintype "passive"))
      (node (ref "U1411") (pin "2A") (pinfunction "VIN_2A") (pintype "power_in"))
      (node (ref "U1511") (pin "1") (pinfunction "1_1") (pintype "passive"))
      (node (ref "U1511") (pin "8") (pinfunction "8_8") (pintype "power_in"))
      (node (ref "U1601") (pin "1") (pinfunction "1_1") (pintype "passive"))
      (node (ref "U1601") (pin "5") (pinfunction "5_5") (pintype "passive"))
      (node (ref "U1601") (pin "8") (pinfunction "8_8") (pintype "power_in"))
      (node (ref "U1701") (pin "1") (pinfunction "1_1") (pintype "passive"))
      (node (ref "U1701") (pin "5") (pinfunction "5_5") (pintype "passive"))
      (node (ref "U1701") (pin "8") (pinfunction "8_8") (pintype "power_in"))
      (node (ref "U1801") (pin "1") (pinfunction "1_1") (pintype "passive"))
      (node (ref "U1801") (pin "5") (pinfunction "5_5") (pintype "passive"))
      (node (ref "U1801") (pin "8") (pinfunction "8_8") (pintype "power_in"))
      (node (ref "X0201") (pin "1") (pinfunction "1_1") (pintype "passive"))
      (node (ref "X0222") (pin "1") (pinfunction "1_1") (pintype "passive"))
      (node (ref "X2251") (pin "3") (pinfunction "3_3") (pintype "passive"))
      (node (ref "X2251") (pin "9") (pinfunction "9_9") (pintype "passive"))
    )
    (net (code "11") (name "+3V3_BRIDGE_PWR") (class "Default")
      (node (ref "C0752") (pin "1") (pinfunction "1_1") (pintype "passive"))
      (node (ref "C1802") (pin "1") (pinfunction "1_1") (pintype "passive"))
      (node (ref "C1901") (pin "1") (pinfunction "1_1") (pintype "passive"))
      (node (ref "C2001") (pin "1") (pinfunction "1_1") (pintype "passive"))
      (node (ref "R2005") (pin "2") (pinfunction "2_2") (pintype "passive"))
      (node (ref "R2006") (pin "2") (pinfunction "2_2") (pintype "passive"))
      (node (ref "TP_+3V3_BRIDGES") (pin "TP") (pinfunction "TP_TP") (pintype "input"))
      (node (ref "U0711") (pin "1") (pinfunction "REFP_1") (pintype "passive"))
      (node (ref "U1801") (pin "2") (pinfunction "2_2") (pintype "passive"))
      (node (ref "U1801") (pin "6") (pinfunction "6_6") (pintype "passive"))
      (node (ref "U2011") (pin "8") (pinfunction "8_8") (pintype "power_in"))
      (node (ref "U2012") (pin "8") (pinfunction "8_8") (pintype "power_in"))
      (node (ref "U2021") (pin "8") (pinfunction "8_8") (pintype "power_in"))
      (node (ref "U2022") (pin "8") (pinfunction "8_8") (pintype "power_in"))
      (node (ref "X2211") (pin "1") (pinfunction "1_1") (pintype "passive"))
      (node (ref "X2211") (pin "5") (pinfunction "5_5") (pintype "passive"))
      (node (ref "X2212") (pin "1") (pinfunction "1_1") (pintype "passive"))
      (node (ref "X2212") (pin "5") (pinfunction "5_5") (pintype "passive"))
      (node (ref "X2251") (pin "4") (pinfunction "4_4") (pintype "passive"))
    )
    (net (code "12") (name "+3V3_I2C1_PWR") (class "Default")
      (node (ref "C0601") (pin "2") (pinfunction "2_2") (pintype "passive"))
      (node (ref "C0701") (pin "1") (pinfunction "1_1") (pintype "passive"))
      (node (ref "C0702") (pin "1") (pinfunction "1_1") (pintype "passive"))
      (node (ref "C0801") (pin "1") (pinfunction "1_1") (pintype "passive"))
      (node (ref "C1113") (pin "1") (pinfunction "1_1") (pintype "passive"))
      (node (ref "C1521") (pin "1") (pinfunction "1_1") (pintype "passive"))
      (node (ref "R0511") (pin "2") (pinfunction "2_2") (pintype "passive"))
      (node (ref "R0512") (pin "2") (pinfunction "2_2") (pintype "passive"))
      (node (ref "R0802") (pin "2") (pinfunction "2_2") (pintype "passive"))
      (node (ref "R1112") (pin "2") (pinfunction "2_2") (pintype "passive"))
      (node (ref "TP_+3V3_I2C1") (pin "TP") (pinfunction "TP_TP") (pintype "input"))
      (node (ref "U0611") (pin "8") (pinfunction "VCC_8") (pintype "power_in"))
      (node (ref "U0711") (pin "15") (pinfunction "DVDD_15") (pintype "power_in"))
      (node (ref "U0711") (pin "16") (pinfunction "AVDD_16") (pintype "power_in"))
      (node (ref "U0811") (pin "2") (pinfunction "VDD_I2C_2") (pintype "power_in"))
      (node (ref "U0811") (pin "24") (pinfunction "VDD_P_24") (pintype "power_in"))
      (node (ref "U1111") (pin "2") (pinfunction "VDD_I2C_2") (pintype "power_in"))
      (node (ref "U1111") (pin "21") (pinfunction "ADDR_21") (pintype "input"))
      (node (ref "U1111") (pin "24") (pinfunction "VDD_P_24") (pintype "power_in"))
      (node (ref "U1511") (pin "2") (pinfunction "2_2") (pintype "passive"))
      (node (ref "X2251") (pin "6") (pinfunction "6_6") (pintype "passive"))
    )
    (net (code "13") (name "+3V3_SPI3_PWR") (class "Default")
      (node (ref "C0901") (pin "1") (pinfunction "1_1") (pintype "passive"))
      (node (ref "C0902") (pin "1") (pinfunction "1_1") (pintype "passive"))
      (node (ref "C1001") (pin "1") (pinfunction "1_1") (pintype "passive"))
      (node (ref "C1002") (pin "1") (pinfunction "1_1") (pintype "passive"))
      (node (ref "R0931") (pin "2") (pinfunction "2_2") (pintype "passive"))
      (node (ref "R0932") (pin "2") (pinfunction "2_2") (pintype "passive"))
      (node (ref "R1071") (pin "2") (pinfunction "2_2") (pintype "passive"))
      (node (ref "TP_+3V3_SPI3") (pin "TP") (pinfunction "TP_TP") (pintype "input"))
      (node (ref "U0911") (pin "28") (pinfunction "VDDIO_28") (pintype "power_in"))
      (node (ref "U0911") (pin "3") (pinfunction "VDD_3") (pintype "power_in"))
      (node (ref "U0911") (pin "5") (pinfunction "PS1_5") (pintype "input"))
      (node (ref "U1001") (pin "10") (pinfunction "VBAT_10") (pintype "power_in"))
      (node (ref "U1001") (pin "11") (pinfunction "VBAT_IO_11") (pintype "power_in"))
      (node (ref "U1601") (pin "2") (pinfunction "2_2") (pintype "passive"))
      (node (ref "U1601") (pin "6") (pinfunction "6_6") (pintype "passive"))
      (node (ref "X2251") (pin "5") (pinfunction "5_5") (pintype "passive"))
    )
    (net (code "14") (name "+3V3_USART1_PWR") (class "Default")
      (node (ref "C1201") (pin "1") (pinfunction "1_1") (pintype "passive"))
      (node (ref "C1202") (pin "1") (pinfunction "1_1") (pintype "passive"))
      (node (ref "TP_+3V3_USART1") (pin "TP") (pinfunction "TP_TP") (pintype "input"))
      (node (ref "U1211") (pin "8") (pinfunction "VCC_8") (pintype "power_in"))
      (node (ref "U1701") (pin "2") (pinfunction "2_2") (pintype "passive"))
      (node (ref "U1701") (pin "6") (pinfunction "6_6") (pintype "passive"))
    )
    (net (code "15") (name "+BAT_VOLTAGE_PWR") (class "Default")
      (node (ref "R0462") (pin "2") (pinfunction "2_2") (pintype "passive"))
      (node (ref "TP_BAT_VOLTAGE1") (pin "TP") (pinfunction "TP_TP") (pintype "input"))
      (node (ref "X2251") (pin "2") (pinfunction "2_2") (pintype "passive"))
    )
    (net (code "21") (name "ADC_VIN1N") (class "Default")
      (node (ref "C0722") (pin "1") (pinfunction "1_1") (pintype "passive"))
      (node (ref "R2002") (pin "1") (pinfunction "1_1") (pintype "passive"))
      (node (ref "U0711") (pin "2") (pinfunction "VIN1N_2") (pintype "passive"))
      (node (ref "U2011") (pin "6") (pinfunction "6_6") (pintype "passive"))
      (node (ref "U2012") (pin "6") (pinfunction "6_6") (pintype "passive"))
    )
    (net (code "22") (name "ADC_VIN1P") (class "Default")
      (node (ref "C0721") (pin "1") (pinfunction "1_1") (pintype "passive"))
      (node (ref "R2001") (pin "1") (pinfunction "1_1") (pintype "passive"))
      (node (ref "R2005") (pin "1") (pinfunction "1_1") (pintype "passive"))
      (node (ref "U0711") (pin "3") (pinfunction "VIN1P_3") (pintype "passive"))
      (node (ref "U2011") (pin "2") (pinfunction "2_2") (pintype "passive"))
      (node (ref "U2012") (pin "2") (pinfunction "2_2") (pintype "passive"))
    )
    (net (code "23") (name "ADC_VIN2N") (class "Default")
      (node (ref "C0724") (pin "1") (pinfunction "1_1") (pintype "passive"))
      (node (ref "R2004") (pin "2") (pinfunction "2_2") (pintype "passive"))
      (node (ref "U0711") (pin "4") (pinfunction "VIN2N_4") (pintype "passive"))
      (node (ref "U2021") (pin "6") (pinfunction "6_6") (pintype "passive"))
      (node (ref "U2022") (pin "6") (pinfunction "6_6") (pintype "passive"))
    )
    (net (code "24") (name "ADC_VIN2P") (class "Default")
      (node (ref "C0723") (pin "1") (pinfunction "1_1") (pintype "passive"))
      (node (ref "R2003") (pin "2") (pinfunction "2_2") (pintype "passive"))
      (node (ref "R2006") (pin "1") (pinfunction "1_1") (pintype "passive"))
      (node (ref "U0711") (pin "5") (pinfunction "VIN2P_5") (pintype "passive"))
      (node (ref "U2021") (pin "2") (pinfunction "2_2") (pintype "passive"))
      (node (ref "U2022") (pin "2") (pinfunction "2_2") (pintype "passive"))
    )
    (net (code "25") (name "ANT_LORA") (class "Default")
      (node (ref "C1083") (pin "2") (pinfunction "2_2") (pintype "passive"))
      (node (ref "L1082") (pin "1") (pinfunction "1_1") (pintype "passive"))
      (node (ref "X1081") (pin "ANT1") (pinfunction "SIGNAL_ANT1") (pintype "bidirectional"))
      (node (ref "X1081") (pin "ANT2") (pinfunction "SIGNAL_ANT2") (pintype "bidirectional"))
      (node (ref "X1081") (pin "ANT3") (pinfunction "SIGNAL_ANT3") (pintype "bidirectional"))
    )
    (net (code "26") (name "BNO_CAP") (class "Default")
      (node (ref "C0903") (pin "1") (pinfunction "1_1") (pintype "passive"))
      (node (ref "U0911") (pin "9") (pinfunction "CAP_9") (pintype "passive"))
    )
    (net (code "27") (name "BNO_ENV_SCL") (class "Default")
      (node (ref "R0932") (pin "1") (pinfunction "1_1") (pintype "passive"))
      (node (ref "U0911") (pin "15") (pinfunction "ENV_SCL_15") (pintype "bidirectional"))
    )
    (net (code "28") (name "BNO_ENV_SDA") (class "Default")
      (node (ref "R0931") (pin "1") (pinfunction "1_1") (pintype "passive"))
      (node (ref "U0911") (pin "16") (pinfunction "ENV_SDA_16") (pintype "bidirectional"))
    )
    (net (code "29") (name "BNO_H_CSN") (class "Default")
      (node (ref "R0904") (pin "2") (pinfunction "2_2") (pintype "passive"))
      (node (ref "U0911") (pin "18") (pinfunction "H_CSN_18") (pintype "input"))
    )
    (net (code "30") (name "BNO_INTN") (class "Default")
      (node (ref "R0902") (pin "2") (pinfunction "2_2") (pintype "passive"))
      (node (ref "U0911") (pin "14") (pinfunction "H_INTN_14") (pintype "output"))
    )
    (net (code "31") (name "BNO_MISO") (class "Default")
      (node (ref "R0901") (pin "2") (pinfunction "2_2") (pintype "passive"))
      (node (ref "U0911") (pin "20") (pinfunction "H_SDA/MISO/TX_20") (pintype "bidirectional"))
    )
    (net (code "32") (name "BNO_PS0_WAKE") (class "Default")
      (node (ref "R0903") (pin "2") (pinfunction "2_2") (pintype "passive"))
      (node (ref "U0911") (pin "6") (pinfunction "PS0/WAKE_6") (pintype "input"))
    )
    (net (code "33") (name "BRIDGE_N1") (class "Default")
      (node (ref "R2061") (pin "2") (pinfunction "2_2") (pintype "passive"))
      (node (ref "X2211") (pin "3") (pinfunction "3_3") (pintype "passive"))
    )
    (net (code "34") (name "BRIDGE_N2") (class "Default")
      (node (ref "R2071") (pin "1") (pinfunction "1_1") (pintype "passive"))
      (node (ref "X2211") (pin "7") (pinfunction "7_7") (pintype "passive"))
    )
    (net (code "35") (name "BRIDGE_N3") (class "Default")
      (node (ref "R2062") (pin "2") (pinfunction "2_2") (pintype "passive"))
      (node (ref "X2212") (pin "3") (pinfunction "3_3") (pintype "passive"))
    )
    (net (code "36") (name "BRIDGE_N4") (class "Default")
      (node (ref "R2072") (pin "1") (pinfunction "1_1") (pintype "passive"))
      (node (ref "X2212") (pin "7") (pinfunction "7_7") (pintype "passive"))
    )
    (net (code "37") (name "BRIDGE_P1") (class "Default")
      (node (ref "R2011") (pin "2") (pinfunction "2_2") (pintype "passive"))
      (node (ref "X2211") (pin "2") (pinfunction "2_2") (pintype "passive"))
    )
    (net (code "38") (name "BRIDGE_P2") (class "Default")
      (node (ref "R2021") (pin "1") (pinfunction "1_1") (pintype "passive"))
      (node (ref "X2211") (pin "6") (pinfunction "6_6") (pintype "passive"))
    )
    (net (code "39") (name "BRIDGE_P3") (class "Default")
      (node (ref "R2012") (pin "2") (pinfunction "2_2") (pintype "passive"))
      (node (ref "X2212") (pin "2") (pinfunction "2_2") (pintype "passive"))
    )
    (net (code "40") (name "BRIDGE_P4") (class "Default")
      (node (ref "R2022") (pin "1") (pinfunction "1_1") (pintype "passive"))
      (node (ref "X2212") (pin "6") (pinfunction "6_6") (pintype "passive"))
    )
    (net (code "41") (name "BUZZER") (class "Default")
      (node (ref "BUZZER+") (pin "1") (pinfunction "P_1") (pintype "passive"))
      (node (ref "R2121") (pin "1") (pinfunction "1_1") (pintype "passive"))
    )
    (net (code "42") (name "ESP_CTS") (class "Default")
      (node (ref "R1257") (pin "1") (pinfunction "1_1") (pintype "passive"))
      (node (ref "U1211") (pin "7") (pinfunction "GPIO13_UART0_CTS_7") (pintype "bidirectional"))
    )
    (net (code "43") (name "ESP_RTS") (class "Default")
      (node (ref "R1266") (pin "1") (pinfunction "1_1") (pintype "passive"))
      (node (ref "U1211") (pin "16") (pinfunction "GPIO15_UART0_RTS_16") (pintype "bidirectional"))
    )
    (net (code "44") (name "ESP_RX") (class "Default")
      (node (ref "R1271") (pin "1") (pinfunction "1_1") (pintype "passive"))
      (node (ref "U1211") (pin "21") (pinfunction "RXD_21") (pintype "input"))
    )
    (net (code "45") (name "ESP_TX") (class "Default")
      (node (ref "R1272") (pin "1") (pinfunction "1_1") (pintype "passive"))
      (node (ref "U1211") (pin "22") (pinfunction "TXD_22") (pintype "output"))
    )
    (net (code "46") (name "EXTI9_I2C1_ADC_DRDY") (class "Default")
      (node (ref "R0731") (pin "2") (pinfunction "2_2") (pintype "passive"))
      (node (ref "U0711") (pin "12") (pinfunction "DRDY_12") (pintype "output"))
    )
    (net (code "47") (name "GND") (class "Default")
      (node (ref "BUZZER-") (pin "1") (pinfunction "P_1") (pintype "passive"))
      (node (ref "C0213") (pin "2") (pinfunction "2_2") (pintype "passive"))
      (node (ref "C0311") (pin "2") (pinfunction "2_2") (pintype "passive"))
      (node (ref "C0331") (pin "+") (pinfunction "A_+") (pintype "passive"))
      (node (ref "C0332") (pin "2") (pinfunction "2_2") (pintype "passive"))
      (node (ref "C0401") (pin "2") (pinfunction "2_2") (pintype "passive"))
      (node (ref "C0402") (pin "2") (pinfunction "2_2") (pintype "passive"))
      (node (ref "C0403") (pin "2") (pinfunction "2_2") (pintype "passive"))
      (node (ref "C0410") (pin "1") (pinfunction "1_1") (pintype "passive"))
      (node (ref "C0412") (pin "2") (pinfunction "2_2") (pintype "passive"))
      (node (ref "C0413") (pin "2") (pinfunction "2_2") (pintype "passive"))
      (node (ref "C0451") (pin "2") (pinfunction "2_2") (pintype "passive"))
      (node (ref "C0461") (pin "2") (pinfunction "2_2") (pintype "passive"))
      (node (ref "C0601") (pin "1") (pinfunction "1_1") (pintype "passive"))
      (node (ref "C0701") (pin "2") (pinfunction "2_2") (pintype "passive"))
      (node (ref "C0702") (pin "2") (pinfunction "2_2") (pintype "passive"))
      (node (ref "C0711") (pin "2") (pinfunction "2_2") (pintype "passive"))
      (node (ref "C0721") (pin "2") (pinfunction "2_2") (pintype "passive"))
      (node (ref "C0722") (pin "2") (pinfunction "2_2") (pintype "passive"))
      (node (ref "C0723") (pin "2") (pinfunction "2_2") (pintype "passive"))
      (node (ref "C0724") (pin "2") (pinfunction "2_2") (pintype "passive"))
      (node (ref "C0752") (pin "2") (pinfunction "2_2") (pintype "passive"))
      (node (ref "C0801") (pin "2") (pinfunction "2_2") (pintype "passive"))
      (node (ref "C0901") (pin "2") (pinfunction "2_2") (pintype "passive"))
      (node (ref "C0902") (pin "2") (pinfunction "2_2") (pintype "passive"))
      (node (ref "C0903") (pin "2") (pinfunction "2_2") (pintype "passive"))
      (node (ref "C0921") (pin "2") (pinfunction "2_2") (pintype "passive"))
      (node (ref "C0922") (pin "2") (pinfunction "2_2") (pintype "passive"))
      (node (ref "C1001") (pin "2") (pinfunction "2_2") (pintype "passive"))
      (node (ref "C1002") (pin "2") (pinfunction "2_2") (pintype "passive"))
      (node (ref "C1003") (pin "2") (pinfunction "2_2") (pintype "passive"))
      (node (ref "C1004") (pin "2") (pinfunction "2_2") (pintype "passive"))
      (node (ref "C1005") (pin "2") (pinfunction "2_2") (pintype "passive"))
      (node (ref "C1006") (pin "1") (pinfunction "1_1") (pintype "passive"))
      (node (ref "C1065") (pin "1") (pinfunction "1_1") (pintype "passive"))
      (node (ref "C1066") (pin "2") (pinfunction "2_2") (pintype "passive"))
      (node (ref "C1067") (pin "2") (pinfunction "2_2") (pintype "passive"))
      (node (ref "C1071") (pin "2") (pinfunction "2_2") (pintype "passive"))
      (node (ref "C1072") (pin "2") (pinfunction "2_2") (pintype "passive"))
      (node (ref "C1082") (pin "1") (pinfunction "1_1") (pintype "passive"))
      (node (ref "C1083") (pin "1") (pinfunction "1_1") (pintype "passive"))
      (node (ref "C1091") (pin "1") (pinfunction "1_1") (pintype "passive"))
      (node (ref "C1093") (pin "1") (pinfunction "1_1") (pintype "passive"))
      (node (ref "C1113") (pin "2") (pinfunction "2_2") (pintype "passive"))
      (node (ref "C1201") (pin "2") (pinfunction "2_2") (pintype "passive"))
      (node (ref "C1202") (pin "2") (pinfunction "2_2") (pintype "passive"))
      (node (ref "C1301") (pin "2") (pinfunction "2_2") (pintype "passive"))
      (node (ref "C1321") (pin "2") (pinfunction "2_2") (pintype "passive"))
      (node (ref "C1401") (pin "2") (pinfunction "2_2") (pintype "passive"))
      (node (ref "C1421") (pin "2") (pinfunction "2_2") (pintype "passive"))
      (node (ref "C1501") (pin "2") (pinfunction "2_2") (pintype "passive"))
      (node (ref "C1502") (pin "2") (pinfunction "2_2") (pintype "passive"))
      (node (ref "C1521") (pin "2") (pinfunction "2_2") (pintype "passive"))
      (node (ref "C1591") (pin "1") (pinfunction "1_1") (pintype "passive"))
      (node (ref "C1592") (pin "2") (pinfunction "2_2") (pintype "passive"))
      (node (ref "C1601") (pin "2") (pinfunction "2_2") (pintype "passive"))
      (node (ref "C1701") (pin "2") (pinfunction "2_2") (pintype "passive"))
      (node (ref "C1801") (pin "2") (pinfunction "2_2") (pintype "passive"))
      (node (ref "C1802") (pin "2") (pinfunction "2_2") (pintype "passive"))
      (node (ref "C1901") (pin "2") (pinfunction "2_2") (pintype "passive"))
      (node (ref "C1902") (pin "2") (pinfunction "2_2") (pintype "passive"))
      (node (ref "C2001") (pin "2") (pinfunction "2_2") (pintype "passive"))
      (node (ref "C2011") (pin "2") (pinfunction "2_2") (pintype "passive"))
      (node (ref "C2012") (pin "2") (pinfunction "2_2") (pintype "passive"))
      (node (ref "C2021") (pin "2") (pinfunction "2_2") (pintype "passive"))
      (node (ref "C2022") (pin "2") (pinfunction "2_2") (pintype "passive"))
      (node (ref "C2061") (pin "2") (pinfunction "2_2") (pintype "passive"))
      (node (ref "C2062") (pin "2") (pinfunction "2_2") (pintype "passive"))
      (node (ref "C2071") (pin "2") (pinfunction "2_2") (pintype "passive"))
      (node (ref "C2072") (pin "2") (pinfunction "2_2") (pintype "passive"))
      (node (ref "C2111") (pin "2") (pinfunction "2_2") (pintype "passive"))
      (node (ref "C2121") (pin "2") (pinfunction "2_2") (pintype "passive"))
      (node (ref "C2132") (pin "2") (pinfunction "2_2") (pintype "passive"))
      (node (ref "H2311") (pin "B2,8") (pinfunction "MOUNT_B2,8") (pintype "passive"))
      (node (ref "H2321") (pin "B2,8") (pinfunction "MOUNT_B2,8") (pintype "passive"))
      (node (ref "H2331") (pin "B2,8") (pinfunction "MOUNT_B2,8") (pintype "passive"))
      (node (ref "H2341") (pin "B2,8") (pinfunction "MOUNT_B2,8") (pintype "passive"))
      (node (ref "Q1011") (pin "2") (pinfunction "3_2") (pintype "passive"))
      (node (ref "Q1011") (pin "4") (pinfunction "3_4") (pintype "passive"))
      (node (ref "R0202") (pin "1") (pinfunction "1_1") (pintype "passive"))
      (node (ref "R0221") (pin "1") (pinfunction "1_1") (pintype "passive"))
      (node (ref "R0441") (pin "1") (pinfunction "1_1") (pintype "passive"))
      (node (ref "R0461") (pin "1") (pinfunction "1_1") (pintype "passive"))
      (node (ref "S0212") (pin "1") (pinfunction "P_1") (pintype "passive"))
      (node (ref "U0101") (pin "18") (pinfunction "VSS_18") (pintype "passive"))
      (node (ref "U0101") (pin "31") (pinfunction "VSS_31") (pintype "passive"))
      (node (ref "U0101") (pin "47") (pinfunction "VSS_47") (pintype "passive"))
      (node (ref "U0101") (pin "63") (pinfunction "VSS_63") (pintype "passive"))
      (node (ref "U0611") (pin "1") (pinfunction "A0_1") (pintype "input"))
      (node (ref "U0611") (pin "2") (pinfunction "A1_2") (pintype "input"))
      (node (ref "U0611") (pin "3") (pinfunction "A2_3") (pintype "input"))
      (node (ref "U0611") (pin "4") (pinfunction "VSS_4") (pintype "power_in"))
      (node (ref "U0611") (pin "7") (pinfunction "WP_7") (pintype "input"))
      (node (ref "U0711") (pin "7") (pinfunction "REFN_7") (pintype "passive"))
      (node (ref "U0711") (pin "8") (pinfunction "AVSS_8") (pintype "passive"))
      (node (ref "U0711") (pin "9") (pinfunction "DVSS_9") (pintype "passive"))
      (node (ref "U0811") (pin "12") (pinfunction "VSS_12") (pintype "passive"))
      (node (ref "U0811") (pin "21") (pinfunction "ADDR_21") (pintype "input"))
      (node (ref "U0911") (pin "10") (pinfunction "CLKSEL0_10") (pintype "input"))
      (node (ref "U0911") (pin "2") (pinfunction "VSS_2") (pintype "passive"))
      (node (ref "U0911") (pin "25") (pinfunction "VSSIO_25") (pintype "passive"))
      (node (ref "U1001") (pin "2") (pinfunction "VSS_2") (pintype "passive"))
      (node (ref "U1001") (pin "20") (pinfunction "VSS_20") (pintype "passive"))
      (node (ref "U1001") (pin "25") (pinfunction "VSS_25") (pintype "passive"))
      (node (ref "U1001") (pin "5") (pinfunction "VSS_5") (pintype "passive"))
      (node (ref "U1001") (pin "8") (pinfunction "VSS_8") (pintype "passive"))
      (node (ref "U1071") (pin "2") (pinfunction "GND_2") (pintype "power_in"))
      (node (ref "U1111") (pin "12") (pinfunction "VSS_12") (pintype "passive"))
      (node (ref "U1211") (pin "15") (pinfunction "VSS_15") (pintype "passive"))
      (node (ref "U1211") (pin "2") (pinfunction "ADC_2") (pintype "passive"))
      (node (ref "U1311") (pin "13") (pinfunction "VSS_13") (pintype "passive"))
      (node (ref "U1311") (pin "14") (pinfunction "VSS_14") (pintype "passive"))
      (node (ref "U1311") (pin "3") (pinfunction "VSS_3") (pintype "passive"))
      (node (ref "U1311") (pin "4") (pinfunction "EN_VIN_SW_4") (pintype "input"))
      (node (ref "U1311") (pin "G1") (pinfunction "VSS_G1") (pintype "passive"))
      (node (ref "U1311") (pin "G2") (pinfunction "VSS_G2") (pintype "passive"))
      (node (ref "U1311") (pin "G3") (pinfunction "VSS_G3") (pintype "passive"))
      (node (ref "U1411") (pin "1C") (pinfunction "VSEL1_1C") (pintype "input"))
      (node (ref "U1411") (pin "1D") (pinfunction "VSEL2_1D") (pintype "input"))
      (node (ref "U1411") (pin "2B") (pinfunction "VSS_2B") (pintype "passive"))
      (node (ref "U1411") (pin "2D") (pinfunction "VSEL3_2D") (pintype "input"))
      (node (ref "U1511") (pin "4") (pinfunction "4_4") (pintype "passive"))
      (node (ref "U1601") (pin "4") (pinfunction "4_4") (pintype "passive"))
      (node (ref "U1701") (pin "4") (pinfunction "4_4") (pintype "passive"))
      (node (ref "U1801") (pin "4") (pinfunction "4_4") (pintype "passive"))
      (node (ref "U2011") (pin "4") (pinfunction "4_4") (pintype "passive"))
      (node (ref "U2012") (pin "4") (pinfunction "4_4") (pintype "passive"))
      (node (ref "U2021") (pin "4") (pinfunction "4_4") (pintype "passive"))
      (node (ref "U2022") (pin "4") (pinfunction "4_4") (pintype "passive"))
      (node (ref "VIN-") (pin "1") (pinfunction "P_1") (pintype "passive"))
      (node (ref "X0201") (pin "3") (pinfunction "3_3") (pintype "passive"))
      (node (ref "X0201") (pin "5") (pinfunction "5_5") (pintype "passive"))
      (node (ref "X0201") (pin "9") (pinfunction "9_9") (pintype "passive"))
      (node (ref "X1081") (pin "GND1") (pinfunction "GND_GND1") (pintype "bidirectional"))
      (node (ref "X1081") (pin "GND2") (pinfunction "GND_GND2") (pintype "bidirectional"))
      (node (ref "X1081") (pin "GND3") (pinfunction "GND_GND3") (pintype "bidirectional"))
      (node (ref "X1081") (pin "GND4") (pinfunction "GND_GND4") (pintype "bidirectional"))
      (node (ref "X2211") (pin "4") (pinfunction "4_4") (pintype "passive"))
      (node (ref "X2211") (pin "8") (pinfunction "8_8") (pintype "passive"))
      (node (ref "X2212") (pin "4") (pinfunction "4_4") (pintype "passive"))
      (node (ref "X2212") (pin "8") (pinfunction "8_8") (pintype "passive"))
      (node (ref "X2251") (pin "10") (pinfunction "10_10") (pintype "passive"))
      (node (ref "X2252") (pin "10") (pinfunction "10_10") (pintype "passive"))
      (node (ref "X2253") (pin "10") (pinfunction "10_10") (pintype "passive"))
    )
    (net (code "48") (name "MCU_NRST") (class "Default")
      (node (ref "C0213") (pin "1") (pinfunction "1_1") (pintype "passive"))
      (node (ref "S0212") (pin "2") (pinfunction "S_2") (pintype "passive"))
      (node (ref "U0101") (pin "7") (pinfunction "NRST_7") (pintype "bidirectional"))
      (node (ref "X0201") (pin "10") (pinfunction "10_10") (pintype "passive"))
    )
    (net (code "49") (name "MCU_VBAT") (class "Default")
      (node (ref "C0451") (pin "1") (pinfunction "1_1") (pintype "passive"))
      (node (ref "TP_VBAT") (pin "TP") (pinfunction "TP_TP") (pintype "input"))
      (node (ref "U0101") (pin "1") (pinfunction "VBAT_1") (pintype "power_in"))
    )
    (net (code "50") (name "MCU_VDD") (class "Default")
      (node (ref "C0401") (pin "1") (pinfunction "1_1") (pintype "passive"))
      (node (ref "C0402") (pin "1") (pinfunction "1_1") (pintype "passive"))
      (node (ref "C0403") (pin "1") (pinfunction "1_1") (pintype "passive"))
      (node (ref "C0410") (pin "2") (pinfunction "2_2") (pintype "passive"))
      (node (ref "L0411") (pin "1") (pinfunction "1_1") (pintype "passive"))
      (node (ref "R0401") (pin "2") (pinfunction "2_2") (pintype "passive"))
      (node (ref "U0101") (pin "19") (pinfunction "VDD_19") (pintype "power_in"))
      (node (ref "U0101") (pin "32") (pinfunction "VDD_32") (pintype "power_in"))
      (node (ref "U0101") (pin "64") (pinfunction "VDD_64") (pintype "power_in"))
    )
    (net (code "51") (name "MCU_VDD12") (class "Default")
      (node (ref "C1591") (pin "2") (pinfunction "2_2") (pintype "passive"))
      (node (ref "C1592") (pin "1") (pinfunction "1_1") (pintype "passive"))
      (node (ref "TP_+1V2_MCU") (pin "TP") (pinfunction "TP_TP") (pintype "input"))
      (node (ref "U0101") (pin "30") (pinfunction "VDD12_30") (pintype "power_in"))
      (node (ref "U0101") (pin "62") (pinfunction "VDD12_62") (pintype "power_in"))
      (node (ref "U1511") (pin "6") (pinfunction "6_6") (pintype "passive"))
    )
    (net (code "52") (name "MCU_VDDA") (class "Default")
      (node (ref "C0412") (pin "1") (pinfunction "1_1") (pintype "passive"))
      (node (ref "C0413") (pin "1") (pinfunction "1_1") (pintype "passive"))
      (node (ref "L0411") (pin "2") (pinfunction "2_2") (pintype "passive"))
      (node (ref "U0101") (pin "13") (pinfunction "VDDA_VREF_P_13") (pintype "power_in"))
    )
    (net (code "53") (name "MCU_VREF_M") (class "Default")
      (node (ref "R0441") (pin "2") (pinfunction "2_2") (pintype "passive"))
      (node (ref "U0101") (pin "12") (pinfunction "VSSA_VREF_M_12") (pintype "passive"))
    )
    (net (code "54") (name "Net-(C1063-Pad2)") (class "Default")
      (node (ref "C1063") (pin "2") (pinfunction "2_2") (pintype "passive"))
      (node (ref "C1064") (pin "1") (pinfunction "1_1") (pintype "passive"))
      (node (ref "C1066") (pin "1") (pinfunction "1_1") (pintype "passive"))
      (node (ref "L1063") (pin "1") (pinfunction "1_1") (pintype "passive"))
    )
    (net (code "55") (name "Net-(C1064-Pad2)") (class "Default")
      (node (ref "C1064") (pin "2") (pinfunction "2_2") (pintype "passive"))
      (node (ref "L1064") (pin "2") (pinfunction "2_2") (pintype "passive"))
    )
    (net (code "56") (name "Net-(C1081-Pad2)") (class "Default")
      (node (ref "C1081") (pin "2") (pinfunction "2_2") (pintype "passive"))
      (node (ref "C1082") (pin "2") (pinfunction "2_2") (pintype "passive"))
      (node (ref "L1082") (pin "2") (pinfunction "2_2") (pintype "passive"))
    )
    (net (code "57") (name "Net-(C2011-Pad1)") (class "Default")
      (node (ref "C2011") (pin "1") (pinfunction "1_1") (pintype "passive"))
      (node (ref "L2011") (pin "1") (pinfunction "1_1") (pintype "passive"))
      (node (ref "R2001") (pin "2") (pinfunction "2_2") (pintype "passive"))
      (node (ref "U2011") (pin "1") (pinfunction "1_1") (pintype "passive"))
    )
    (net (code "58") (name "Net-(C2012-Pad1)") (class "Default")
      (node (ref "C2012") (pin "1") (pinfunction "1_1") (pintype "passive"))
      (node (ref "L2012") (pin "1") (pinfunction "1_1") (pintype "passive"))
      (node (ref "U2012") (pin "1") (pinfunction "1_1") (pintype "passive"))
    )
    (net (code "59") (name "Net-(C2021-Pad1)") (class "Default")
      (node (ref "C2021") (pin "1") (pinfunction "1_1") (pintype "passive"))
      (node (ref "L2021") (pin "2") (pinfunction "2_2") (pintype "passive"))
      (node (ref "R2003") (pin "1") (pinfunction "1_1") (pintype "passive"))
      (node (ref "U2021") (pin "1") (pinfunction "1_1") (pintype "passive"))
    )
    (net (code "60") (name "Net-(C2022-Pad1)") (class "Default")
      (node (ref "C2022") (pin "1") (pinfunction "1_1") (pintype "passive"))
      (node (ref "L2022") (pin "2") (pinfunction "2_2") (pintype "passive"))
      (node (ref "U2022") (pin "1") (pinfunction "1_1") (pintype "passive"))
    )
    (net (code "61") (name "Net-(C2061-Pad1)") (class "Default")
      (node (ref "C2061") (pin "1") (pinfunction "1_1") (pintype "passive"))
      (node (ref "L2061") (pin "1") (pinfunction "1_1") (pintype "passive"))
      (node (ref "R2002") (pin "2") (pinfunction "2_2") (pintype "passive"))
      (node (ref "U2011") (pin "5") (pinfunction "5_5") (pintype "passive"))
    )
    (net (code "62") (name "Net-(C2062-Pad1)") (class "Default")
      (node (ref "C2062") (pin "1") (pinfunction "1_1") (pintype "passive"))
      (node (ref "L2062") (pin "1") (pinfunction "1_1") (pintype "passive"))
      (node (ref "U2012") (pin "5") (pinfunction "5_5") (pintype "passive"))
    )
    (net (code "63") (name "Net-(C2071-Pad1)") (class "Default")
      (node (ref "C2071") (pin "1") (pinfunction "1_1") (pintype "passive"))
      (node (ref "L2071") (pin "2") (pinfunction "2_2") (pintype "passive"))
      (node (ref "R2004") (pin "1") (pinfunction "1_1") (pintype "passive"))
      (node (ref "U2021") (pin "5") (pinfunction "5_5") (pintype "passive"))
    )
    (net (code "64") (name "Net-(C2072-Pad1)") (class "Default")
      (node (ref "C2072") (pin "1") (pinfunction "1_1") (pintype "passive"))
      (node (ref "L2072") (pin "2") (pinfunction "2_2") (pintype "passive"))
      (node (ref "U2022") (pin "5") (pinfunction "5_5") (pintype "passive"))
    )
    (net (code "65") (name "Net-(D0901-PadA)") (class "Default")
      (node (ref "D0901") (pin "A") (pinfunction "A_A") (pintype "passive"))
      (node (ref "R0903") (pin "1") (pinfunction "1_1") (pintype "passive"))
    )
    (net (code "66") (name "Net-(L2011-Pad2)") (class "Default")
      (node (ref "L2011") (pin "2") (pinfunction "2_2") (pintype "passive"))
      (node (ref "R2011") (pin "1") (pinfunction "1_1") (pintype "passive"))
    )
    (net (code "67") (name "Net-(L2012-Pad2)") (class "Default")
      (node (ref "L2012") (pin "2") (pinfunction "2_2") (pintype "passive"))
      (node (ref "R2012") (pin "1") (pinfunction "1_1") (pintype "passive"))
    )
    (net (code "68") (name "Net-(L2021-Pad1)") (class "Default")
      (node (ref "L2021") (pin "1") (pinfunction "1_1") (pintype "passive"))
      (node (ref "R2021") (pin "2") (pinfunction "2_2") (pintype "passive"))
    )
    (net (code "69") (name "Net-(L2022-Pad1)") (class "Default")
      (node (ref "L2022") (pin "1") (pinfunction "1_1") (pintype "passive"))
      (node (ref "R2022") (pin "2") (pinfunction "2_2") (pintype "passive"))
    )
    (net (code "70") (name "Net-(L2061-Pad2)") (class "Default")
      (node (ref "L2061") (pin "2") (pinfunction "2_2") (pintype "passive"))
      (node (ref "R2061") (pin "1") (pinfunction "1_1") (pintype "passive"))
    )
    (net (code "71") (name "Net-(L2062-Pad2)") (class "Default")
      (node (ref "L2062") (pin "2") (pinfunction "2_2") (pintype "passive"))
      (node (ref "R2062") (pin "1") (pinfunction "1_1") (pintype "passive"))
    )
    (net (code "72") (name "Net-(L2071-Pad1)") (class "Default")
      (node (ref "L2071") (pin "1") (pinfunction "1_1") (pintype "passive"))
      (node (ref "R2071") (pin "2") (pinfunction "2_2") (pintype "passive"))
    )
    (net (code "73") (name "Net-(L2072-Pad1)") (class "Default")
      (node (ref "L2072") (pin "1") (pinfunction "1_1") (pintype "passive"))
      (node (ref "R2072") (pin "2") (pinfunction "2_2") (pintype "passive"))
    )
    (net (code "74") (name "Net-(Q1011-2)") (class "Default")
      (node (ref "Q1011") (pin "3") (pinfunction "2_3") (pintype "passive"))
      (node (ref "U1001") (pin "4") (pinfunction "XTB_4") (pintype "passive"))
    )
    (net (code "75") (name "Net-(R2090-Pad2)") (class "Default")
      (node (ref "R2090") (pin "2") (pinfunction "2_2") (pintype "passive"))
      (node (ref "U2011") (pin "3") (pinfunction "3_3") (pintype "input"))
      (node (ref "U2011") (pin "7") (pinfunction "7_7") (pintype "input"))
      (node (ref "U2021") (pin "3") (pinfunction "3_3") (pintype "input"))
      (node (ref "U2021") (pin "7") (pinfunction "7_7") (pintype "input"))
    )
    (net (code "76") (name "Net-(R2091-Pad2)") (class "Default")
      (node (ref "R2091") (pin "2") (pinfunction "2_2") (pintype "passive"))
      (node (ref "U2012") (pin "3") (pinfunction "3_3") (pintype "input"))
      (node (ref "U2012") (pin "7") (pinfunction "7_7") (pintype "input"))
      (node (ref "U2022") (pin "3") (pinfunction "3_3") (pintype "input"))
      (node (ref "U2022") (pin "7") (pinfunction "7_7") (pintype "input"))
    )
    (net (code "77") (name "Net-(U0711-VBG)") (class "Default")
      (node (ref "C0711") (pin "1") (pinfunction "1_1") (pintype "passive"))
      (node (ref "U0711") (pin "6") (pinfunction "VBG_6") (pintype "passive"))
    )
    (net (code "78") (name "Net-(U0811-~{INT})") (class "Default")
      (node (ref "R0811") (pin "2") (pinfunction "2_2") (pintype "passive"))
      (node (ref "U0811") (pin "1") (pinfunction "~{INT}_1") (pintype "output"))
    )
    (net (code "79") (name "Net-(U0811-~{RESET})") (class "Default")
      (node (ref "R0802") (pin "1") (pinfunction "1_1") (pintype "passive"))
      (node (ref "U0811") (pin "3") (pinfunction "~{RESET}_3") (pintype "input"))
    )
    (net (code "80") (name "Net-(U0911-CLKSEL1{slash}XOUT32)") (class "Default")
      (node (ref "C0922") (pin "1") (pinfunction "1_1") (pintype "passive"))
      (node (ref "Q0921") (pin "1") (pinfunction "1_1") (pintype "passive"))
      (node (ref "U0911") (pin "26") (pinfunction "CLKSEL1/XOUT32_26") (pintype "output"))
    )
    (net (code "81") (name "Net-(U0911-XIN32)") (class "Default")
      (node (ref "C0921") (pin "1") (pinfunction "1_1") (pintype "passive"))
      (node (ref "Q0921") (pin "2") (pinfunction "2_2") (pintype "passive"))
      (node (ref "U0911") (pin "27") (pinfunction "XIN32_27") (pintype "input"))
    )
    (net (code "82") (name "Net-(U1001-BUSY)") (class "Default")
      (node (ref "R1011") (pin "2") (pinfunction "2_2") (pintype "passive"))
      (node (ref "U1001") (pin "14") (pinfunction "BUSY_14") (pintype "bidirectional"))
    )
    (net (code "83") (name "Net-(U1001-DCC_SW)") (class "Default")
      (node (ref "L1001") (pin "1") (pinfunction "1_1") (pintype "passive"))
      (node (ref "U1001") (pin "9") (pinfunction "DCC_SW_9") (pintype "passive"))
    )
    (net (code "84") (name "Net-(U1001-DIO1)") (class "Default")
      (node (ref "R1053") (pin "1") (pinfunction "1_1") (pintype "passive"))
      (node (ref "TP_SX_DIO1") (pin "TP") (pinfunction "TP_TP") (pintype "input"))
      (node (ref "U1001") (pin "13") (pinfunction "DIO1_13") (pintype "bidirectional"))
    )
    (net (code "85") (name "Net-(U1001-DIO2)") (class "Default")
      (node (ref "R1052") (pin "1") (pinfunction "1_1") (pintype "passive"))
      (node (ref "TP_SX_DIO2") (pin "TP") (pinfunction "TP_TP") (pintype "input"))
      (node (ref "U1001") (pin "12") (pinfunction "DIO2_12") (pintype "bidirectional"))
    )
    (net (code "86") (name "Net-(U1001-DIO3)") (class "Default")
      (node (ref "R1051") (pin "1") (pinfunction "1_1") (pintype "passive"))
      (node (ref "TP_SX_DIO3") (pin "TP") (pinfunction "TP_TP") (pintype "input"))
      (node (ref "U1001") (pin "6") (pinfunction "DIO3_6") (pintype "bidirectional"))
    )
    (net (code "87") (name "Net-(U1001-MISO)") (class "Default")
      (node (ref "R1024") (pin "2") (pinfunction "2_2") (pintype "passive"))
      (node (ref "U1001") (pin "16") (pinfunction "MISO_16") (pintype "output"))
    )
    (net (code "88") (name "Net-(U1001-NSS)") (class "Default")
      (node (ref "R1021") (pin "2") (pinfunction "2_2") (pintype "passive"))
      (node (ref "U1001") (pin "19") (pinfunction "NSS_19") (pintype "input"))
    )
    (net (code "89") (name "Net-(U1001-RFI_N)") (class "Default")
      (node (ref "C1092") (pin "1") (pinfunction "1_1") (pintype "passive"))
      (node (ref "L1091") (pin "1") (pinfunction "1_1") (pintype "passive"))
      (node (ref "U1001") (pin "22") (pinfunction "RFI_N_22") (pintype "passive"))
    )
    (net (code "90") (name "Net-(U1001-RFI_P)") (class "Default")
      (node (ref "C1091") (pin "2") (pinfunction "2_2") (pintype "passive"))
      (node (ref "L1091") (pin "2") (pinfunction "2_2") (pintype "passive"))
      (node (ref "U1001") (pin "21") (pinfunction "RFI_P_21") (pintype "passive"))
    )
    (net (code "91") (name "Net-(U1001-RFO)") (class "Default")
      (node (ref "C1063") (pin "1") (pinfunction "1_1") (pintype "passive"))
      (node (ref "C1065") (pin "2") (pinfunction "2_2") (pintype "passive"))
      (node (ref "L1062") (pin "1") (pinfunction "1_1") (pintype "passive"))
      (node (ref "L1063") (pin "2") (pinfunction "2_2") (pintype "passive"))
      (node (ref "U1001") (pin "23") (pinfunction "RFO_23") (pintype "passive"))
    )
    (net (code "92") (name "Net-(U1001-VDD_IN)") (class "Default")
      (node (ref "C1006") (pin "2") (pinfunction "2_2") (pintype "passive"))
      (node (ref "L1002") (pin "1") (pinfunction "1_1") (pintype "passive"))
      (node (ref "U1001") (pin "1") (pinfunction "VDD_IN_1") (pintype "power_in"))
    )
    (net (code "93") (name "Net-(U1001-VREG)") (class "Default")
      (node (ref "C1003") (pin "1") (pinfunction "1_1") (pintype "passive"))
      (node (ref "L1001") (pin "2") (pinfunction "2_2") (pintype "passive"))
      (node (ref "L1002") (pin "2") (pinfunction "2_2") (pintype "passive"))
      (node (ref "U1001") (pin "7") (pinfunction "VREG_7") (pintype "power_in"))
    )
    (net (code "94") (name "Net-(U1001-VR_PA)") (class "Default")
      (node (ref "C1004") (pin "1") (pinfunction "1_1") (pintype "passive"))
      (node (ref "C1005") (pin "1") (pinfunction "1_1") (pintype "passive"))
      (node (ref "L1062") (pin "2") (pinfunction "2_2") (pintype "passive"))
      (node (ref "U1001") (pin "24") (pinfunction "VR_PA_24") (pintype "power_in"))
    )
    (net (code "95") (name "Net-(U1001-XTA)") (class "Default")
      (node (ref "Q1011") (pin "1") (pinfunction "1_1") (pintype "passive"))
      (node (ref "U1001") (pin "3") (pinfunction "XTA_3") (pintype "passive"))
    )
    (net (code "96") (name "Net-(U1071-RF1)") (class "Default")
      (node (ref "C1067") (pin "1") (pinfunction "1_1") (pintype "passive"))
      (node (ref "L1064") (pin "1") (pinfunction "1_1") (pintype "passive"))
      (node (ref "U1071") (pin "1") (pinfunction "RF1_1") (pintype "passive"))
    )
    (net (code "97") (name "Net-(U1071-RF2)") (class "Default")
      (node (ref "C1092") (pin "2") (pinfunction "2_2") (pintype "passive"))
      (node (ref "C1093") (pin "2") (pinfunction "2_2") (pintype "passive"))
      (node (ref "U1071") (pin "3") (pinfunction "RF2_3") (pintype "passive"))
    )
    (net (code "98") (name "Net-(U1071-RFC)") (class "Default")
      (node (ref "C1081") (pin "1") (pinfunction "1_1") (pintype "passive"))
      (node (ref "U1071") (pin "5") (pinfunction "RFC_5") (pintype "passive"))
    )
    (net (code "99") (name "Net-(U1071-VDD_~{CTRL})") (class "Default")
      (node (ref "C1071") (pin "1") (pinfunction "1_1") (pintype "passive"))
      (node (ref "R1071") (pin "1") (pinfunction "1_1") (pintype "passive"))
      (node (ref "U1071") (pin "6") (pinfunction "VDD_~{CTRL}_6") (pintype "passive"))
    )
    (net (code "100") (name "Net-(U1111-~{INT})") (class "Default")
      (node (ref "R1111") (pin "2") (pinfunction "2_2") (pintype "passive"))
      (node (ref "U1111") (pin "1") (pinfunction "~{INT}_1") (pintype "output"))
    )
    (net (code "101") (name "Net-(U1111-~{RESET})") (class "Default")
      (node (ref "R1112") (pin "1") (pinfunction "1_1") (pintype "passive"))
      (node (ref "U1111") (pin "3") (pinfunction "~{RESET}_3") (pintype "input"))
    )
    (net (code "102") (name "Net-(U1311-SW)") (class "Default")
      (node (ref "L1311") (pin "2") (pinfunction "2_2") (pintype "passive"))
      (node (ref "U1311") (pin "2") (pinfunction "SW_2") (pintype "passive"))
    )
    (net (code "103") (name "Net-(U1411-SW)") (class "Default")
      (node (ref "L1411") (pin "2") (pinfunction "2_2") (pintype "passive"))
      (node (ref "U1411") (pin "1A") (pinfunction "SW_1A") (pintype "passive"))
    )
    (net (code "104") (name "PA0") (class "Default")
      (node (ref "C2132") (pin "1") (pinfunction "1_1") (pintype "passive"))
      (node (ref "S2131") (pin "1") (pinfunction "1_1") (pintype "passive"))
      (node (ref "U0101") (pin "14") (pinfunction "PA0_WKUP_14") (pintype "bidirectional"))
    )
    (net (code "105") (name "PA1") (class "Default")
      (node (ref "U0101") (pin "15") (pinfunction "PA1_15") (pintype "bidirectional"))
      (node (ref "X2253") (pin "8") (pinfunction "8_8") (pintype "passive"))
    )
    (net (code "106") (name "PA2") (class "Default")
      (node (ref "U0101") (pin "16") (pinfunction "PA2_WKUP_16") (pintype "bidirectional"))
      (node (ref "X2253") (pin "9") (pinfunction "9_9") (pintype "passive"))
    )
    (net (code "107") (name "PA4") (class "Default")
      (node (ref "C0461") (pin "1") (pinfunction "1_1") (pintype "passive"))
      (node (ref "R0461") (pin "2") (pinfunction "2_2") (pintype "passive"))
      (node (ref "R0462") (pin "1") (pinfunction "1_1") (pintype "passive"))
      (node (ref "U0101") (pin "20") (pinfunction "PA4_20") (pintype "bidirectional"))
    )
    (net (code "108") (name "PA5") (class "Default")
      (node (ref "U0101") (pin "21") (pinfunction "PA5_21") (pintype "bidirectional"))
      (node (ref "X2252") (pin "9") (pinfunction "9_9") (pintype "passive"))
    )
    (net (code "109") (name "PA6") (class "Default")
      (node (ref "U0101") (pin "22") (pinfunction "PA6_22") (pintype "bidirectional"))
      (node (ref "X2252") (pin "8") (pinfunction "8_8") (pintype "passive"))
      (node (ref "X2253") (pin "7") (pinfunction "7_7") (pintype "passive"))
    )
    (net (code "110") (name "PA7") (class "Default")
      (node (ref "U0101") (pin "23") (pinfunction "PA7_23") (pintype "bidirectional"))
      (node (ref "X2252") (pin "7") (pinfunction "7_7") (pintype "passive"))
    )
    (net (code "111") (name "PA8") (class "Default")
      (node (ref "U0101") (pin "41") (pinfunction "PA8_41") (pintype "bidirectional"))
      (node (ref "U1511") (pin "7") (pinfunction "7_7") (pintype "input"))
    )
    (net (code "112") (name "PA9") (class "Default")
      (node (ref "R0512") (pin "1") (pinfunction "1_1") (pintype "passive"))
      (node (ref "U0101") (pin "42") (pinfunction "PA9_42") (pintype "bidirectional"))
      (node (ref "U0611") (pin "6") (pinfunction "SCL_6") (pintype "input"))
      (node (ref "U0711") (pin "13") (pinfunction "SCLK_13") (pintype "input"))
      (node (ref "U0811") (pin "22") (pinfunction "SCL_22") (pintype "input"))
      (node (ref "U1111") (pin "22") (pinfunction "SCL_22") (pintype "input"))
      (node (ref "X2252") (pin "2") (pinfunction "2_2") (pintype "passive"))
    )
    (net (code "113") (name "PA10") (class "Default")
      (node (ref "R0511") (pin "1") (pinfunction "1_1") (pintype "passive"))
      (node (ref "U0101") (pin "43") (pinfunction "PA10_43") (pintype "bidirectional"))
      (node (ref "U0611") (pin "5") (pinfunction "SDA_5") (pintype "bidirectional"))
      (node (ref "U0711") (pin "14") (pinfunction "SDIO_14") (pintype "bidirectional"))
      (node (ref "U0811") (pin "23") (pinfunction "SDA_23") (pintype "bidirectional"))
      (node (ref "U1111") (pin "23") (pinfunction "SDA_23") (pintype "bidirectional"))
      (node (ref "X2252") (pin "1") (pinfunction "1_1") (pintype "passive"))
    )
    (net (code "114") (name "PA11") (class "Default")
      (node (ref "R1257") (pin "2") (pinfunction "2_2") (pintype "passive"))
      (node (ref "U0101") (pin "44") (pinfunction "PA11_44") (pintype "bidirectional"))
    )
    (net (code "115") (name "PA12") (class "Default")
      (node (ref "R1266") (pin "2") (pinfunction "2_2") (pintype "passive"))
      (node (ref "U0101") (pin "45") (pinfunction "PA12_45") (pintype "bidirectional"))
    )
    (net (code "116") (name "PA13") (class "Default")
      (node (ref "R0201") (pin "1") (pinfunction "1_1") (pintype "passive"))
      (node (ref "U0101") (pin "46") (pinfunction "PA13_JTMS_SWDIO_46") (pintype "bidirectional"))
      (node (ref "X0201") (pin "2") (pinfunction "2_2") (pintype "passive"))
    )
    (net (code "117") (name "PA14") (class "Default")
      (node (ref "R0202") (pin "2") (pinfunction "2_2") (pintype "passive"))
      (node (ref "U0101") (pin "49") (pinfunction "PA14_JTCK_SWCLK_49") (pintype "bidirectional"))
      (node (ref "X0201") (pin "4") (pinfunction "4_4") (pintype "passive"))
    )
    (net (code "118") (name "PB0") (class "Default")
      (node (ref "U0101") (pin "25") (pinfunction "PB0_25") (pintype "bidirectional"))
    )
    (net (code "119") (name "PB1") (class "Default")
      (node (ref "U0101") (pin "26") (pinfunction "PB1_26") (pintype "bidirectional"))
      (node (ref "X2253") (pin "5") (pinfunction "5_5") (pintype "passive"))
    )
    (net (code "120") (name "PB5") (class "Default")
      (node (ref "U0101") (pin "56") (pinfunction "PB5_56") (pintype "bidirectional"))
      (node (ref "U1601") (pin "3") (pinfunction "3_3") (pintype "input"))
      (node (ref "U1601") (pin "7") (pinfunction "7_7") (pintype "input"))
    )
    (net (code "121") (name "PB6") (class "Default")
      (node (ref "R1271") (pin "2") (pinfunction "2_2") (pintype "passive"))
      (node (ref "U0101") (pin "57") (pinfunction "PB6_57") (pintype "bidirectional"))
    )
    (net (code "122") (name "PB7") (class "Default")
      (node (ref "R1272") (pin "2") (pinfunction "2_2") (pintype "passive"))
      (node (ref "U0101") (pin "58") (pinfunction "PB7_58") (pintype "bidirectional"))
    )
    (net (code "123") (name "PB8") (class "Default")
      (node (ref "C2121") (pin "1") (pinfunction "1_1") (pintype "passive"))
      (node (ref "R2121") (pin "2") (pinfunction "2_2") (pintype "passive"))
      (node (ref "U0101") (pin "60") (pinfunction "PB8_60") (pintype "bidirectional"))
    )
    (net (code "124") (name "PB10") (class "Default")
      (node (ref "U0101") (pin "28") (pinfunction "PB10_28") (pintype "bidirectional"))
      (node (ref "X2253") (pin "1") (pinfunction "1_1") (pintype "passive"))
    )
    (net (code "125") (name "PB11") (class "Default")
      (node (ref "U0101") (pin "29") (pinfunction "PB11_29") (pintype "bidirectional"))
      (node (ref "X2253") (pin "2") (pinfunction "2_2") (pintype "passive"))
    )
    (net (code "126") (name "PB12") (class "Default")
      (node (ref "U0101") (pin "33") (pinfunction "PB12_33") (pintype "bidirectional"))
      (node (ref "U1701") (pin "3") (pinfunction "3_3") (pintype "input"))
      (node (ref "U1701") (pin "7") (pinfunction "7_7") (pintype "input"))
    )
    (net (code "127") (name "PB13") (class "Default")
      (node (ref "U0101") (pin "34") (pinfunction "PB13_34") (pintype "bidirectional"))
      (node (ref "X2253") (pin "6") (pinfunction "6_6") (pintype "passive"))
    )
    (net (code "128") (name "PB14") (class "Default")
      (node (ref "U0101") (pin "35") (pinfunction "PB14_35") (pintype "bidirectional"))
      (node (ref "U1411") (pin "1B") (pinfunction "EN_1B") (pintype "input"))
    )
    (net (code "129") (name "PB15") (class "Default")
      (node (ref "U0101") (pin "36") (pinfunction "PB15_36") (pintype "bidirectional"))
      (node (ref "U1511") (pin "3") (pinfunction "3_3") (pintype "input"))
    )
    (net (code "130") (name "PC0") (class "Default")
      (node (ref "U0101") (pin "8") (pinfunction "PC0_8") (pintype "bidirectional"))
      (node (ref "X2253") (pin "4") (pinfunction "4_4") (pintype "passive"))
    )
    (net (code "131") (name "PC1") (class "Default")
      (node (ref "U0101") (pin "9") (pinfunction "PC1_9") (pintype "bidirectional"))
      (node (ref "X2253") (pin "3") (pinfunction "3_3") (pintype "passive"))
    )
    (net (code "132") (name "PC2") (class "Default")
      (node (ref "U0101") (pin "10") (pinfunction "PC2_10") (pintype "bidirectional"))
      (node (ref "X2252") (pin "3") (pinfunction "3_3") (pintype "passive"))
    )
    (net (code "133") (name "PC3") (class "Default")
      (node (ref "U0101") (pin "11") (pinfunction "PC3_11") (pintype "bidirectional"))
      (node (ref "X2252") (pin "4") (pinfunction "4_4") (pintype "passive"))
    )
    (net (code "134") (name "PC4") (class "Default")
      (node (ref "U0101") (pin "24") (pinfunction "PC4_24") (pintype "bidirectional"))
      (node (ref "U1801") (pin "3") (pinfunction "3_3") (pintype "input"))
      (node (ref "U1801") (pin "7") (pinfunction "7_7") (pintype "input"))
      (node (ref "X2252") (pin "5") (pinfunction "5_5") (pintype "passive"))
    )
    (net (code "135") (name "PC7") (class "Default")
      (node (ref "R1111") (pin "1") (pinfunction "1_1") (pintype "passive"))
      (node (ref "U0101") (pin "38") (pinfunction "PC7_38") (pintype "bidirectional"))
    )
    (net (code "136") (name "PC8") (class "Default")
      (node (ref "R0811") (pin "1") (pinfunction "1_1") (pintype "passive"))
      (node (ref "U0101") (pin "39") (pinfunction "PC8_39") (pintype "bidirectional"))
    )
    (net (code "137") (name "PC9") (class "Default")
      (node (ref "R0731") (pin "1") (pinfunction "1_1") (pintype "passive"))
      (node (ref "U0101") (pin "40") (pinfunction "PC9_40") (pintype "bidirectional"))
    )
    (net (code "138") (name "PC10") (class "Default")
      (node (ref "R0552") (pin "1") (pinfunction "1_1") (pintype "passive"))
      (node (ref "U0101") (pin "51") (pinfunction "PC10_51") (pintype "bidirectional"))
    )
    (net (code "139") (name "PC11") (class "Default")
      (node (ref "R0901") (pin "1") (pinfunction "1_1") (pintype "passive"))
      (node (ref "R1024") (pin "1") (pinfunction "1_1") (pintype "passive"))
      (node (ref "U0101") (pin "52") (pinfunction "PC11_52") (pintype "bidirectional"))
    )
    (net (code "140") (name "PC12") (class "Default")
      (node (ref "R0551") (pin "1") (pinfunction "1_1") (pintype "passive"))
      (node (ref "U0101") (pin "53") (pinfunction "PC12_53") (pintype "bidirectional"))
    )
    (net (code "141") (name "PC13") (class "Default")
      (node (ref "D0901") (pin "C") (pinfunction "C_C") (pintype "passive"))
      (node (ref "U0101") (pin "2") (pinfunction "PC13_WKUP_2") (pintype "bidirectional"))
      (node (ref "X2252") (pin "6") (pinfunction "6_6") (pintype "passive"))
    )
    (net (code "142") (name "PC14_OSC32_IN") (class "Default")
      (node (ref "C0331") (pin "-") (pinfunction "E_-") (pintype "passive"))
      (node (ref "C0332") (pin "1") (pinfunction "1_1") (pintype "passive"))
      (node (ref "Q0321") (pin "2") (pinfunction "2_2") (pintype "passive"))
      (node (ref "U0101") (pin "3") (pinfunction "PC14_OSC32_IN_3") (pintype "bidirectional"))
    )
    (net (code "143") (name "PC15_OSC32_OUT") (class "Default")
      (node (ref "C0311") (pin "1") (pinfunction "1_1") (pintype "passive"))
      (node (ref "Q0321") (pin "1") (pinfunction "1_1") (pintype "passive"))
      (node (ref "U0101") (pin "4") (pinfunction "PC15_OSC32_OUT_4") (pintype "bidirectional"))
    )
    (net (code "144") (name "PEXPA_P0_0_R") (class "Default")
      (node (ref "U0811") (pin "4") (pinfunction "P0_0_4") (pintype "bidirectional"))
      (node (ref "U0911") (pin "11") (pinfunction "NRST_11") (pintype "input"))
    )
    (net (code "145") (name "PEXPA_P0_1_R") (class "Default")
      (node (ref "R0904") (pin "1") (pinfunction "1_1") (pintype "passive"))
      (node (ref "U0811") (pin "5") (pinfunction "P0_1_5") (pintype "bidirectional"))
    )
    (net (code "146") (name "PEXPA_P0_2_R") (class "Default")
      (node (ref "U0811") (pin "6") (pinfunction "P0_2_6") (pintype "bidirectional"))
      (node (ref "U0911") (pin "4") (pinfunction "BOOTN_4") (pintype "input"))
    )
    (net (code "147") (name "PEXPA_P0_3_R") (class "Default")
      (node (ref "R0902") (pin "1") (pinfunction "1_1") (pintype "passive"))
      (node (ref "U0811") (pin "7") (pinfunction "P0_3_7") (pintype "bidirectional"))
    )
    (net (code "148") (name "PEXPA_P0_4_R") (class "Default")
      (node (ref "U0811") (pin "8") (pinfunction "P0_4_8") (pintype "bidirectional"))
    )
    (net (code "149") (name "PEXPA_P0_5_R") (class "Default")
      (node (ref "U0811") (pin "9") (pinfunction "P0_5_9") (pintype "bidirectional"))
    )
    (net (code "150") (name "PEXPA_P0_6_R") (class "Default")
      (node (ref "U0811") (pin "10") (pinfunction "P0_6_10") (pintype "bidirectional"))
    )
    (net (code "151") (name "PEXPA_P0_7_R") (class "Default")
      (node (ref "U0811") (pin "11") (pinfunction "P0_7_11") (pintype "bidirectional"))
    )
    (net (code "152") (name "PEXPA_P1_0_R") (class "Default")
      (node (ref "U0811") (pin "13") (pinfunction "P1_0_13") (pintype "bidirectional"))
      (node (ref "U1001") (pin "15") (pinfunction "NRESET_15") (pintype "bidirectional"))
    )
    (net (code "153") (name "PEXPA_P1_1_R") (class "Default")
      (node (ref "R1021") (pin "1") (pinfunction "1_1") (pintype "passive"))
      (node (ref "U0811") (pin "14") (pinfunction "P1_1_14") (pintype "bidirectional"))
    )
    (net (code "154") (name "PEXPA_P1_2_R") (class "Default")
      (node (ref "R1011") (pin "1") (pinfunction "1_1") (pintype "passive"))
      (node (ref "U0811") (pin "15") (pinfunction "P1_2_15") (pintype "bidirectional"))
    )
    (net (code "155") (name "PEXPA_P1_3_R") (class "Default")
      (node (ref "R1053") (pin "2") (pinfunction "2_2") (pintype "passive"))
      (node (ref "U0811") (pin "16") (pinfunction "P1_3_16") (pintype "bidirectional"))
    )
    (net (code "156") (name "PEXPA_P1_4_R") (class "Default")
      (node (ref "C1072") (pin "1") (pinfunction "1_1") (pintype "passive"))
      (node (ref "R1052") (pin "2") (pinfunction "2_2") (pintype "passive"))
      (node (ref "U0811") (pin "17") (pinfunction "P1_4_17") (pintype "bidirectional"))
      (node (ref "U1071") (pin "4") (pinfunction "CTRL_4") (pintype "input"))
    )
    (net (code "157") (name "PEXPA_P1_5_R") (class "Default")
      (node (ref "R1051") (pin "2") (pinfunction "2_2") (pintype "passive"))
      (node (ref "U0811") (pin "18") (pinfunction "P1_5_18") (pintype "bidirectional"))
    )
    (net (code "158") (name "PEXPA_P1_6_R") (class "Default")
      (node (ref "U0811") (pin "19") (pinfunction "P1_6_19") (pintype "bidirectional"))
      (node (ref "X2251") (pin "7") (pinfunction "7_7") (pintype "passive"))
    )
    (net (code "159") (name "PEXPA_P1_7_R") (class "Default")
      (node (ref "U0811") (pin "20") (pinfunction "P1_7_20") (pintype "bidirectional"))
      (node (ref "X2251") (pin "8") (pinfunction "8_8") (pintype "passive"))
    )
    (net (code "160") (name "PEXPB_P0_0_R") (class "Default")
      (node (ref "U1111") (pin "4") (pinfunction "P0_0_4") (pintype "bidirectional"))
    )
    (net (code "161") (name "PEXPB_P0_1_R") (class "Default")
      (node (ref "U1111") (pin "5") (pinfunction "P0_1_5") (pintype "bidirectional"))
      (node (ref "U1211") (pin "1") (pinfunction "RST_1") (pintype "input"))
    )
    (net (code "162") (name "PEXPB_P0_2_R") (class "Default")
      (node (ref "U1111") (pin "6") (pinfunction "P0_2_6") (pintype "bidirectional"))
      (node (ref "U1211") (pin "3") (pinfunction "EN_3") (pintype "input"))
    )
    (net (code "163") (name "PEXPB_P0_3_R") (class "Default")
      (node (ref "U1111") (pin "7") (pinfunction "P0_3_7") (pintype "bidirectional"))
      (node (ref "U1211") (pin "4") (pinfunction "GPIO16_WKUP_4") (pintype "bidirectional"))
    )
    (net (code "164") (name "PEXPB_P0_4_R") (class "Default")
      (node (ref "U1111") (pin "8") (pinfunction "P0_4_8") (pintype "bidirectional"))
      (node (ref "U1211") (pin "5") (pinfunction "GPIO14_5") (pintype "bidirectional"))
    )
    (net (code "165") (name "PEXPB_P0_5_R") (class "Default")
      (node (ref "U1111") (pin "9") (pinfunction "P0_5_9") (pintype "bidirectional"))
      (node (ref "U1211") (pin "6") (pinfunction "GPIO12_6") (pintype "bidirectional"))
    )
    (net (code "166") (name "PEXPB_P0_6_R") (class "Default")
      (node (ref "U1111") (pin "10") (pinfunction "P0_6_10") (pintype "bidirectional"))
      (node (ref "U1211") (pin "9") (pinfunction "CS0_9") (pintype "input"))
    )
    (net (code "167") (name "PEXPB_P0_7_R") (class "Default")
      (node (ref "U1111") (pin "11") (pinfunction "P0_7_11") (pintype "bidirectional"))
      (node (ref "U1211") (pin "10") (pinfunction "MISO_10") (pintype "bidirectional"))
    )
    (net (code "168") (name "PEXPB_P1_0_R") (class "Default")
      (node (ref "U1111") (pin "13") (pinfunction "P1_0_13") (pintype "bidirectional"))
      (node (ref "U1211") (pin "11") (pinfunction "GPIO9_11") (pintype "bidirectional"))
    )
    (net (code "169") (name "PEXPB_P1_1_R") (class "Default")
      (node (ref "U1111") (pin "14") (pinfunction "P1_1_14") (pintype "bidirectional"))
      (node (ref "U1211") (pin "12") (pinfunction "GPIO10_12") (pintype "bidirectional"))
    )
    (net (code "170") (name "PEXPB_P1_2_R") (class "Default")
      (node (ref "U1111") (pin "15") (pinfunction "P1_2_15") (pintype "bidirectional"))
      (node (ref "U1211") (pin "13") (pinfunction "MOSI_13") (pintype "bidirectional"))
    )
    (net (code "171") (name "PEXPB_P1_3_R") (class "Default")
      (node (ref "U1111") (pin "16") (pinfunction "P1_3_16") (pintype "bidirectional"))
      (node (ref "U1211") (pin "14") (pinfunction "SCLK_14") (pintype "bidirectional"))
    )
    (net (code "172") (name "PEXPB_P1_4_R") (class "Default")
      (node (ref "U1111") (pin "17") (pinfunction "P1_4_17") (pintype "bidirectional"))
      (node (ref "U1211") (pin "17") (pinfunction "GPIO2_17") (pintype "bidirectional"))
    )
    (net (code "173") (name "PEXPB_P1_5_R") (class "Default")
      (node (ref "U1111") (pin "18") (pinfunction "P1_5_18") (pintype "bidirectional"))
      (node (ref "U1211") (pin "18") (pinfunction "GPIO0_18") (pintype "bidirectional"))
    )
    (net (code "174") (name "PEXPB_P1_6_R") (class "Default")
      (node (ref "U1111") (pin "19") (pinfunction "P1_6_19") (pintype "bidirectional"))
      (node (ref "U1211") (pin "19") (pinfunction "GPIO4_19") (pintype "bidirectional"))
    )
    (net (code "175") (name "PEXPB_P1_7_R") (class "Default")
      (node (ref "U1111") (pin "20") (pinfunction "P1_7_20") (pintype "bidirectional"))
      (node (ref "U1211") (pin "20") (pinfunction "GPIO5_20") (pintype "bidirectional"))
    )
    (net (code "176") (name "PH0") (class "Default")
      (node (ref "R2090") (pin "1") (pinfunction "1_1") (pintype "passive"))
      (node (ref "U0101") (pin "5") (pinfunction "PH0_OSC_IN_5") (pintype "bidirectional"))
    )
    (net (code "177") (name "PH1") (class "Default")
      (node (ref "R2091") (pin "1") (pinfunction "1_1") (pintype "passive"))
      (node (ref "U0101") (pin "6") (pinfunction "PH1_OSC_OUT_6") (pintype "bidirectional"))
    )
    (net (code "178") (name "PH3_BOOT0") (class "Default")
      (node (ref "R0221") (pin "2") (pinfunction "2_2") (pintype "passive"))
      (node (ref "U0101") (pin "59") (pinfunction "BOOT0_59") (pintype "output"))
      (node (ref "X0222") (pin "2") (pinfunction "2_2") (pintype "passive"))
    )
    (net (code "179") (name "SPI3_MOSI") (class "Default")
      (node (ref "R0551") (pin "2") (pinfunction "2_2") (pintype "passive"))
      (node (ref "U0911") (pin "17") (pinfunction "SA0/H_MOSI_17") (pintype "input"))
      (node (ref "U1001") (pin "17") (pinfunction "MOSI_17") (pintype "input"))
    )
    (net (code "180") (name "SPI3_SCK") (class "Default")
      (node (ref "R0552") (pin "2") (pinfunction "2_2") (pintype "passive"))
      (node (ref "U0911") (pin "19") (pinfunction "H_SCL/SCL/RX_19") (pintype "bidirectional"))
      (node (ref "U1001") (pin "18") (pinfunction "SCLK_18") (pintype "input"))
    )
    (net (code "181") (name "VBAT") (class "Default")
      (node (ref "L2111") (pin "2") (pinfunction "2_2") (pintype "passive"))
      (node (ref "VIN+") (pin "1") (pinfunction "P_1") (pintype "passive"))
    )
    (net (code "182") (name "VBAT_L") (class "Default")
      (node (ref "C1301") (pin "1") (pinfunction "1_1") (pintype "passive"))
      (node (ref "C2111") (pin "1") (pinfunction "1_1") (pintype "passive"))
      (node (ref "L2111") (pin "1") (pinfunction "1_1") (pintype "passive"))
      (node (ref "U1311") (pin "1") (pinfunction "VIN_1") (pintype "power_in"))
      (node (ref "U1311") (pin "10") (pinfunction "VSEL2_10") (pintype "input"))
      (node (ref "U1311") (pin "11") (pinfunction "VSEL1_11") (pintype "input"))
      (node (ref "U1311") (pin "12") (pinfunction "EN_12") (pintype "input"))
      (node (ref "U1311") (pin "8") (pinfunction "VSEL4_8") (pintype "input"))
      (node (ref "U1311") (pin "9") (pinfunction "VSEL3_9") (pintype "input"))
      (node (ref "X2251") (pin "1") (pinfunction "1_1") (pintype "passive"))
    )
    (net (code "183") (name "VDDUSB") (class "Default")
      (node (ref "R0421") (pin "2") (pinfunction "2_2") (pintype "passive"))
      (node (ref "U0101") (pin "48") (pinfunction "VDDUSB_48") (pintype "power_in"))
    )
    (net (code "184") (name "unconnected-(U0101-PA3-Pad17)") (class "Default")
      (node (ref "U0101") (pin "17") (pinfunction "PA3_17") (pintype "bidirectional"))
    )
    (net (code "185") (name "unconnected-(U0101-PA15_JTDI-Pad50)") (class "Default")
      (node (ref "U0101") (pin "50") (pinfunction "PA15_JTDI_50") (pintype "bidirectional"))
    )
    (net (code "186") (name "unconnected-(U0101-PB2-Pad27)") (class "Default")
      (node (ref "U0101") (pin "27") (pinfunction "PB2_27") (pintype "bidirectional"))
    )
    (net (code "187") (name "unconnected-(U0101-PB3_JTDO_TRACESWO-Pad54)") (class "Default")
      (node (ref "U0101") (pin "54") (pinfunction "PB3_JTDO_TRACESWO_54") (pintype "bidirectional"))
    )
    (net (code "188") (name "unconnected-(U0101-PB4_NJTRST-Pad55)") (class "Default")
      (node (ref "U0101") (pin "55") (pinfunction "PB4_NJTRST_55") (pintype "bidirectional"))
    )
    (net (code "189") (name "unconnected-(U0101-PB9-Pad61)") (class "Default")
      (node (ref "U0101") (pin "61") (pinfunction "PB9_61") (pintype "bidirectional"))
    )
    (net (code "190") (name "unconnected-(U0101-PC6-Pad37)") (class "Default")
      (node (ref "U0101") (pin "37") (pinfunction "PC6_37") (pintype "bidirectional"))
    )
    (net (code "191") (name "unconnected-(U0711-XIN-Pad10)") (class "Default")
      (node (ref "U0711") (pin "10") (pinfunction "XIN_10") (pintype "passive"))
    )
    (net (code "192") (name "unconnected-(U0711-XOUT-Pad11)") (class "Default")
      (node (ref "U0711") (pin "11") (pinfunction "XOUT_11") (pintype "output"))
    )
    (net (code "193") (name "unconnected-(U0911-RESV_NC-Pad1)") (class "Default")
      (node (ref "U0911") (pin "1") (pinfunction "RESV_NC_1") (pintype "no_connect"))
    )
    (net (code "194") (name "unconnected-(U0911-RESV_NC-Pad7)") (class "Default")
      (node (ref "U0911") (pin "7") (pinfunction "RESV_NC_7") (pintype "no_connect"))
    )
    (net (code "195") (name "unconnected-(U0911-RESV_NC-Pad8)") (class "Default")
      (node (ref "U0911") (pin "8") (pinfunction "RESV_NC_8") (pintype "no_connect"))
    )
    (net (code "196") (name "unconnected-(U0911-RESV_NC-Pad12)") (class "Default")
      (node (ref "U0911") (pin "12") (pinfunction "RESV_NC_12") (pintype "no_connect"))
    )
    (net (code "197") (name "unconnected-(U0911-RESV_NC-Pad13)") (class "Default")
      (node (ref "U0911") (pin "13") (pinfunction "RESV_NC_13") (pintype "no_connect"))
    )
    (net (code "198") (name "unconnected-(U0911-RESV_NC-Pad21)") (class "Default")
      (node (ref "U0911") (pin "21") (pinfunction "RESV_NC_21") (pintype "no_connect"))
    )
    (net (code "199") (name "unconnected-(U0911-RESV_NC-Pad22)") (class "Default")
      (node (ref "U0911") (pin "22") (pinfunction "RESV_NC_22") (pintype "no_connect"))
    )
    (net (code "200") (name "unconnected-(U0911-RESV_NC-Pad23)") (class "Default")
      (node (ref "U0911") (pin "23") (pinfunction "RESV_NC_23") (pintype "no_connect"))
    )
    (net (code "201") (name "unconnected-(U0911-RESV_NC-Pad24)") (class "Default")
      (node (ref "U0911") (pin "24") (pinfunction "RESV_NC_24") (pintype "no_connect"))
    )
    (net (code "202") (name "unconnected-(U1311-PG-Pad7)") (class "Default")
      (node (ref "U1311") (pin "7") (pinfunction "PG_7") (pintype "open_collector"))
    )
    (net (code "203") (name "unconnected-(U1311-VIN_SW-Pad6)") (class "Default")
      (node (ref "U1311") (pin "6") (pinfunction "VIN_SW_6") (pintype "passive"))
    )
    (net (code "204") (name "unconnected-(X0201-Pad6)") (class "Default")
      (node (ref "X0201") (pin "6") (pinfunction "6_6") (pintype "passive"))
    )
    (net (code "205") (name "unconnected-(X0201-Pad7)") (class "Default")
      (node (ref "X0201") (pin "7") (pinfunction "7_7") (pintype "passive"))
    )
    (net (code "206") (name "unconnected-(X0201-Pad8)") (class "Default")
      (node (ref "X0201") (pin "8") (pinfunction "8_8") (pintype "passive"))
    )
  )
)
